# Titan_Servo_v1p01d.net
KiCad netlist of a schematic drawn in EAGLE
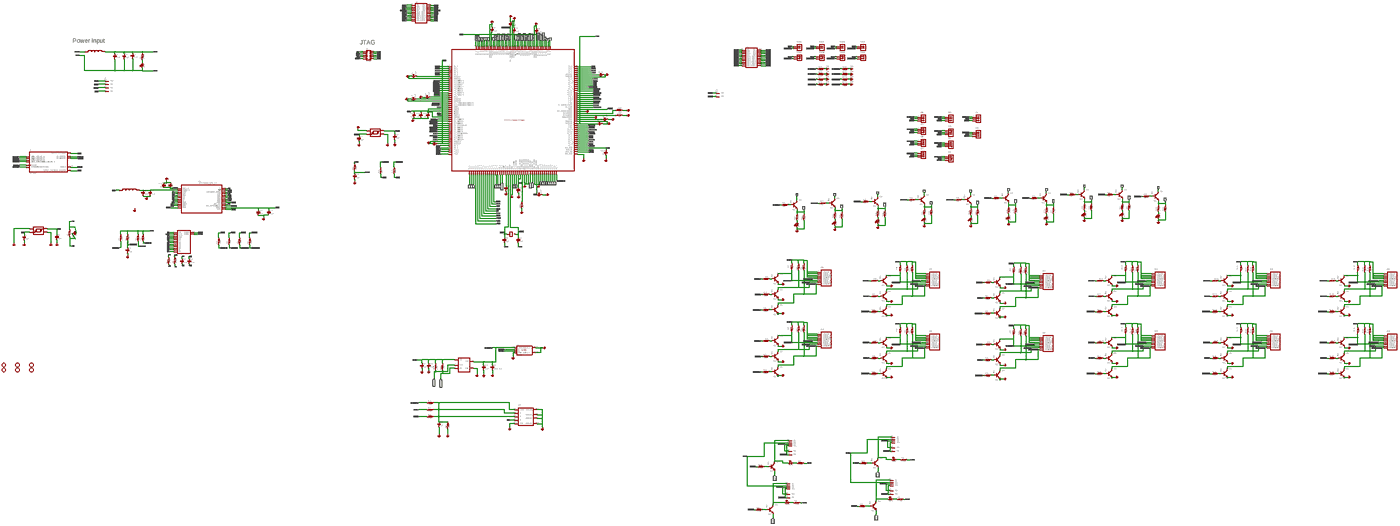
[diagram p0: schematic, sheet 1, overview]
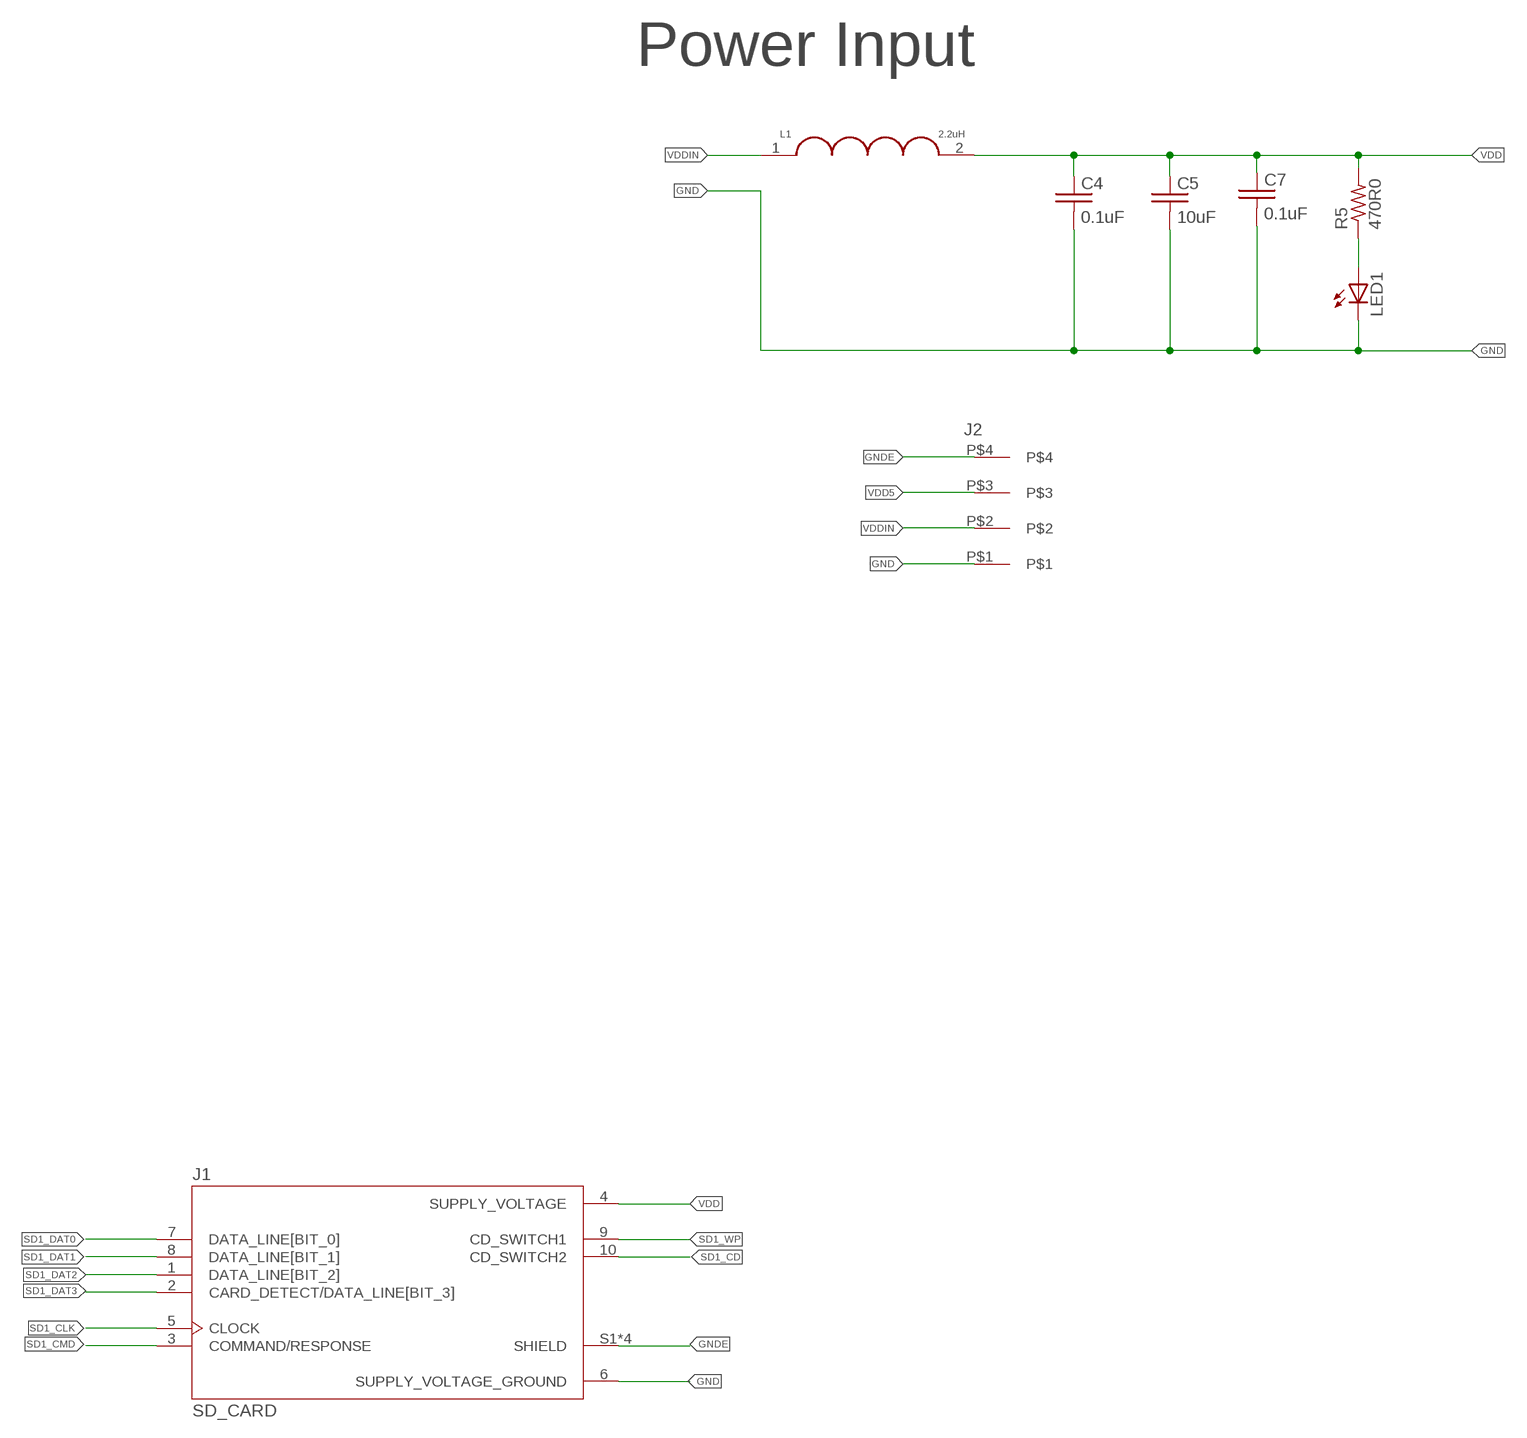
[diagram p1: schematic, sheet 1, part 1 of 9]
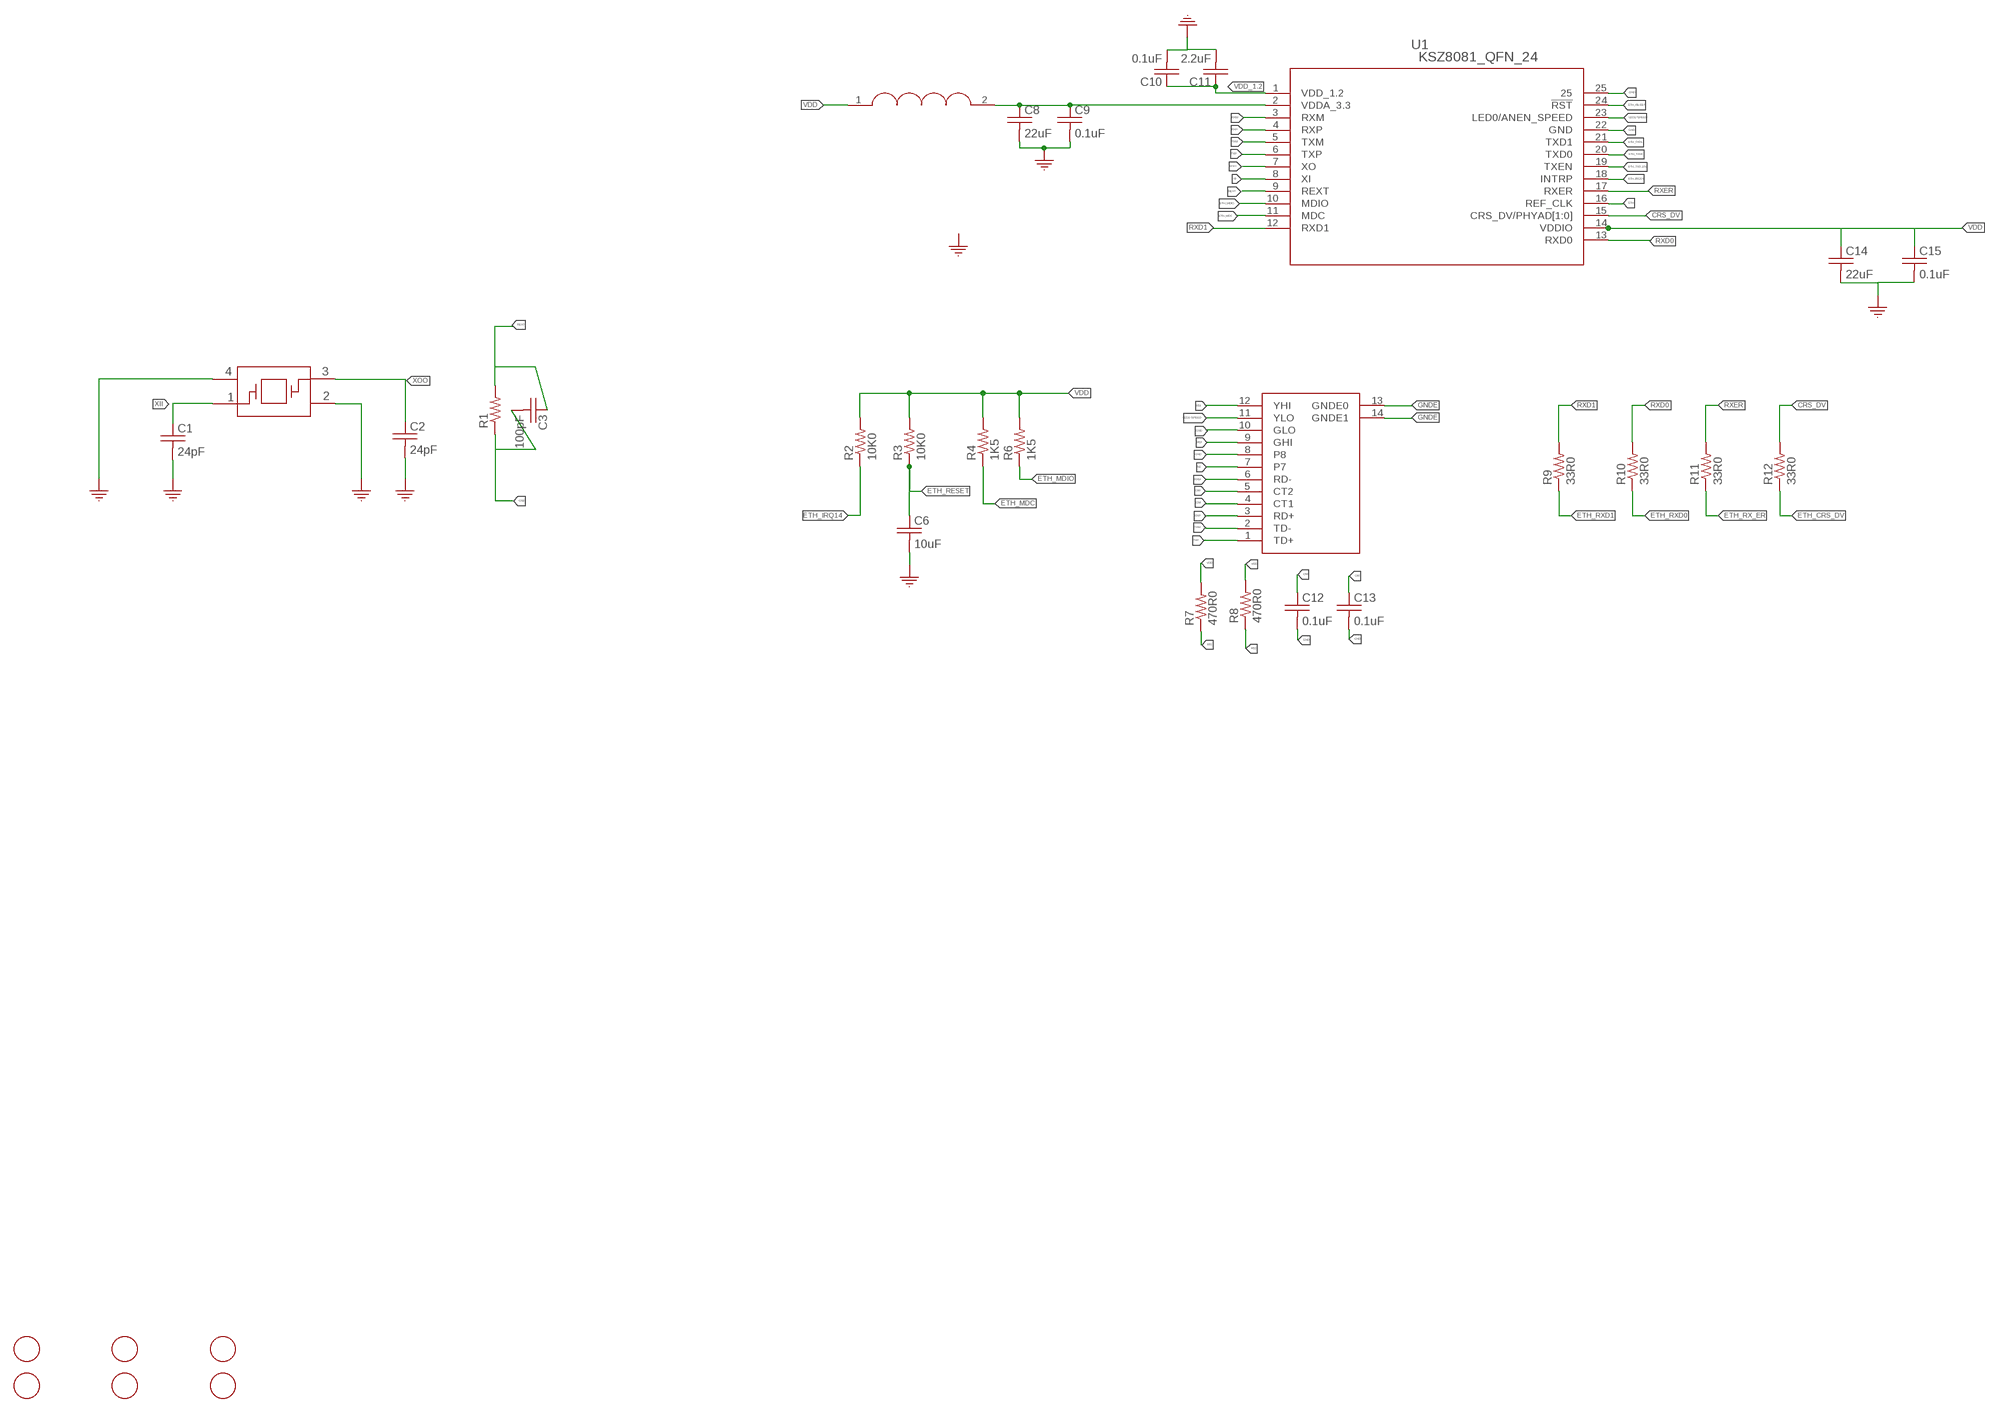
[diagram p2: schematic, sheet 1, part 2 of 9]
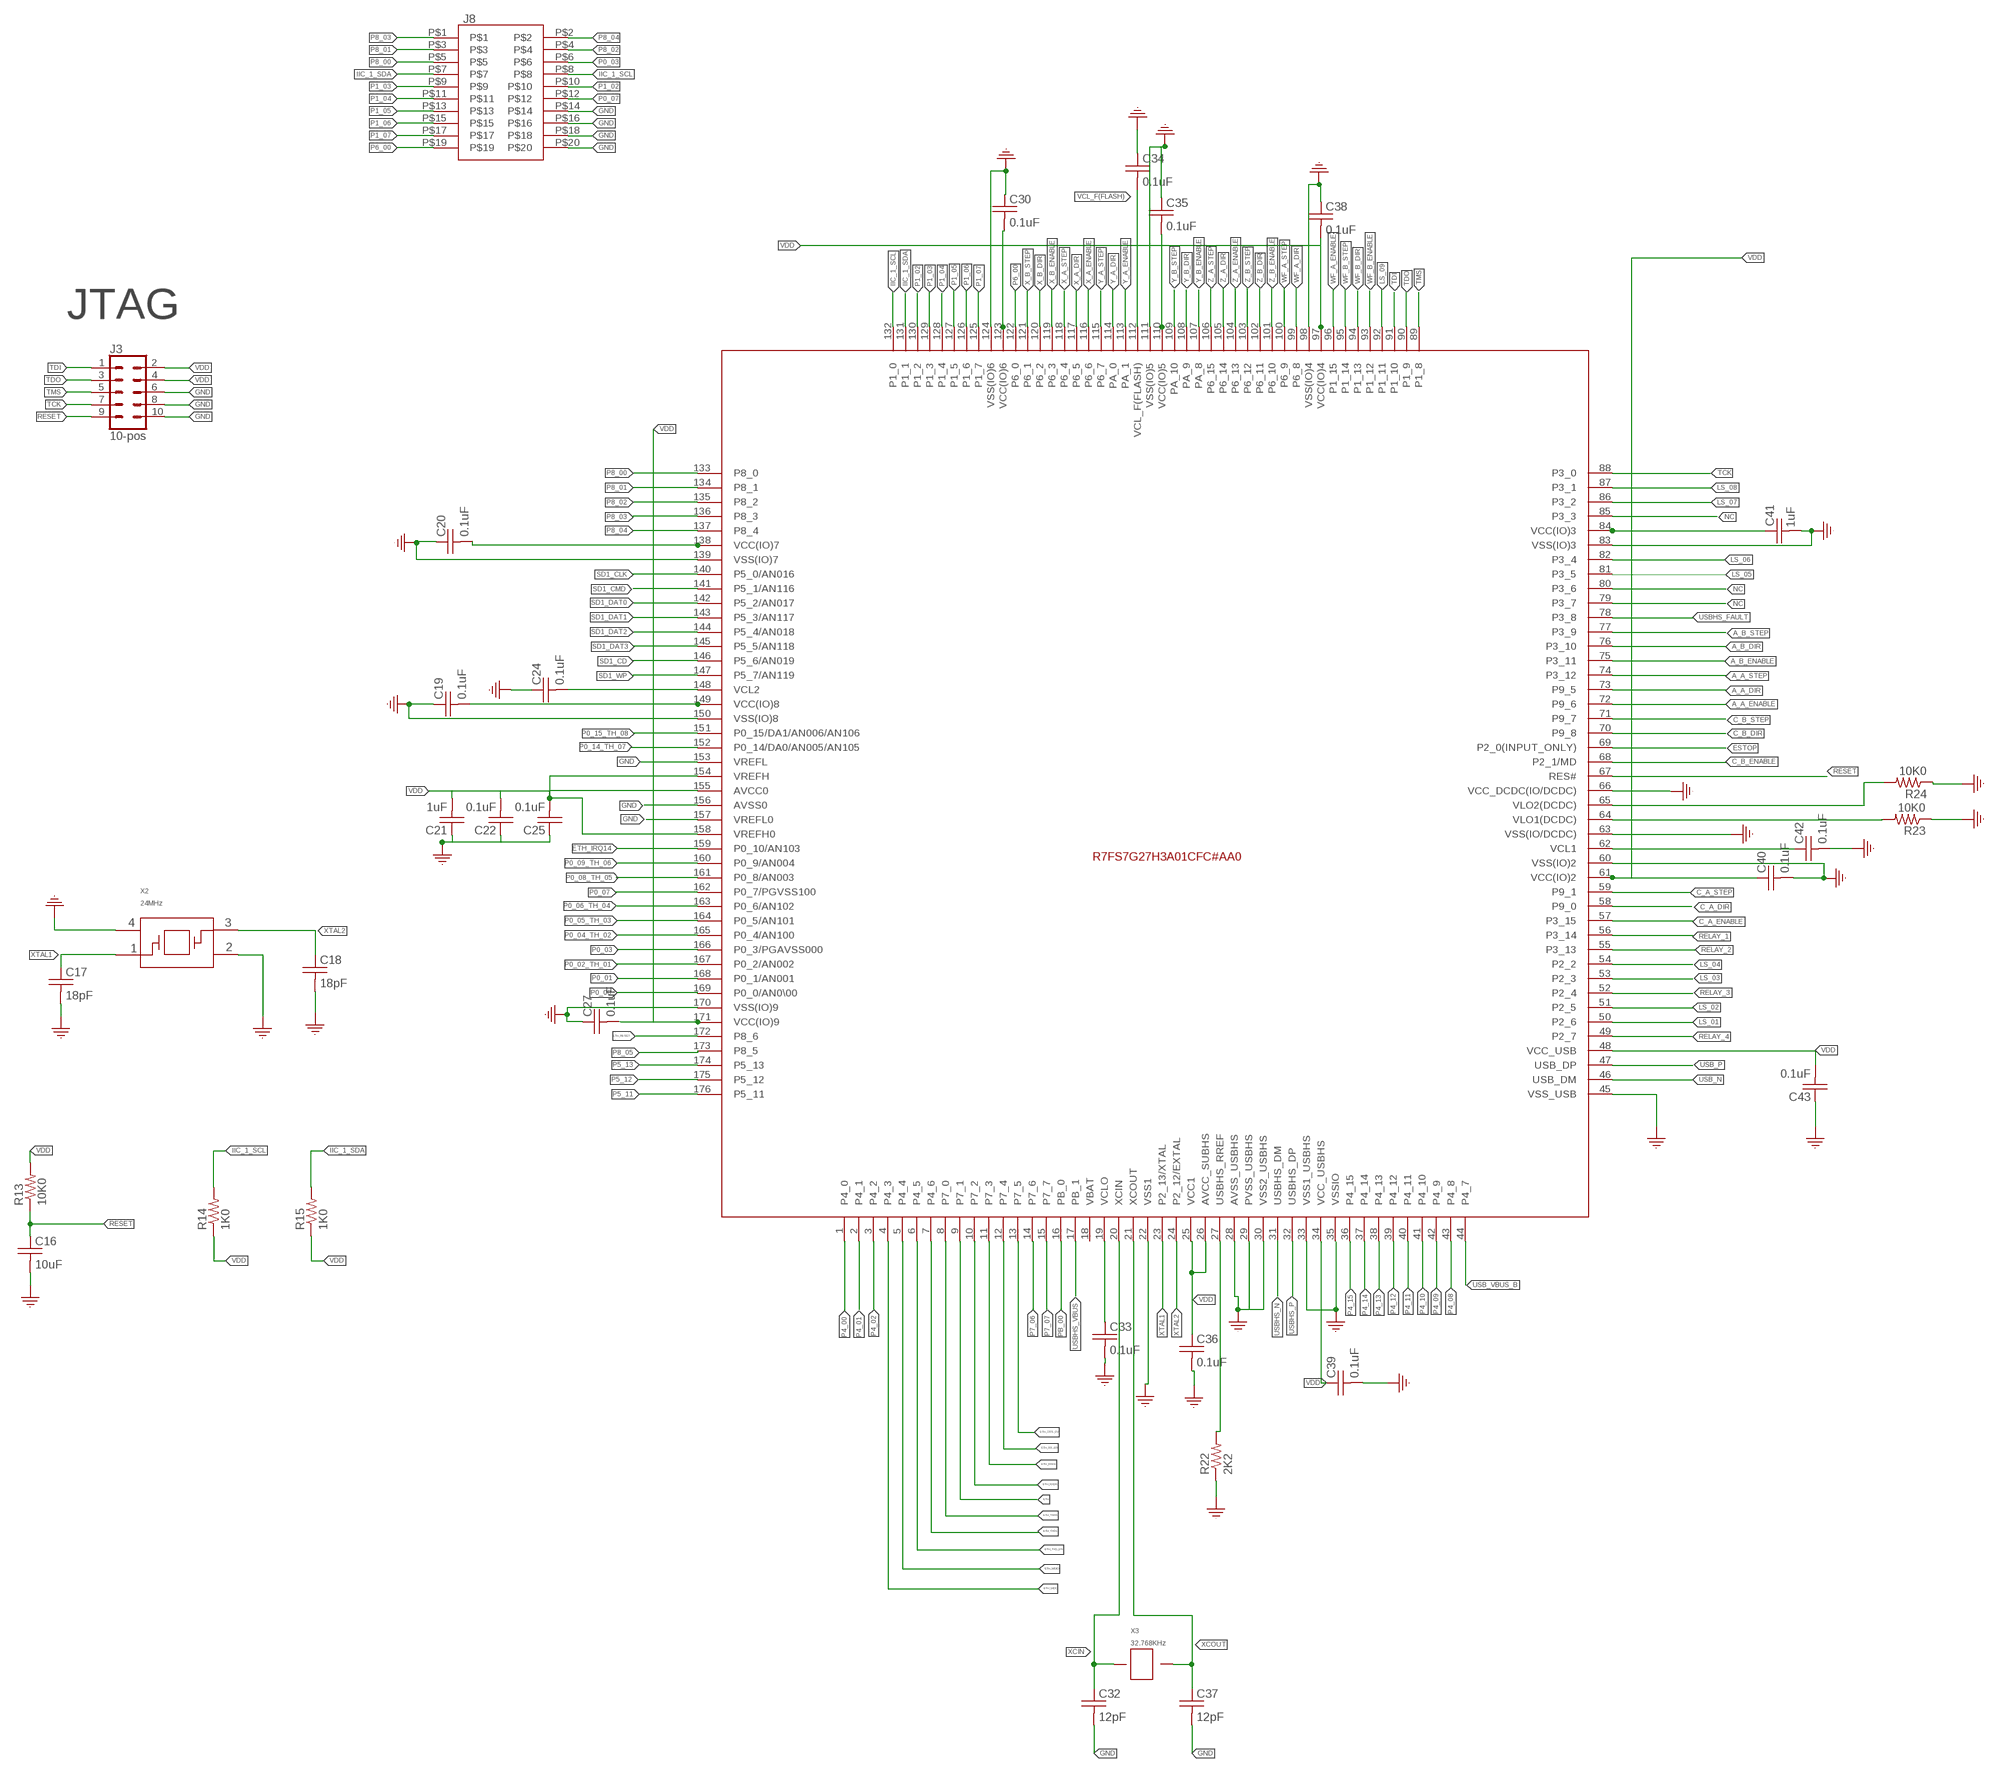
[diagram p3: schematic, sheet 1, part 3 of 9]
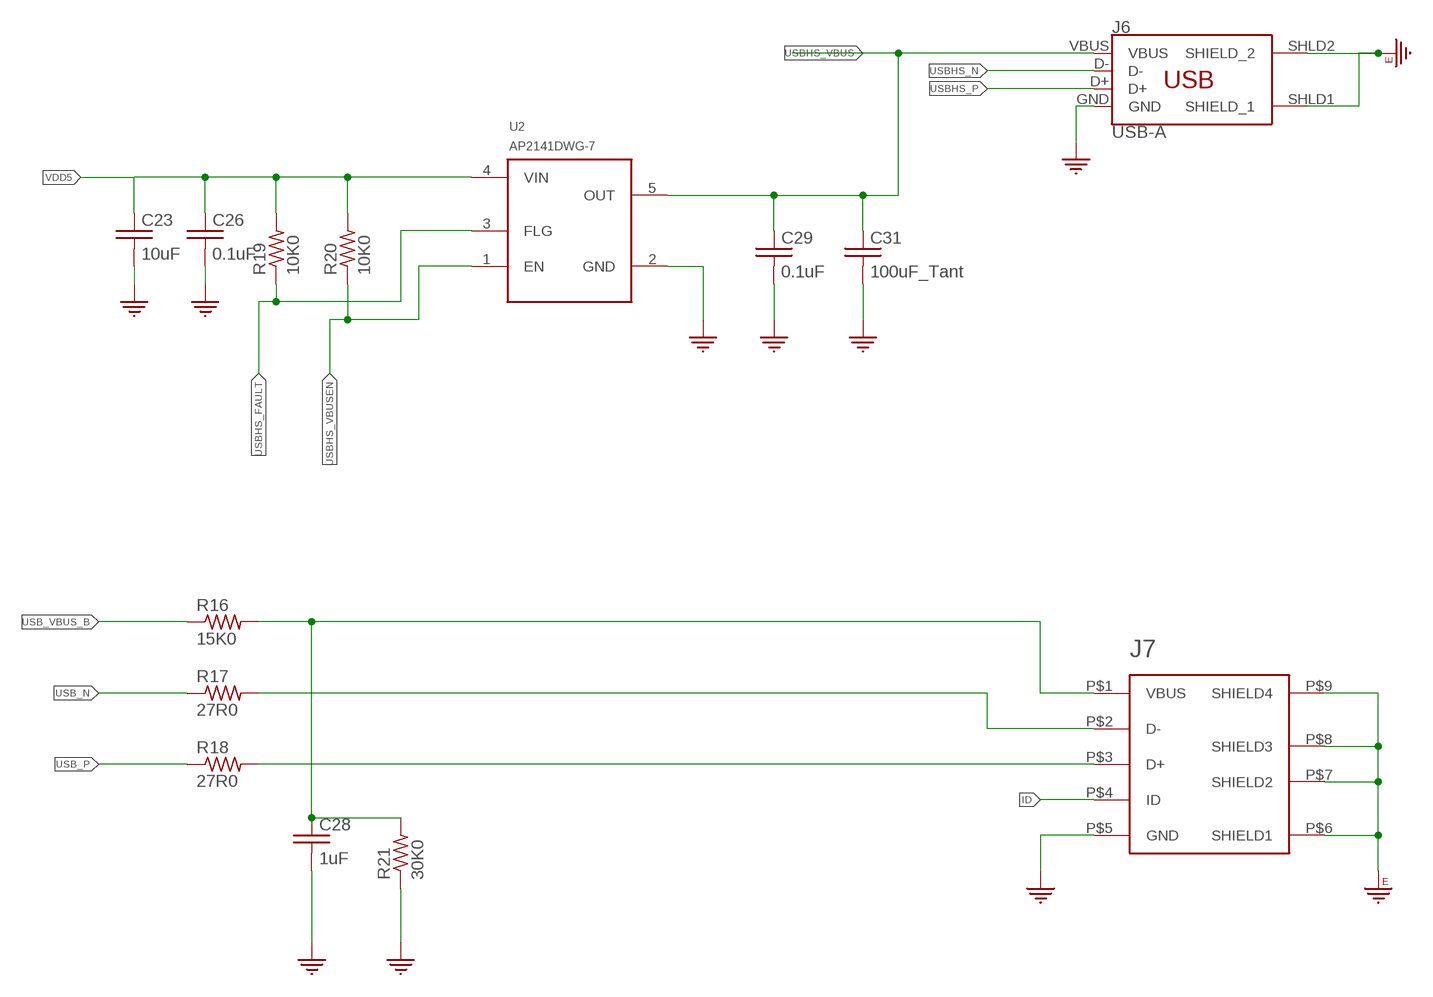
[diagram p4: schematic, sheet 1, part 4 of 9]
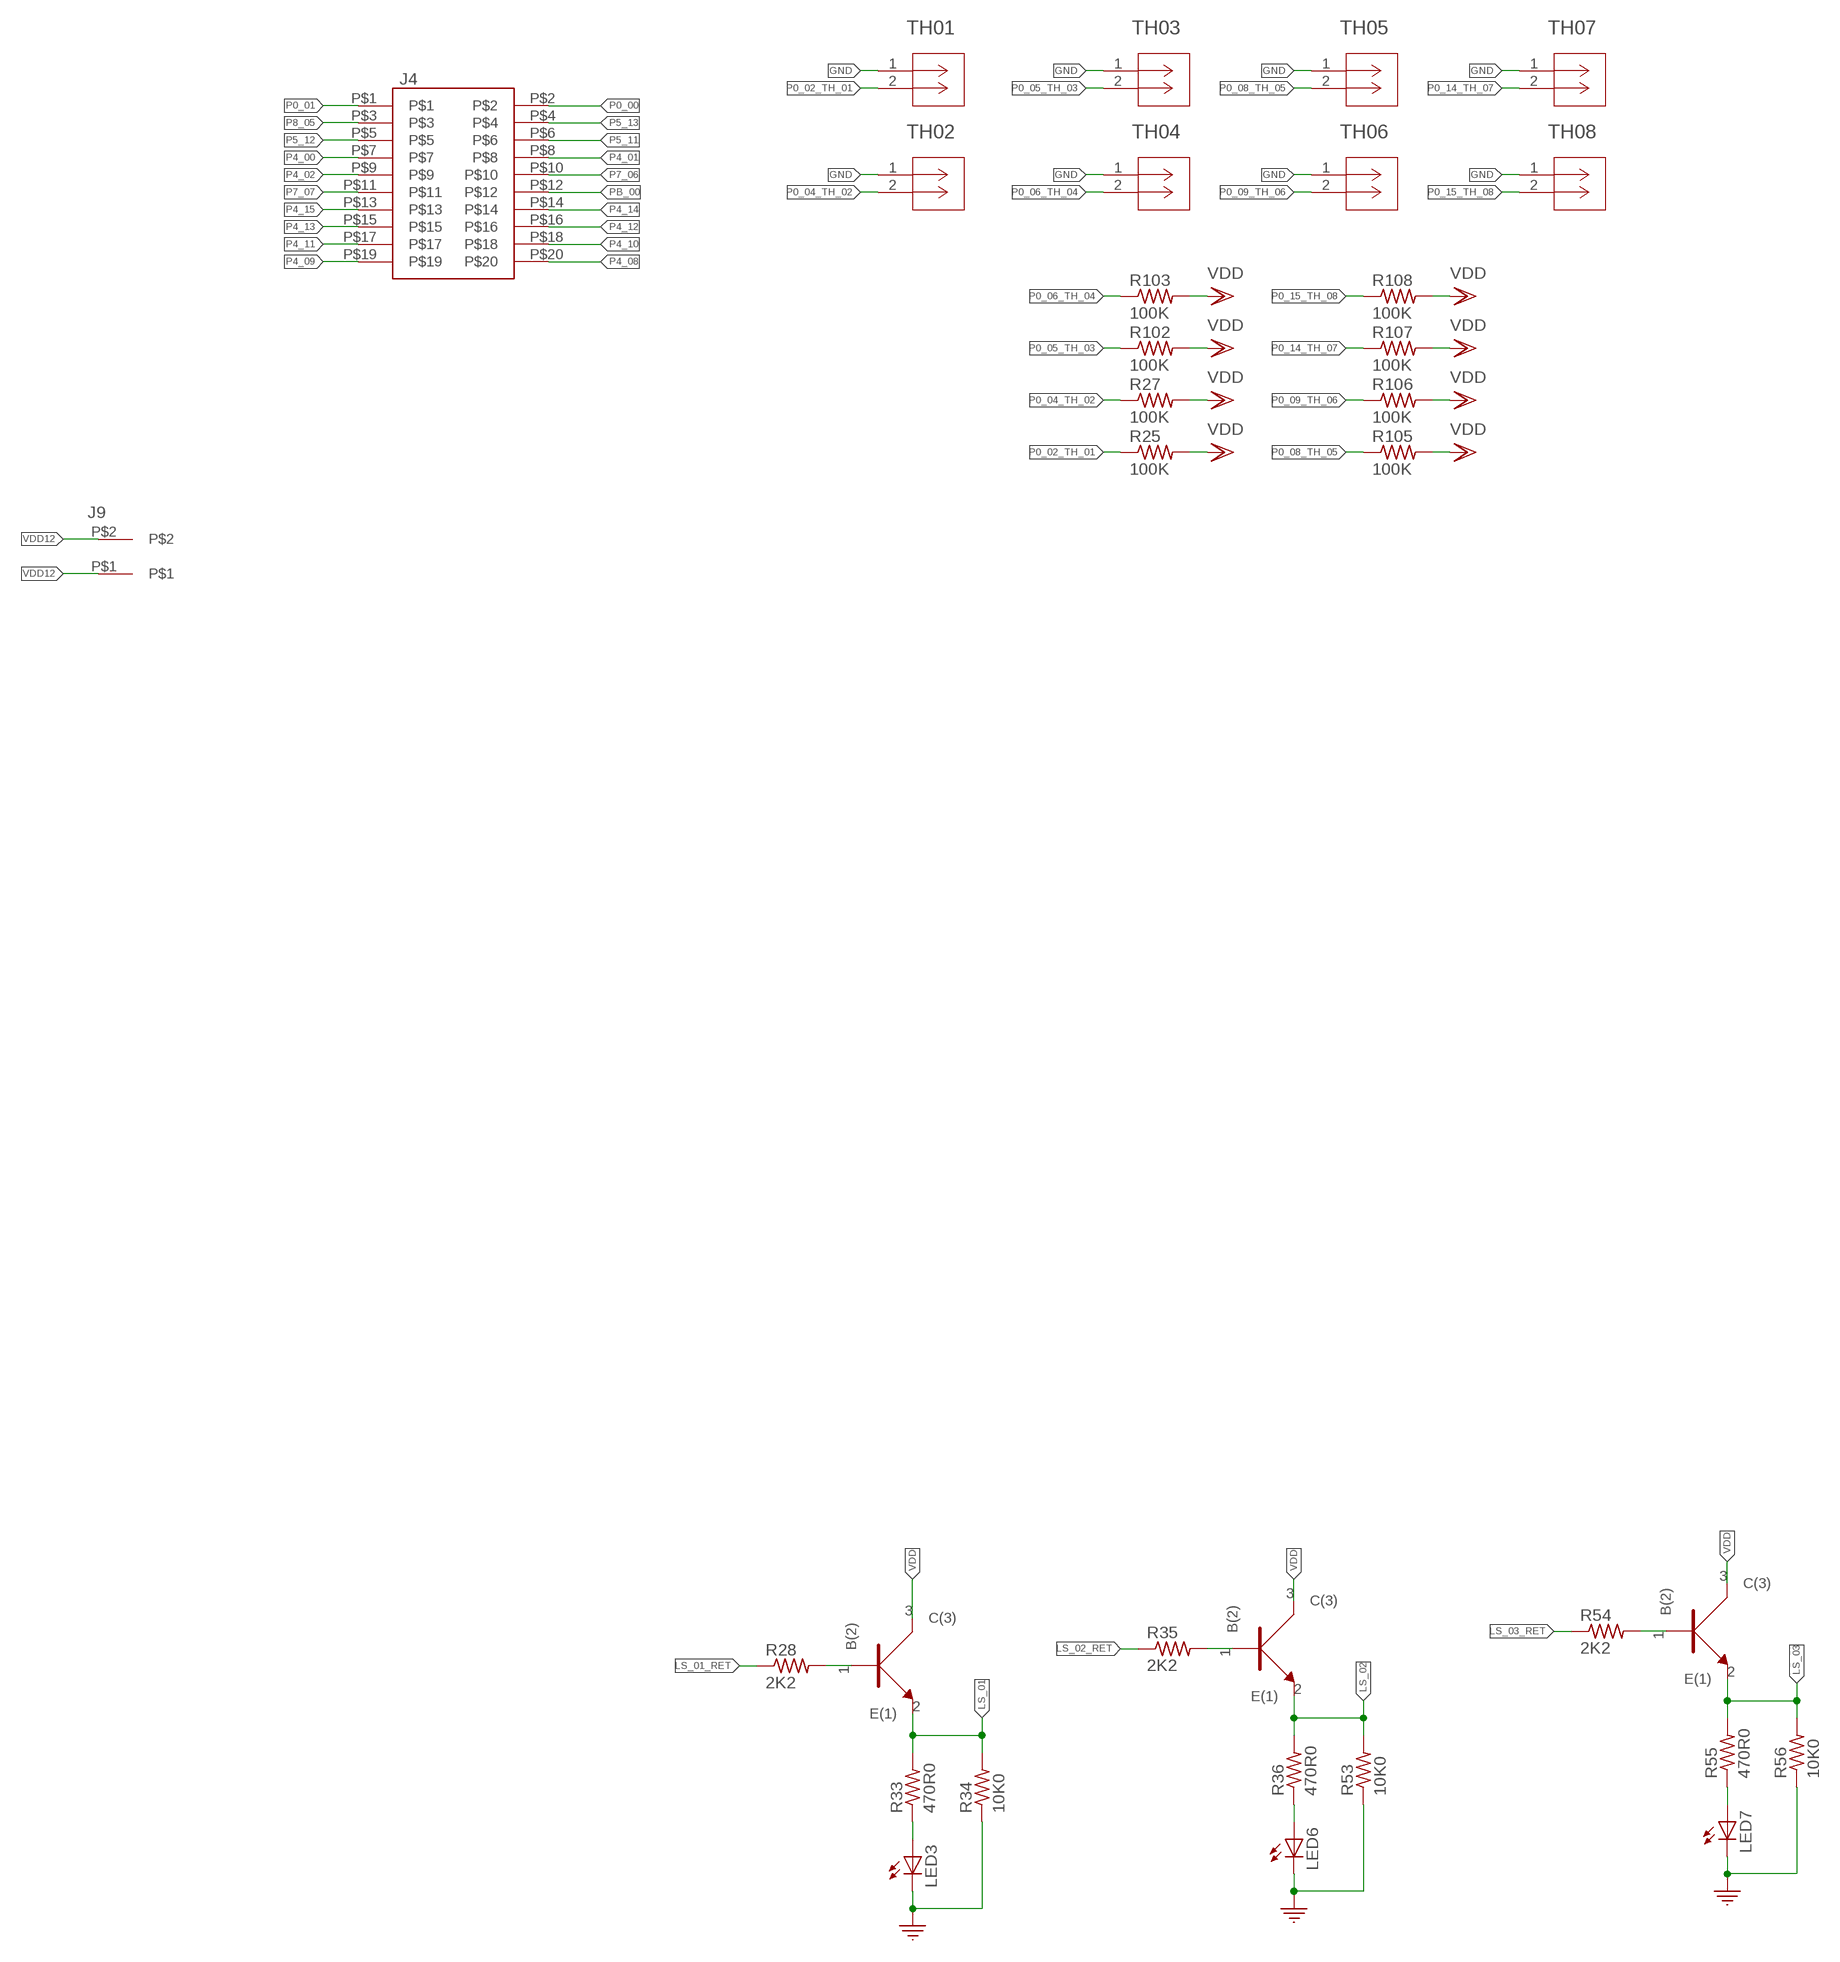
[diagram p5: schematic, sheet 1, part 5 of 9]
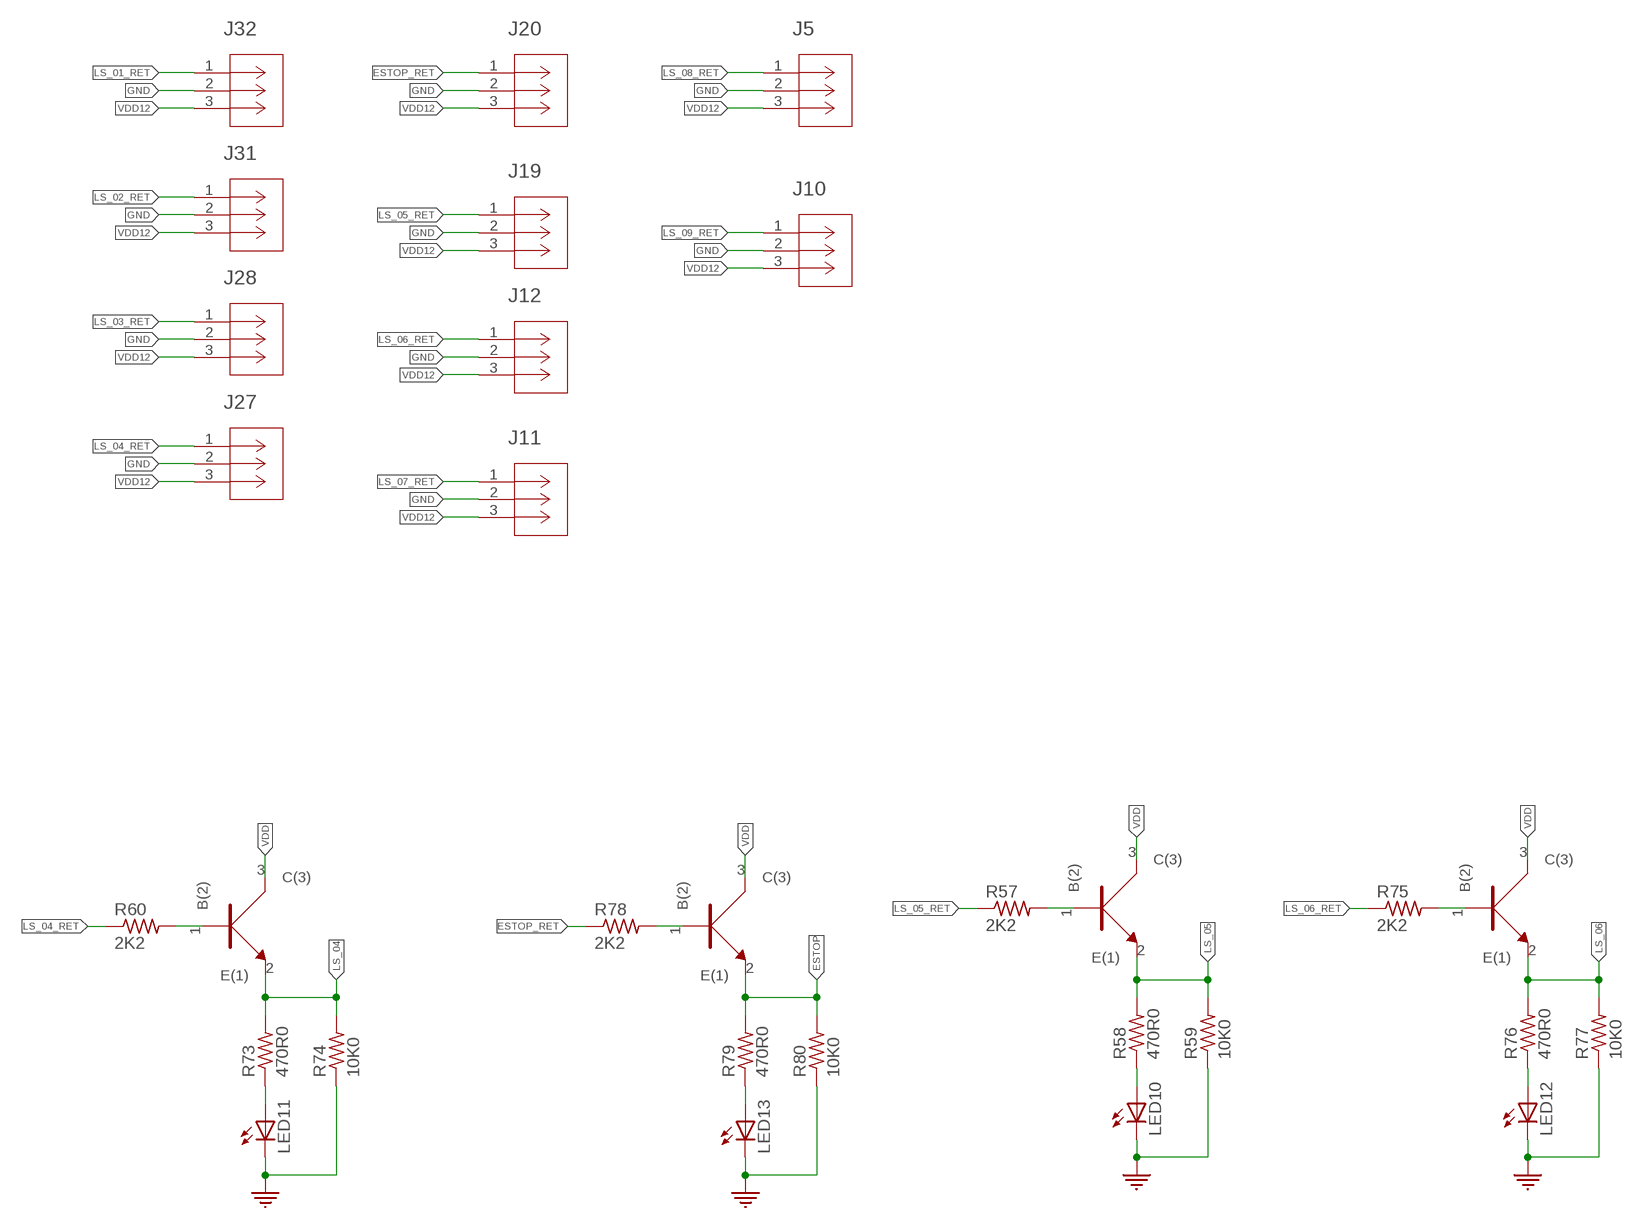
[diagram p6: schematic, sheet 1, part 6 of 9]
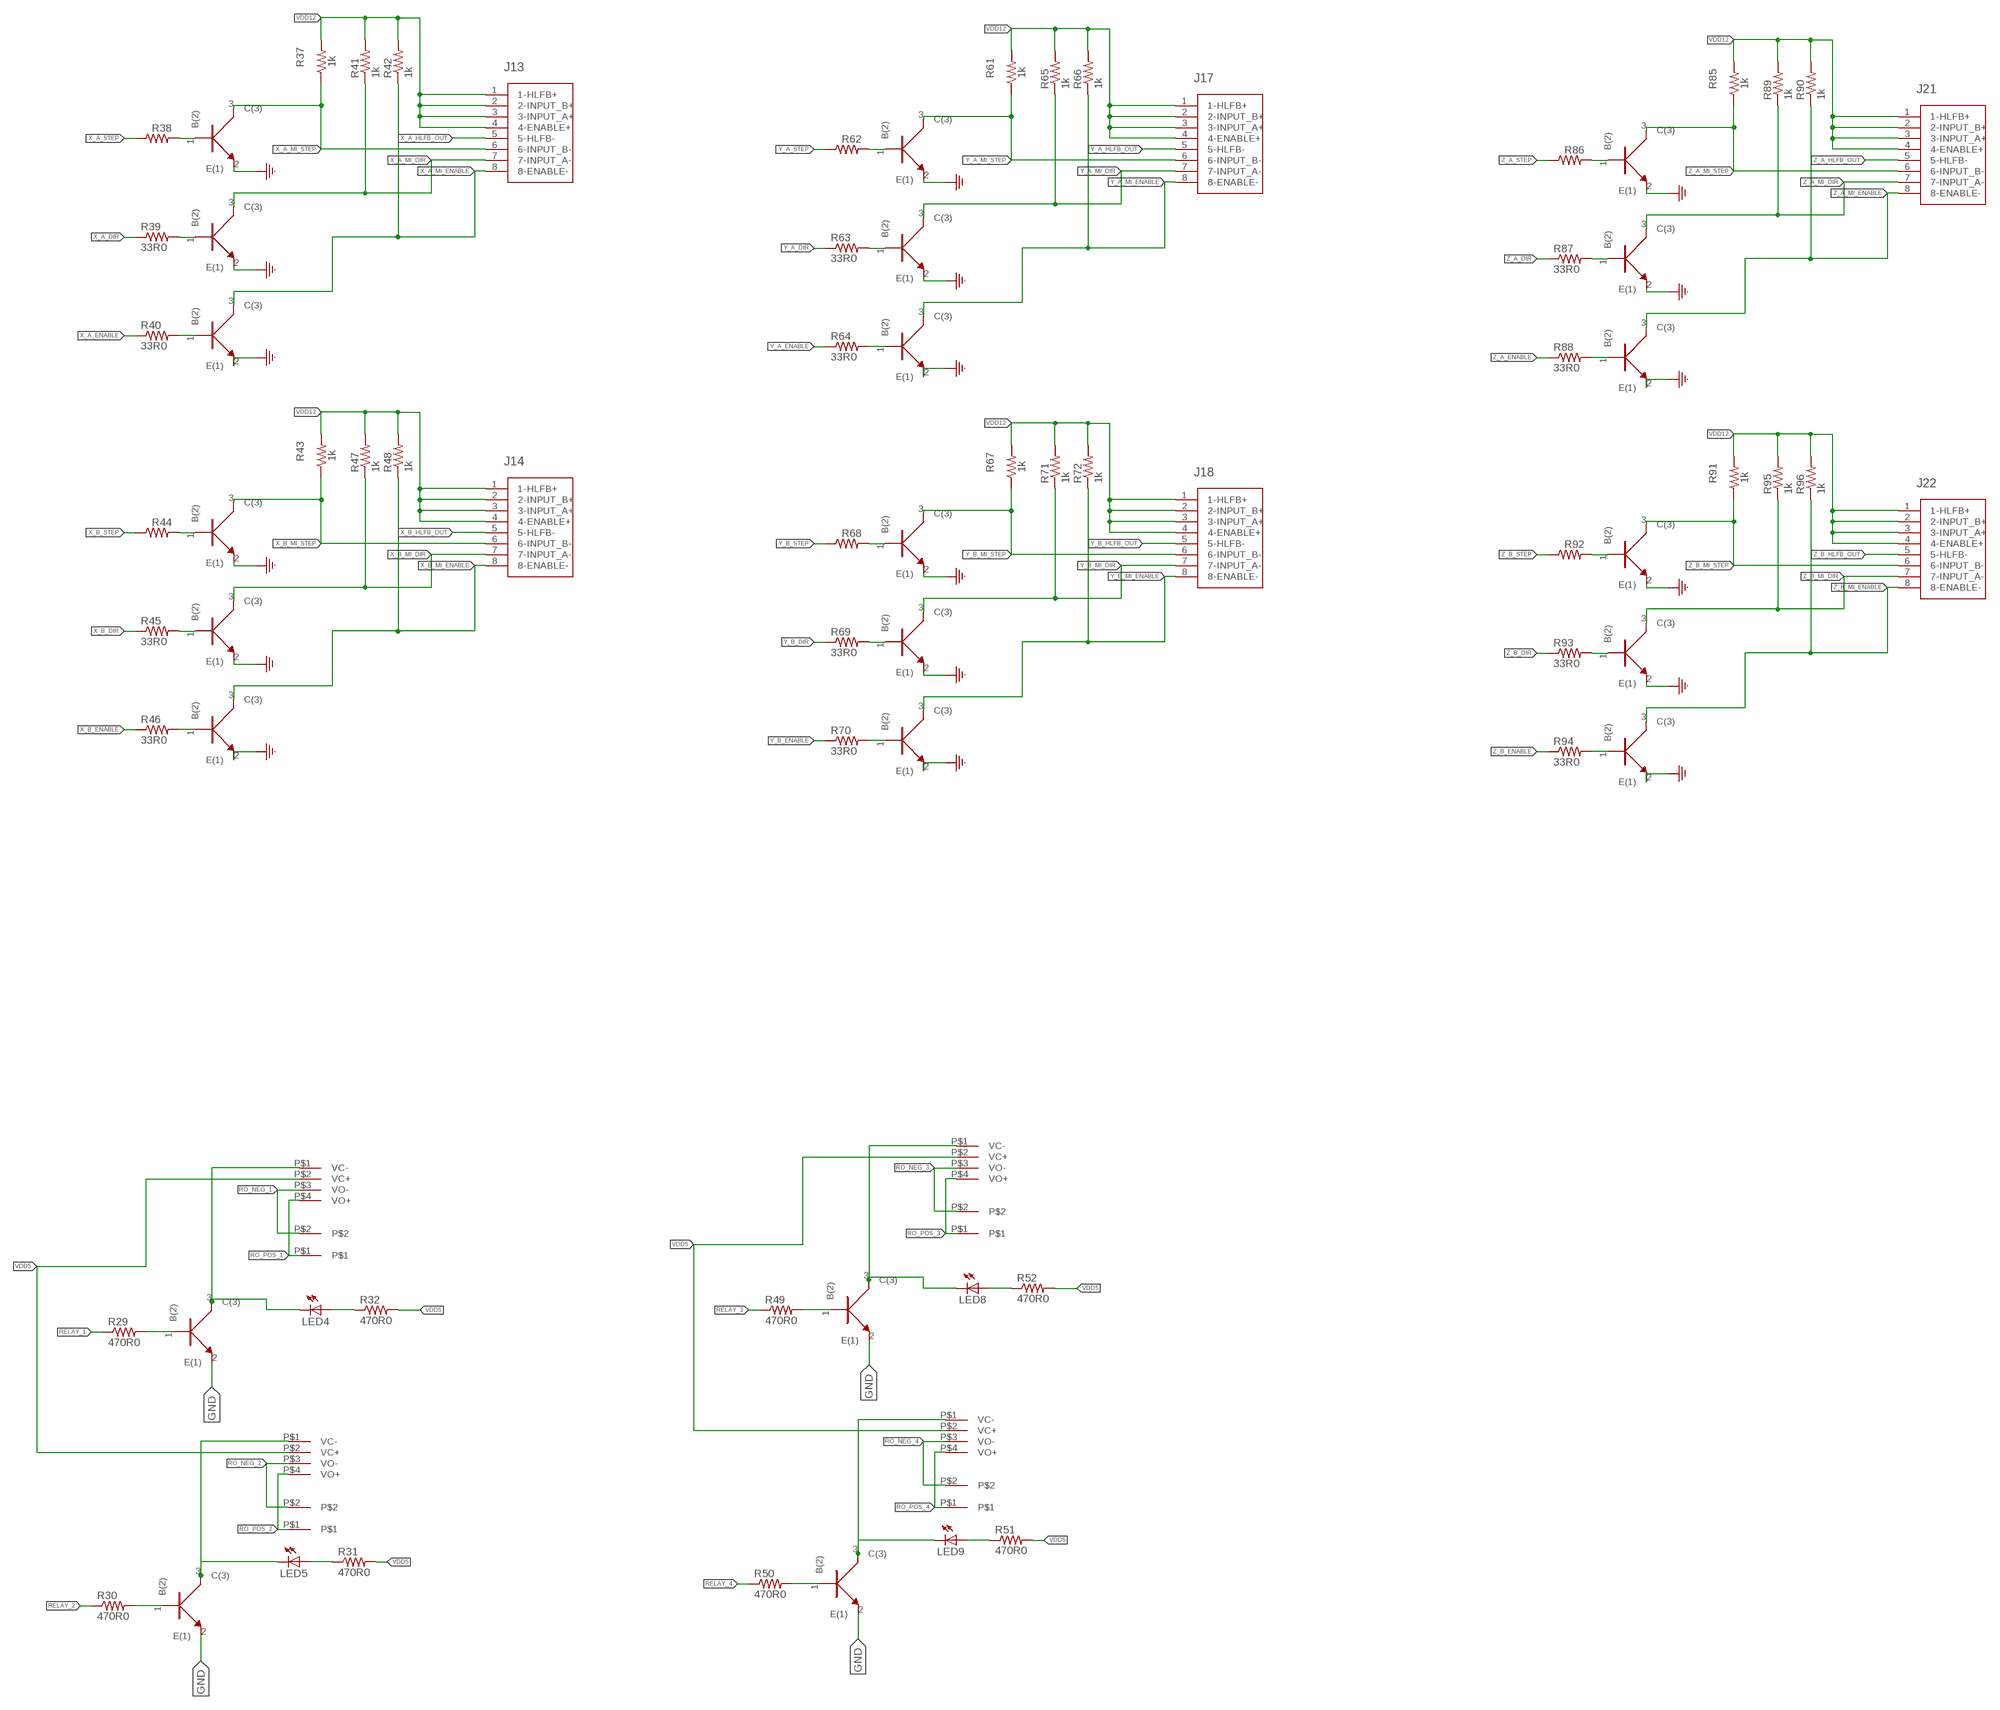
[diagram p7: schematic, sheet 1, part 7 of 9]
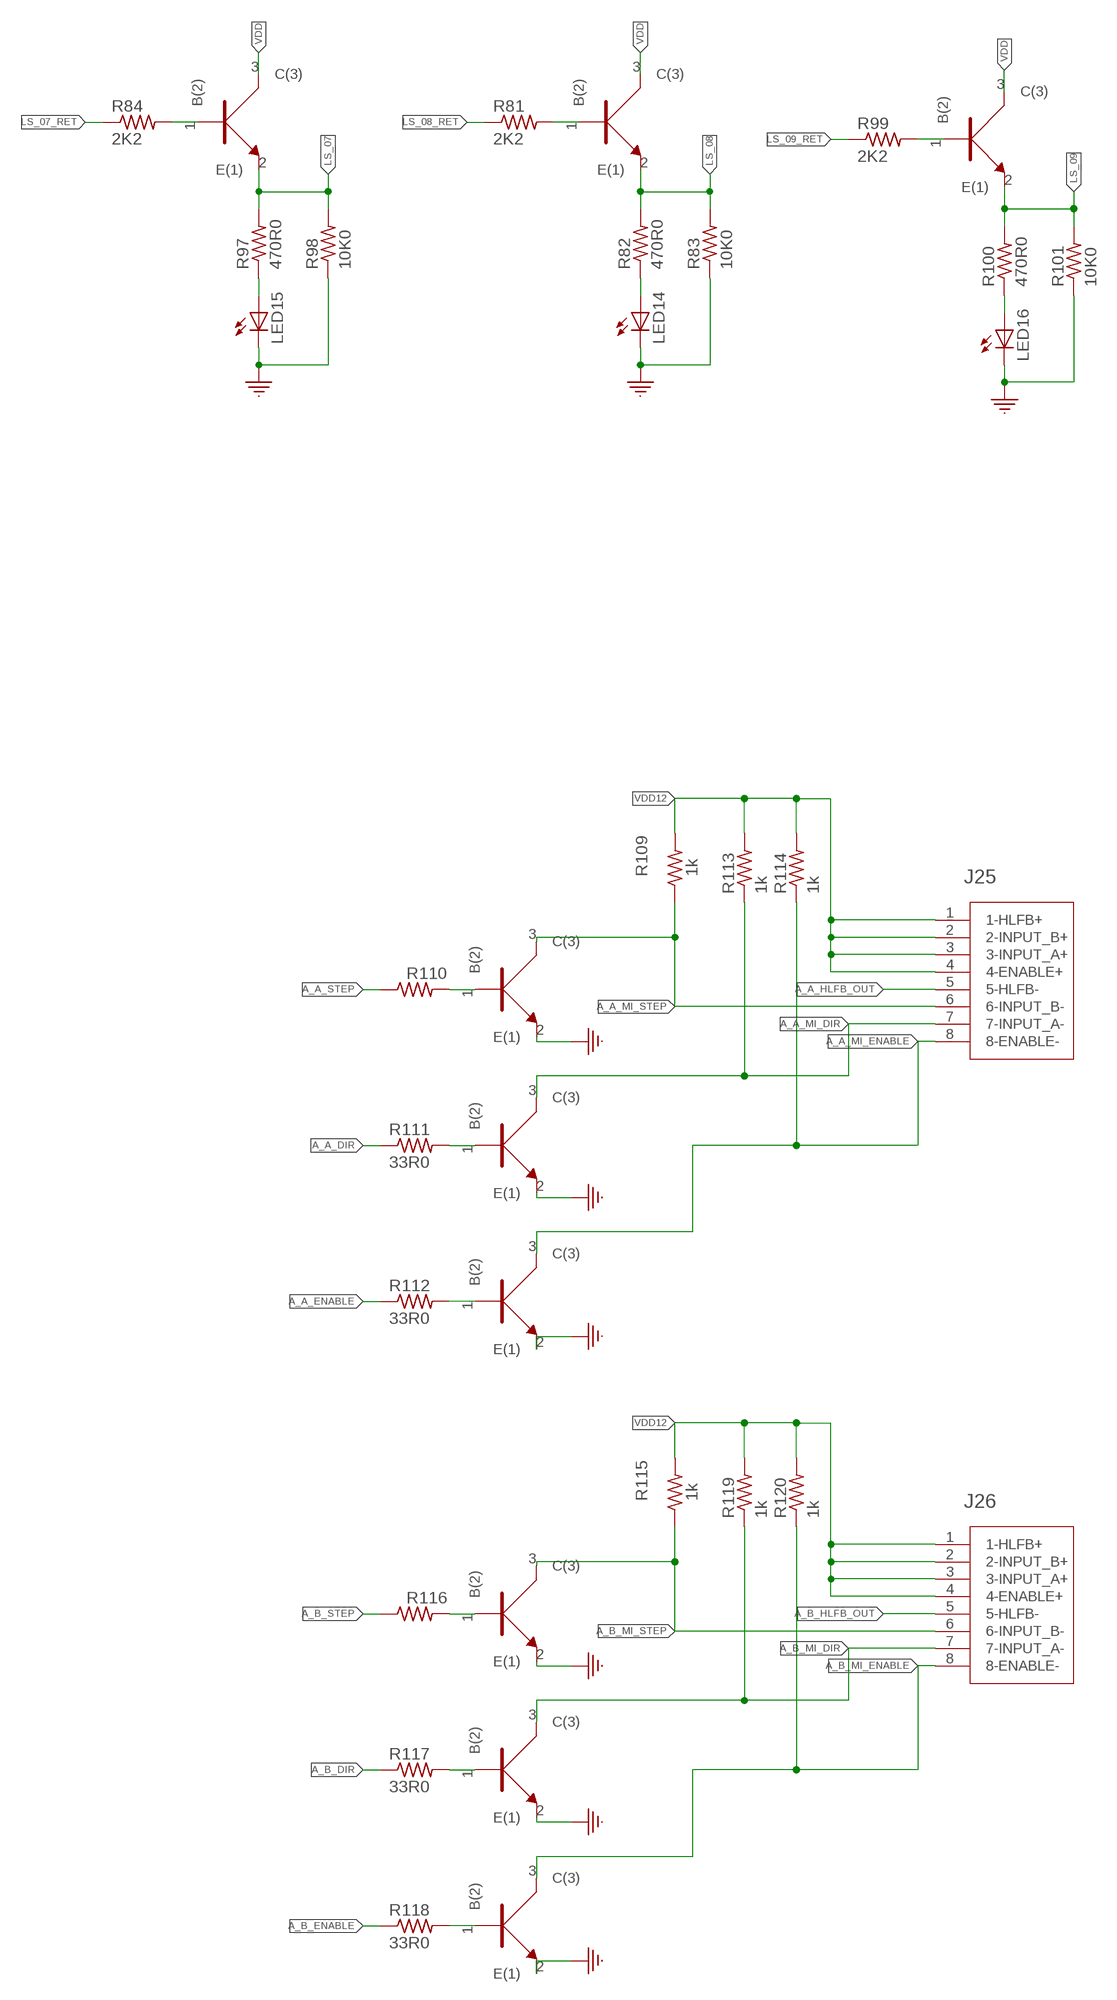
[diagram p8: schematic, sheet 1, part 8 of 9]
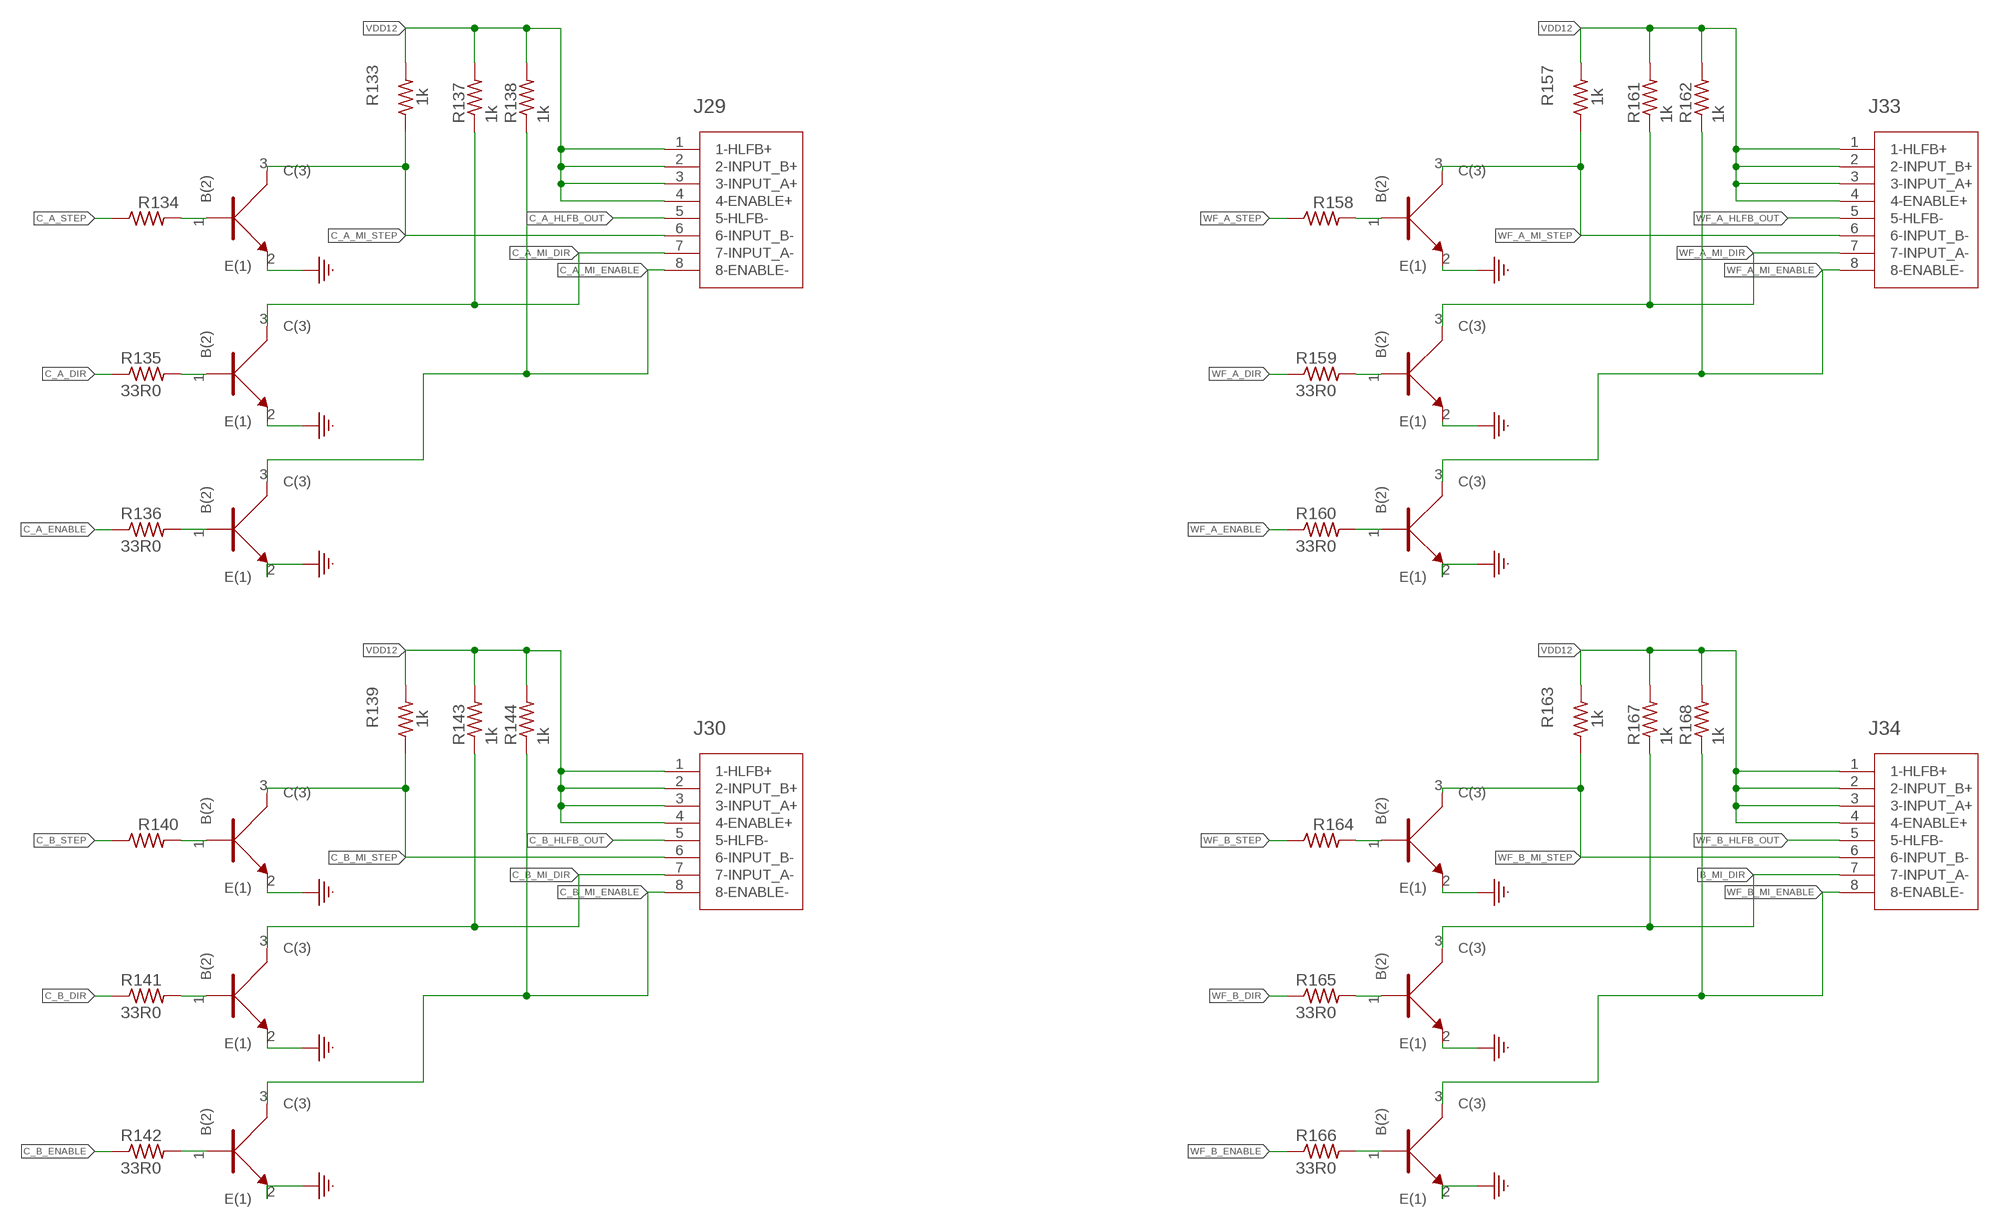
[diagram p9: schematic, sheet 1, part 9 of 9]

(export (version "E")
  (design (tool "Eeschema 10.0.6"))
  (components
    (comp (ref "AFID1")
      (value "FIDUCIAL_1MM")
      (footprint "eagle-import:FIDUCIAL_1MM")
      (libsource (lib "eagle-import") (part "FIDUCIAL_1MM"))
    )
    (comp (ref "AFID2")
      (value "FIDUCIAL_1MM")
      (footprint "eagle-import:FIDUCIAL_1MM")
      (libsource (lib "eagle-import") (part "FIDUCIAL_1MM"))
    )
    (comp (ref "AFID3")
      (value "FIDUCIAL_1MM")
      (footprint "eagle-import:FIDUCIAL_1MM")
      (libsource (lib "eagle-import") (part "FIDUCIAL_1MM"))
    )
    (comp (ref "AFID4")
      (value "FIDUCIAL_1MM")
      (footprint "eagle-import:FIDUCIAL_1MM")
      (libsource (lib "eagle-import") (part "FIDUCIAL_1MM"))
    )
    (comp (ref "AFID5")
      (value "FIDUCIAL_1MM")
      (footprint "eagle-import:FIDUCIAL_1MM")
      (libsource (lib "eagle-import") (part "FIDUCIAL_1MM"))
    )
    (comp (ref "AFID6")
      (value "FIDUCIAL_1MM")
      (footprint "eagle-import:FIDUCIAL_1MM")
      (libsource (lib "eagle-import") (part "FIDUCIAL_1MM"))
    )
    (comp (ref "C1")
      (value "24pF")
      (footprint "eagle-import:0402")
      (fields (field (name "PARTNO") "CC0402GRNPO9BN240"))
      (libsource (lib "eagle-import") (part "C_0402_24PF"))
    )
    (comp (ref "C2")
      (value "24pF")
      (footprint "eagle-import:0402")
      (fields (field (name "PARTNO") "CC0402GRNPO9BN240"))
      (libsource (lib "eagle-import") (part "C_0402_24PF"))
    )
    (comp (ref "C3")
      (value "100pF")
      (footprint "eagle-import:0402")
      (fields (field (name "PARTNO") "CL05C101JB5NNNC"))
      (libsource (lib "eagle-import") (part "C_0402_100PF"))
    )
    (comp (ref "C4")
      (value "0.1uF")
      (footprint "eagle-import:0402")
      (fields (field (name "PARTNO") "CL05F104ZO5NNNC"))
      (libsource (lib "eagle-import") (part "C_0402_0.1UF"))
    )
    (comp (ref "C5")
      (value "10uF")
      (footprint "eagle-import:0402")
      (fields (field (name "PARTNO") "CL05A106MP8NUB8"))
      (libsource (lib "eagle-import") (part "C_0402_10UF"))
    )
    (comp (ref "C6")
      (value "10uF")
      (footprint "eagle-import:0402")
      (fields (field (name "PARTNO") "CL05A106MP8NUB8"))
      (libsource (lib "eagle-import") (part "C_0402_10UF"))
    )
    (comp (ref "C7")
      (value "0.1uF")
      (footprint "eagle-import:0402")
      (fields (field (name "PARTNO") "CL05F104ZO5NNNC"))
      (libsource (lib "eagle-import") (part "C_0402_0.1UF"))
    )
    (comp (ref "C8")
      (value "22uF")
      (footprint "eagle-import:0402")
      (fields (field (name "PARTNO") "CL05A226MQ5N6J8"))
      (libsource (lib "eagle-import") (part "C_0402_22UF"))
    )
    (comp (ref "C9")
      (value "0.1uF")
      (footprint "eagle-import:0402")
      (fields (field (name "PARTNO") "CL05F104ZO5NNNC"))
      (libsource (lib "eagle-import") (part "C_0402_0.1UF"))
    )
    (comp (ref "C10")
      (value "0.1uF")
      (footprint "eagle-import:0402")
      (fields (field (name "PARTNO") "CL05F104ZO5NNNC"))
      (libsource (lib "eagle-import") (part "C_0402_0.1UF"))
    )
    (comp (ref "C11")
      (value "2.2uF")
      (footprint "eagle-import:0402")
      (fields (field (name "PARTNO") "GRM155C81C225ME15D"))
      (libsource (lib "eagle-import") (part "C_0402_2.2UF"))
    )
    (comp (ref "C12")
      (value "0.1uF")
      (footprint "eagle-import:0402")
      (fields (field (name "PARTNO") "CL05F104ZO5NNNC"))
      (libsource (lib "eagle-import") (part "C_0402_0.1UF"))
    )
    (comp (ref "C13")
      (value "0.1uF")
      (footprint "eagle-import:0402")
      (fields (field (name "PARTNO") "CL05F104ZO5NNNC"))
      (libsource (lib "eagle-import") (part "C_0402_0.1UF"))
    )
    (comp (ref "C14")
      (value "22uF")
      (footprint "eagle-import:0402")
      (fields (field (name "PARTNO") "CL05A226MQ5N6J8"))
      (libsource (lib "eagle-import") (part "C_0402_22UF"))
    )
    (comp (ref "C15")
      (value "0.1uF")
      (footprint "eagle-import:0402")
      (fields (field (name "PARTNO") "CL05F104ZO5NNNC"))
      (libsource (lib "eagle-import") (part "C_0402_0.1UF"))
    )
    (comp (ref "C16")
      (value "10uF")
      (footprint "eagle-import:0402")
      (fields (field (name "PARTNO") "CL05A106MP8NUB8"))
      (libsource (lib "eagle-import") (part "C_0402_10UF"))
    )
    (comp (ref "C17")
      (value "18pF")
      (footprint "eagle-import:0402")
      (fields (field (name "PARTNO") "UMK105CG180JV-F"))
      (libsource (lib "eagle-import") (part "C_0402_18PF"))
    )
    (comp (ref "C18")
      (value "18pF")
      (footprint "eagle-import:0402")
      (fields (field (name "PARTNO") "UMK105CG180JV-F"))
      (libsource (lib "eagle-import") (part "C_0402_18PF"))
    )
    (comp (ref "C19")
      (value "0.1uF")
      (footprint "eagle-import:0402")
      (fields (field (name "PARTNO") "CL05F104ZO5NNNC"))
      (libsource (lib "eagle-import") (part "C_0402_0.1UF"))
    )
    (comp (ref "C20")
      (value "0.1uF")
      (footprint "eagle-import:0402")
      (fields (field (name "PARTNO") "CL05F104ZO5NNNC"))
      (libsource (lib "eagle-import") (part "C_0402_0.1UF"))
    )
    (comp (ref "C21")
      (value "1uF")
      (footprint "eagle-import:0402")
      (fields (field (name "PARTNO") "CL05A105KO5NNNC"))
      (libsource (lib "eagle-import") (part "C_0402_1UF"))
    )
    (comp (ref "C22")
      (value "0.1uF")
      (footprint "eagle-import:0402")
      (fields (field (name "PARTNO") "CL05F104ZO5NNNC"))
      (libsource (lib "eagle-import") (part "C_0402_0.1UF"))
    )
    (comp (ref "C23")
      (value "10uF")
      (footprint "eagle-import:0402")
      (fields (field (name "PARTNO") "CL05A106MP8NUB8"))
      (libsource (lib "eagle-import") (part "C_0402_10UF"))
    )
    (comp (ref "C24")
      (value "0.1uF")
      (footprint "eagle-import:0402")
      (fields (field (name "PARTNO") "CL05F104ZO5NNNC"))
      (libsource (lib "eagle-import") (part "C_0402_0.1UF"))
    )
    (comp (ref "C25")
      (value "0.1uF")
      (footprint "eagle-import:0402")
      (fields (field (name "PARTNO") "CL05F104ZO5NNNC"))
      (libsource (lib "eagle-import") (part "C_0402_0.1UF"))
    )
    (comp (ref "C26")
      (value "0.1uF")
      (footprint "eagle-import:0402")
      (fields (field (name "PARTNO") "CL05F104ZO5NNNC"))
      (libsource (lib "eagle-import") (part "C_0402_0.1UF"))
    )
    (comp (ref "C27")
      (value "0.1uF")
      (footprint "eagle-import:0402")
      (fields (field (name "PARTNO") "CL05F104ZO5NNNC"))
      (libsource (lib "eagle-import") (part "C_0402_0.1UF"))
    )
    (comp (ref "C28")
      (value "1uF")
      (footprint "eagle-import:0402")
      (fields (field (name "PARTNO") "CL05A105KO5NNNC"))
      (libsource (lib "eagle-import") (part "C_0402_1UF"))
    )
    (comp (ref "C29")
      (value "0.1uF")
      (footprint "eagle-import:0402")
      (fields (field (name "PARTNO") "CL05F104ZO5NNNC"))
      (libsource (lib "eagle-import") (part "C_0402_0.1UF"))
    )
    (comp (ref "C30")
      (value "0.1uF")
      (footprint "eagle-import:0402")
      (fields (field (name "PARTNO") "CL05F104ZO5NNNC"))
      (libsource (lib "eagle-import") (part "C_0402_0.1UF"))
    )
    (comp (ref "C31")
      (value "100uF_Tant")
      (footprint "eagle-import:C1210")
      (fields (field (name "PARTNO") "TLJT107M010R0900"))
      (libsource (lib "eagle-import") (part "C_1210_100UF_TANT"))
    )
    (comp (ref "C32")
      (value "12pF")
      (footprint "eagle-import:0402")
      (fields (field (name "PARTNO") "CL05C120JB5NNNC"))
      (libsource (lib "eagle-import") (part "C_0402_12PF"))
    )
    (comp (ref "C33")
      (value "0.1uF")
      (footprint "eagle-import:0402")
      (fields (field (name "PARTNO") "CL05F104ZO5NNNC"))
      (libsource (lib "eagle-import") (part "C_0402_0.1UF"))
    )
    (comp (ref "C34")
      (value "0.1uF")
      (footprint "eagle-import:0402")
      (fields (field (name "PARTNO") "CL05F104ZO5NNNC"))
      (libsource (lib "eagle-import") (part "C_0402_0.1UF"))
    )
    (comp (ref "C35")
      (value "0.1uF")
      (footprint "eagle-import:0402")
      (fields (field (name "PARTNO") "CL05F104ZO5NNNC"))
      (libsource (lib "eagle-import") (part "C_0402_0.1UF"))
    )
    (comp (ref "C36")
      (value "0.1uF")
      (footprint "eagle-import:0402")
      (fields (field (name "PARTNO") "CL05F104ZO5NNNC"))
      (libsource (lib "eagle-import") (part "C_0402_0.1UF"))
    )
    (comp (ref "C37")
      (value "12pF")
      (footprint "eagle-import:0402")
      (fields (field (name "PARTNO") "CL05C120JB5NNNC"))
      (libsource (lib "eagle-import") (part "C_0402_12PF"))
    )
    (comp (ref "C38")
      (value "0.1uF")
      (footprint "eagle-import:0402")
      (fields (field (name "PARTNO") "CL05F104ZO5NNNC"))
      (libsource (lib "eagle-import") (part "C_0402_0.1UF"))
    )
    (comp (ref "C39")
      (value "0.1uF")
      (footprint "eagle-import:0402")
      (fields (field (name "PARTNO") "CL05F104ZO5NNNC"))
      (libsource (lib "eagle-import") (part "C_0402_0.1UF"))
    )
    (comp (ref "C40")
      (value "0.1uF")
      (footprint "eagle-import:0402")
      (fields (field (name "PARTNO") "CL05F104ZO5NNNC"))
      (libsource (lib "eagle-import") (part "C_0402_0.1UF"))
    )
    (comp (ref "C41")
      (value "1uF")
      (footprint "eagle-import:0402")
      (fields (field (name "PARTNO") "CL05A105KO5NNNC"))
      (libsource (lib "eagle-import") (part "C_0402_1UF"))
    )
    (comp (ref "C42")
      (value "0.1uF")
      (footprint "eagle-import:0402")
      (fields (field (name "PARTNO") "CL05F104ZO5NNNC"))
      (libsource (lib "eagle-import") (part "C_0402_0.1UF"))
    )
    (comp (ref "C43")
      (value "0.1uF")
      (footprint "eagle-import:0402")
      (fields (field (name "PARTNO") "CL05F104ZO5NNNC"))
      (libsource (lib "eagle-import") (part "C_0402_0.1UF"))
    )
    (comp (ref "FB1")
      (value "FB2_603")
      (footprint "eagle-import:0603")
      (fields (field (name "PARTNO") "BLM18PG121SN1D"))
      (libsource (lib "eagle-import") (part "FB_0603_120_OHM0603"))
    )
    (comp (ref "J1")
      (value "SD_CARD")
      (footprint "eagle-import:SD_CARD")
      (fields (field (name "MF") "Amphenol ICC") (field (name "PARTNO") "114-00841-68"))
      (libsource (lib "eagle-import") (part "SD_CARD_1140084168"))
    )
    (comp (ref "J2")
      (value "4-pos")
      (footprint "eagle-import:1X4_3.81MM_PITCH")
      (fields (field (name "PARTNO") "691322310004"))
      (libsource (lib "eagle-import") (part "3.81MM_1_X_4_RT_ANGLE_PLUG_HEADER"))
    )
    (comp (ref "J3")
      (value "10-pos")
      (footprint "eagle-import:2X5")
      (fields (field (name "PARTNO") "PH2RA-10-UA"))
      (libsource (lib "eagle-import") (part "CONN_05X2_RAPTH"))
    )
    (comp (ref "J4")
      (value "20-pos")
      (footprint "eagle-import:2_X_10_.1_INCH")
      (fields (field (name "PARTNO") "67996-420HLF"))
      (libsource (lib "eagle-import") (part "2_X_10_HEADER_GENERIC"))
    )
    (comp (ref "J5")
      (value "CONN_530470310_PICOBLADE_X_3")
      (footprint "eagle-import:CON_530470310_MOL")
      (fields
        (field (name "MANUFACTURER_PART_NUMBER") "530470310")
        (field (name "COPYRIGHT") "Copyright (C) 2022 Ultra Librarian. All rights reserved.")
      )
      (libsource (lib "eagle-import") (part "CONN_530470310_PICOBLADE_X_3"))
    )
    (comp (ref "J6")
      (value "USB-A")
      (footprint "eagle-import:USB_A_SMT")
      (fields (field (name "PARTNO") "87583-3010RPALF"))
      (libsource (lib "eagle-import") (part "USB_A"))
    )
    (comp (ref "J7")
      (value "USB-B-Micro")
      (footprint "eagle-import:USB_MICRO-B")
      (fields (field (name "PARTNO") "10118192-0002LF"))
      (libsource (lib "eagle-import") (part "USB_MICRO-B"))
    )
    (comp (ref "J8")
      (value "2_X_10_HEADER_GENERIC")
      (footprint "eagle-import:2_X_10_.1_INCH")
      (fields (field (name "PARTNO") "67996-420HLF"))
      (libsource (lib "eagle-import") (part "2_X_10_HEADER_GENERIC"))
    )
    (comp (ref "J9")
      (value "2-pos")
      (footprint "eagle-import:2_3.81MM_PITCH")
      (fields (field (name "PARTNO") "691322310002"))
      (libsource (lib "eagle-import") (part "3.81MM_1_X_2_RT_ANGLE_PLUG_HEADER"))
    )
    (comp (ref "J10")
      (value "CONN_530470310_PICOBLADE_X_3")
      (footprint "eagle-import:CON_530470310_MOL")
      (fields
        (field (name "MANUFACTURER_PART_NUMBER") "530470310")
        (field (name "COPYRIGHT") "Copyright (C) 2022 Ultra Librarian. All rights reserved.")
      )
      (libsource (lib "eagle-import") (part "CONN_530470310_PICOBLADE_X_3"))
    )
    (comp (ref "J11")
      (value "CONN_530470310_PICOBLADE_X_3")
      (footprint "eagle-import:CON_530470310_MOL")
      (fields
        (field (name "MANUFACTURER_PART_NUMBER") "530470310")
        (field (name "COPYRIGHT") "Copyright (C) 2022 Ultra Librarian. All rights reserved.")
      )
      (libsource (lib "eagle-import") (part "CONN_530470310_PICOBLADE_X_3"))
    )
    (comp (ref "J12")
      (value "CONN_530470310_PICOBLADE_X_3")
      (footprint "eagle-import:CON_530470310_MOL")
      (fields
        (field (name "MANUFACTURER_PART_NUMBER") "530470310")
        (field (name "COPYRIGHT") "Copyright (C) 2022 Ultra Librarian. All rights reserved.")
      )
      (libsource (lib "eagle-import") (part "CONN_530470310_PICOBLADE_X_3"))
    )
    (comp (ref "J13")
      (value "TEKNIC_MOTOR_8PIN")
      (footprint "eagle-import:CON_39281083")
      (fields
        (field (name "MANUFACTURER_PART_NUMBER") "39281083")
        (field (name "COPYRIGHT") "Copyright (C) 2022 Ultra Librarian. All rights reserved.")
      )
      (libsource (lib "eagle-import") (part "TEKNIC_MOTOR_8PIN"))
    )
    (comp (ref "J14")
      (value "TEKNIC_MOTOR_8PIN")
      (footprint "eagle-import:CON_39281083")
      (fields
        (field (name "MANUFACTURER_PART_NUMBER") "39281083")
        (field (name "COPYRIGHT") "Copyright (C) 2022 Ultra Librarian. All rights reserved.")
      )
      (libsource (lib "eagle-import") (part "TEKNIC_MOTOR_8PIN"))
    )
    (comp (ref "J15")
      (value "2-pos")
      (footprint "eagle-import:2_3.81MM_PITCH")
      (fields (field (name "PARTNO") "691322310002"))
      (libsource (lib "eagle-import") (part "3.81MM_1_X_2_RT_ANGLE_PLUG_HEADER"))
    )
    (comp (ref "J16")
      (value "2-pos")
      (footprint "eagle-import:2_3.81MM_PITCH")
      (fields (field (name "PARTNO") "691322310002"))
      (libsource (lib "eagle-import") (part "3.81MM_1_X_2_RT_ANGLE_PLUG_HEADER"))
    )
    (comp (ref "J17")
      (value "TEKNIC_MOTOR_8PIN")
      (footprint "eagle-import:CON_39281083")
      (fields
        (field (name "MANUFACTURER_PART_NUMBER") "39281083")
        (field (name "COPYRIGHT") "Copyright (C) 2022 Ultra Librarian. All rights reserved.")
      )
      (libsource (lib "eagle-import") (part "TEKNIC_MOTOR_8PIN"))
    )
    (comp (ref "J18")
      (value "TEKNIC_MOTOR_8PIN")
      (footprint "eagle-import:CON_39281083")
      (fields
        (field (name "MANUFACTURER_PART_NUMBER") "39281083")
        (field (name "COPYRIGHT") "Copyright (C) 2022 Ultra Librarian. All rights reserved.")
      )
      (libsource (lib "eagle-import") (part "TEKNIC_MOTOR_8PIN"))
    )
    (comp (ref "J19")
      (value "CONN_530470310_PICOBLADE_X_3")
      (footprint "eagle-import:CON_530470310_MOL")
      (fields
        (field (name "MANUFACTURER_PART_NUMBER") "530470310")
        (field (name "COPYRIGHT") "Copyright (C) 2022 Ultra Librarian. All rights reserved.")
      )
      (libsource (lib "eagle-import") (part "CONN_530470310_PICOBLADE_X_3"))
    )
    (comp (ref "J20")
      (value "CONN_530470310_PICOBLADE_X_3")
      (footprint "eagle-import:CON_530470310_MOL")
      (fields
        (field (name "MANUFACTURER_PART_NUMBER") "530470310")
        (field (name "COPYRIGHT") "Copyright (C) 2022 Ultra Librarian. All rights reserved.")
      )
      (libsource (lib "eagle-import") (part "CONN_530470310_PICOBLADE_X_3"))
    )
    (comp (ref "J21")
      (value "TEKNIC_MOTOR_8PIN")
      (footprint "eagle-import:CON_39281083")
      (fields
        (field (name "MANUFACTURER_PART_NUMBER") "39281083")
        (field (name "COPYRIGHT") "Copyright (C) 2022 Ultra Librarian. All rights reserved.")
      )
      (libsource (lib "eagle-import") (part "TEKNIC_MOTOR_8PIN"))
    )
    (comp (ref "J22")
      (value "TEKNIC_MOTOR_8PIN")
      (footprint "eagle-import:CON_39281083")
      (fields
        (field (name "MANUFACTURER_PART_NUMBER") "39281083")
        (field (name "COPYRIGHT") "Copyright (C) 2022 Ultra Librarian. All rights reserved.")
      )
      (libsource (lib "eagle-import") (part "TEKNIC_MOTOR_8PIN"))
    )
    (comp (ref "J23")
      (value "2-pos")
      (footprint "eagle-import:2_3.81MM_PITCH")
      (fields (field (name "PARTNO") "691322310002"))
      (libsource (lib "eagle-import") (part "3.81MM_1_X_2_RT_ANGLE_PLUG_HEADER"))
    )
    (comp (ref "J24")
      (value "2-pos")
      (footprint "eagle-import:2_3.81MM_PITCH")
      (fields (field (name "PARTNO") "691322310002"))
      (libsource (lib "eagle-import") (part "3.81MM_1_X_2_RT_ANGLE_PLUG_HEADER"))
    )
    (comp (ref "J25")
      (value "TEKNIC_MOTOR_8PIN")
      (footprint "eagle-import:CON_39281083")
      (fields
        (field (name "MANUFACTURER_PART_NUMBER") "39281083")
        (field (name "COPYRIGHT") "Copyright (C) 2022 Ultra Librarian. All rights reserved.")
      )
      (libsource (lib "eagle-import") (part "TEKNIC_MOTOR_8PIN"))
    )
    (comp (ref "J26")
      (value "TEKNIC_MOTOR_8PIN")
      (footprint "eagle-import:CON_39281083")
      (fields
        (field (name "MANUFACTURER_PART_NUMBER") "39281083")
        (field (name "COPYRIGHT") "Copyright (C) 2022 Ultra Librarian. All rights reserved.")
      )
      (libsource (lib "eagle-import") (part "TEKNIC_MOTOR_8PIN"))
    )
    (comp (ref "J27")
      (value "CONN_530470310_PICOBLADE_X_3")
      (footprint "eagle-import:CON_530470310_MOL")
      (fields
        (field (name "MANUFACTURER_PART_NUMBER") "530470310")
        (field (name "COPYRIGHT") "Copyright (C) 2022 Ultra Librarian. All rights reserved.")
      )
      (libsource (lib "eagle-import") (part "CONN_530470310_PICOBLADE_X_3"))
    )
    (comp (ref "J28")
      (value "CONN_530470310_PICOBLADE_X_3")
      (footprint "eagle-import:CON_530470310_MOL")
      (fields
        (field (name "MANUFACTURER_PART_NUMBER") "530470310")
        (field (name "COPYRIGHT") "Copyright (C) 2022 Ultra Librarian. All rights reserved.")
      )
      (libsource (lib "eagle-import") (part "CONN_530470310_PICOBLADE_X_3"))
    )
    (comp (ref "J29")
      (value "TEKNIC_MOTOR_8PIN")
      (footprint "eagle-import:CON_39281083")
      (fields
        (field (name "MANUFACTURER_PART_NUMBER") "39281083")
        (field (name "COPYRIGHT") "Copyright (C) 2022 Ultra Librarian. All rights reserved.")
      )
      (libsource (lib "eagle-import") (part "TEKNIC_MOTOR_8PIN"))
    )
    (comp (ref "J30")
      (value "TEKNIC_MOTOR_8PIN")
      (footprint "eagle-import:CON_39281083")
      (fields
        (field (name "MANUFACTURER_PART_NUMBER") "39281083")
        (field (name "COPYRIGHT") "Copyright (C) 2022 Ultra Librarian. All rights reserved.")
      )
      (libsource (lib "eagle-import") (part "TEKNIC_MOTOR_8PIN"))
    )
    (comp (ref "J31")
      (value "CONN_530470310_PICOBLADE_X_3")
      (footprint "eagle-import:CON_530470310_MOL")
      (fields
        (field (name "MANUFACTURER_PART_NUMBER") "530470310")
        (field (name "COPYRIGHT") "Copyright (C) 2022 Ultra Librarian. All rights reserved.")
      )
      (libsource (lib "eagle-import") (part "CONN_530470310_PICOBLADE_X_3"))
    )
    (comp (ref "J32")
      (value "CONN_530470310_PICOBLADE_X_3")
      (footprint "eagle-import:CON_530470310_MOL")
      (fields
        (field (name "MANUFACTURER_PART_NUMBER") "530470310")
        (field (name "COPYRIGHT") "Copyright (C) 2022 Ultra Librarian. All rights reserved.")
      )
      (libsource (lib "eagle-import") (part "CONN_530470310_PICOBLADE_X_3"))
    )
    (comp (ref "J33")
      (value "TEKNIC_MOTOR_8PIN")
      (footprint "eagle-import:CON_39281083")
      (fields
        (field (name "MANUFACTURER_PART_NUMBER") "39281083")
        (field (name "COPYRIGHT") "Copyright (C) 2022 Ultra Librarian. All rights reserved.")
      )
      (libsource (lib "eagle-import") (part "TEKNIC_MOTOR_8PIN"))
    )
    (comp (ref "J34")
      (value "TEKNIC_MOTOR_8PIN")
      (footprint "eagle-import:CON_39281083")
      (fields
        (field (name "MANUFACTURER_PART_NUMBER") "39281083")
        (field (name "COPYRIGHT") "Copyright (C) 2022 Ultra Librarian. All rights reserved.")
      )
      (libsource (lib "eagle-import") (part "TEKNIC_MOTOR_8PIN"))
    )
    (comp (ref "L1")
      (value "2.2uH")
      (footprint "eagle-import:1008")
      (fields (field (name "PARTNO") "LQM2HPN2R2MG0L"))
      (libsource (lib "eagle-import") (part "INDUCTOR_1008_2.2_MH_1.3A"))
    )
    (comp (ref "LED1")
      (value "Green")
      (footprint "eagle-import:0805")
      (fields (field (name "PARTNO") "LG R971-KN-1"))
      (libsource (lib "eagle-import") (part "LED_0805_GREEN"))
    )
    (comp (ref "LED3")
      (value "Green")
      (footprint "eagle-import:0805")
      (fields (field (name "PARTNO") "LG R971-KN-1"))
      (libsource (lib "eagle-import") (part "LED_0805_GREEN"))
    )
    (comp (ref "LED4")
      (value "Green")
      (footprint "eagle-import:0805")
      (fields (field (name "PARTNO") "LG R971-KN-1"))
      (libsource (lib "eagle-import") (part "LED_0805_GREEN"))
    )
    (comp (ref "LED5")
      (value "Green")
      (footprint "eagle-import:0805")
      (fields (field (name "PARTNO") "LG R971-KN-1"))
      (libsource (lib "eagle-import") (part "LED_0805_GREEN"))
    )
    (comp (ref "LED6")
      (value "Green")
      (footprint "eagle-import:0805")
      (fields (field (name "PARTNO") "LG R971-KN-1"))
      (libsource (lib "eagle-import") (part "LED_0805_GREEN"))
    )
    (comp (ref "LED7")
      (value "Green")
      (footprint "eagle-import:0805")
      (fields (field (name "PARTNO") "LG R971-KN-1"))
      (libsource (lib "eagle-import") (part "LED_0805_GREEN"))
    )
    (comp (ref "LED8")
      (value "Green")
      (footprint "eagle-import:0805")
      (fields (field (name "PARTNO") "LG R971-KN-1"))
      (libsource (lib "eagle-import") (part "LED_0805_GREEN"))
    )
    (comp (ref "LED9")
      (value "Green")
      (footprint "eagle-import:0805")
      (fields (field (name "PARTNO") "LG R971-KN-1"))
      (libsource (lib "eagle-import") (part "LED_0805_GREEN"))
    )
    (comp (ref "LED10")
      (value "Green")
      (footprint "eagle-import:0805")
      (fields (field (name "PARTNO") "LG R971-KN-1"))
      (libsource (lib "eagle-import") (part "LED_0805_GREEN"))
    )
    (comp (ref "LED11")
      (value "Green")
      (footprint "eagle-import:0805")
      (fields (field (name "PARTNO") "LG R971-KN-1"))
      (libsource (lib "eagle-import") (part "LED_0805_GREEN"))
    )
    (comp (ref "LED12")
      (value "Green")
      (footprint "eagle-import:0805")
      (fields (field (name "PARTNO") "LG R971-KN-1"))
      (libsource (lib "eagle-import") (part "LED_0805_GREEN"))
    )
    (comp (ref "LED13")
      (value "Green")
      (footprint "eagle-import:0805")
      (fields (field (name "PARTNO") "LG R971-KN-1"))
      (libsource (lib "eagle-import") (part "LED_0805_GREEN"))
    )
    (comp (ref "LED14")
      (value "Green")
      (footprint "eagle-import:0805")
      (fields (field (name "PARTNO") "LG R971-KN-1"))
      (libsource (lib "eagle-import") (part "LED_0805_GREEN"))
    )
    (comp (ref "LED15")
      (value "Green")
      (footprint "eagle-import:0805")
      (fields (field (name "PARTNO") "LG R971-KN-1"))
      (libsource (lib "eagle-import") (part "LED_0805_GREEN"))
    )
    (comp (ref "LED16")
      (value "Green")
      (footprint "eagle-import:0805")
      (fields (field (name "PARTNO") "LG R971-KN-1"))
      (libsource (lib "eagle-import") (part "LED_0805_GREEN"))
    )
    (comp (ref "R1")
      (value "6K49")
      (footprint "eagle-import:0402")
      (fields (field (name "PARTNO") "RMCF0402FT6K49"))
      (libsource (lib "eagle-import") (part "R_0402_6K49"))
    )
    (comp (ref "R2")
      (value "10K0")
      (footprint "eagle-import:0402")
      (fields (field (name "PARTNO") "RMCF0402JT10K0"))
      (libsource (lib "eagle-import") (part "R_0402_10K0"))
    )
    (comp (ref "R3")
      (value "10K0")
      (footprint "eagle-import:0402")
      (fields (field (name "PARTNO") "RMCF0402JT10K0"))
      (libsource (lib "eagle-import") (part "R_0402_10K0"))
    )
    (comp (ref "R4")
      (value "1K5")
      (footprint "eagle-import:0402")
      (fields (field (name "PARTNO") "RMCF0402JT1K50"))
      (libsource (lib "eagle-import") (part "R_0402_1K5"))
    )
    (comp (ref "R5")
      (value "470R0")
      (footprint "eagle-import:0402")
      (fields (field (name "PARTNO") "RMCF0402JT470R"))
      (libsource (lib "eagle-import") (part "R_0402_470R0"))
    )
    (comp (ref "R6")
      (value "1K5")
      (footprint "eagle-import:0402")
      (fields (field (name "PARTNO") "RMCF0402JT1K50"))
      (libsource (lib "eagle-import") (part "R_0402_1K5"))
    )
    (comp (ref "R7")
      (value "470R0")
      (footprint "eagle-import:0402")
      (fields (field (name "PARTNO") "RMCF0402JT470R"))
      (libsource (lib "eagle-import") (part "R_0402_470R0"))
    )
    (comp (ref "R8")
      (value "470R0")
      (footprint "eagle-import:0402")
      (fields (field (name "PARTNO") "RMCF0402JT470R"))
      (libsource (lib "eagle-import") (part "R_0402_470R0"))
    )
    (comp (ref "R9")
      (value "33R0")
      (footprint "eagle-import:0402")
      (fields (field (name "PARTNO") "RMCF0402JT33R0"))
      (libsource (lib "eagle-import") (part "R_0402_33R0"))
    )
    (comp (ref "R10")
      (value "33R0")
      (footprint "eagle-import:0402")
      (fields (field (name "PARTNO") "RMCF0402JT33R0"))
      (libsource (lib "eagle-import") (part "R_0402_33R0"))
    )
    (comp (ref "R11")
      (value "33R0")
      (footprint "eagle-import:0402")
      (fields (field (name "PARTNO") "RMCF0402JT33R0"))
      (libsource (lib "eagle-import") (part "R_0402_33R0"))
    )
    (comp (ref "R12")
      (value "33R0")
      (footprint "eagle-import:0402")
      (fields (field (name "PARTNO") "RMCF0402JT33R0"))
      (libsource (lib "eagle-import") (part "R_0402_33R0"))
    )
    (comp (ref "R13")
      (value "10K0")
      (footprint "eagle-import:0402")
      (fields (field (name "PARTNO") "RMCF0402JT10K0"))
      (libsource (lib "eagle-import") (part "R_0402_10K0"))
    )
    (comp (ref "R14")
      (value "1K0")
      (footprint "eagle-import:0402")
      (fields (field (name "PARTNO") "CRG0402J1K0"))
      (libsource (lib "eagle-import") (part "R_0402_1K0"))
    )
    (comp (ref "R15")
      (value "1K0")
      (footprint "eagle-import:0402")
      (fields (field (name "PARTNO") "CRG0402J1K0"))
      (libsource (lib "eagle-import") (part "R_0402_1K0"))
    )
    (comp (ref "R16")
      (value "15K0")
      (footprint "eagle-import:0402")
      (fields (field (name "PARTNO") "RMCF0402JT15K0"))
      (libsource (lib "eagle-import") (part "R_0402_15K0"))
    )
    (comp (ref "R17")
      (value "27R0")
      (footprint "eagle-import:0402")
      (fields (field (name "PARTNO") "RMCF0402JT27R0"))
      (libsource (lib "eagle-import") (part "R_0402_27R0"))
    )
    (comp (ref "R18")
      (value "27R0")
      (footprint "eagle-import:0402")
      (fields (field (name "PARTNO") "RMCF0402JT27R0"))
      (libsource (lib "eagle-import") (part "R_0402_27R0"))
    )
    (comp (ref "R19")
      (value "10K0")
      (footprint "eagle-import:0402")
      (fields (field (name "PARTNO") "RMCF0402JT10K0"))
      (libsource (lib "eagle-import") (part "R_0402_10K0"))
    )
    (comp (ref "R20")
      (value "10K0")
      (footprint "eagle-import:0402")
      (fields (field (name "PARTNO") "RMCF0402JT10K0"))
      (libsource (lib "eagle-import") (part "R_0402_10K0"))
    )
    (comp (ref "R21")
      (value "30K0")
      (footprint "eagle-import:0402")
      (fields (field (name "PARTNO") "RC0402JR-0730KL"))
      (libsource (lib "eagle-import") (part "R_0402_30K0"))
    )
    (comp (ref "R22")
      (value "2K2")
      (footprint "eagle-import:0402")
      (fields (field (name "PARTNO") "RMCF0402JT2K20"))
      (libsource (lib "eagle-import") (part "R_0402_2K2"))
    )
    (comp (ref "R23")
      (value "10K0")
      (footprint "eagle-import:0402")
      (fields (field (name "PARTNO") "RMCF0402JT10K0"))
      (libsource (lib "eagle-import") (part "R_0402_10K0"))
    )
    (comp (ref "R24")
      (value "10K0")
      (footprint "eagle-import:0402")
      (fields (field (name "PARTNO") "RMCF0402JT10K0"))
      (libsource (lib "eagle-import") (part "R_0402_10K0"))
    )
    (comp (ref "R25")
      (value "100K")
      (footprint "eagle-import:0402")
      (libsource (lib "eagle-import") (part "R_0402"))
    )
    (comp (ref "R27")
      (value "100K")
      (footprint "eagle-import:0402")
      (libsource (lib "eagle-import") (part "R_0402"))
    )
    (comp (ref "R28")
      (value "2K2")
      (footprint "eagle-import:0402")
      (libsource (lib "eagle-import") (part "R_0402"))
    )
    (comp (ref "R29")
      (value "470R0")
      (footprint "eagle-import:0402")
      (libsource (lib "eagle-import") (part "R_0402"))
    )
    (comp (ref "R30")
      (value "470R0")
      (footprint "eagle-import:0402")
      (libsource (lib "eagle-import") (part "R_0402"))
    )
    (comp (ref "R31")
      (value "470R0")
      (footprint "eagle-import:0402")
      (fields (field (name "PARTNO") "RMCF0402JT470R"))
      (libsource (lib "eagle-import") (part "R_0402_470R0"))
    )
    (comp (ref "R32")
      (value "470R0")
      (footprint "eagle-import:0402")
      (fields (field (name "PARTNO") "RMCF0402JT470R"))
      (libsource (lib "eagle-import") (part "R_0402_470R0"))
    )
    (comp (ref "R33")
      (value "470R0")
      (footprint "eagle-import:0402")
      (fields (field (name "PARTNO") "RMCF0402JT470R"))
      (libsource (lib "eagle-import") (part "R_0402_470R0"))
    )
    (comp (ref "R34")
      (value "10K0")
      (footprint "eagle-import:0402")
      (fields (field (name "PARTNO") "RMCF0402JT10K0"))
      (libsource (lib "eagle-import") (part "R_0402_10K0"))
    )
    (comp (ref "R35")
      (value "2K2")
      (footprint "eagle-import:0402")
      (libsource (lib "eagle-import") (part "R_0402"))
    )
    (comp (ref "R36")
      (value "470R0")
      (footprint "eagle-import:0402")
      (fields (field (name "PARTNO") "RMCF0402JT470R"))
      (libsource (lib "eagle-import") (part "R_0402_470R0"))
    )
    (comp (ref "R37")
      (value "1k")
      (footprint "eagle-import:0805")
      (libsource (lib "eagle-import") (part "R_0805"))
    )
    (comp (ref "R38")
      (value "33R0")
      (footprint "eagle-import:0402")
      (fields (field (name "PARTNO") "RMCF0402JT33R0"))
      (libsource (lib "eagle-import") (part "R_0402_33R0"))
    )
    (comp (ref "R39")
      (value "33R0")
      (footprint "eagle-import:0402")
      (fields (field (name "PARTNO") "RMCF0402JT33R0"))
      (libsource (lib "eagle-import") (part "R_0402_33R0"))
    )
    (comp (ref "R40")
      (value "33R0")
      (footprint "eagle-import:0402")
      (fields (field (name "PARTNO") "RMCF0402JT33R0"))
      (libsource (lib "eagle-import") (part "R_0402_33R0"))
    )
    (comp (ref "R41")
      (value "1k")
      (footprint "eagle-import:0805")
      (libsource (lib "eagle-import") (part "R_0805"))
    )
    (comp (ref "R42")
      (value "1k")
      (footprint "eagle-import:0805")
      (libsource (lib "eagle-import") (part "R_0805"))
    )
    (comp (ref "R43")
      (value "1k")
      (footprint "eagle-import:0805")
      (libsource (lib "eagle-import") (part "R_0805"))
    )
    (comp (ref "R44")
      (value "33R0")
      (footprint "eagle-import:0402")
      (fields (field (name "PARTNO") "RMCF0402JT33R0"))
      (libsource (lib "eagle-import") (part "R_0402_33R0"))
    )
    (comp (ref "R45")
      (value "33R0")
      (footprint "eagle-import:0402")
      (fields (field (name "PARTNO") "RMCF0402JT33R0"))
      (libsource (lib "eagle-import") (part "R_0402_33R0"))
    )
    (comp (ref "R46")
      (value "33R0")
      (footprint "eagle-import:0402")
      (fields (field (name "PARTNO") "RMCF0402JT33R0"))
      (libsource (lib "eagle-import") (part "R_0402_33R0"))
    )
    (comp (ref "R47")
      (value "1k")
      (footprint "eagle-import:0805")
      (libsource (lib "eagle-import") (part "R_0805"))
    )
    (comp (ref "R48")
      (value "1k")
      (footprint "eagle-import:0805")
      (libsource (lib "eagle-import") (part "R_0805"))
    )
    (comp (ref "R49")
      (value "470R0")
      (footprint "eagle-import:0402")
      (libsource (lib "eagle-import") (part "R_0402"))
    )
    (comp (ref "R50")
      (value "470R0")
      (footprint "eagle-import:0402")
      (libsource (lib "eagle-import") (part "R_0402"))
    )
    (comp (ref "R51")
      (value "470R0")
      (footprint "eagle-import:0402")
      (fields (field (name "PARTNO") "RMCF0402JT470R"))
      (libsource (lib "eagle-import") (part "R_0402_470R0"))
    )
    (comp (ref "R52")
      (value "470R0")
      (footprint "eagle-import:0402")
      (fields (field (name "PARTNO") "RMCF0402JT470R"))
      (libsource (lib "eagle-import") (part "R_0402_470R0"))
    )
    (comp (ref "R53")
      (value "10K0")
      (footprint "eagle-import:0402")
      (fields (field (name "PARTNO") "RMCF0402JT10K0"))
      (libsource (lib "eagle-import") (part "R_0402_10K0"))
    )
    (comp (ref "R54")
      (value "2K2")
      (footprint "eagle-import:0402")
      (libsource (lib "eagle-import") (part "R_0402"))
    )
    (comp (ref "R55")
      (value "470R0")
      (footprint "eagle-import:0402")
      (fields (field (name "PARTNO") "RMCF0402JT470R"))
      (libsource (lib "eagle-import") (part "R_0402_470R0"))
    )
    (comp (ref "R56")
      (value "10K0")
      (footprint "eagle-import:0402")
      (fields (field (name "PARTNO") "RMCF0402JT10K0"))
      (libsource (lib "eagle-import") (part "R_0402_10K0"))
    )
    (comp (ref "R57")
      (value "2K2")
      (footprint "eagle-import:0402")
      (libsource (lib "eagle-import") (part "R_0402"))
    )
    (comp (ref "R58")
      (value "470R0")
      (footprint "eagle-import:0402")
      (fields (field (name "PARTNO") "RMCF0402JT470R"))
      (libsource (lib "eagle-import") (part "R_0402_470R0"))
    )
    (comp (ref "R59")
      (value "10K0")
      (footprint "eagle-import:0402")
      (fields (field (name "PARTNO") "RMCF0402JT10K0"))
      (libsource (lib "eagle-import") (part "R_0402_10K0"))
    )
    (comp (ref "R60")
      (value "2K2")
      (footprint "eagle-import:0402")
      (libsource (lib "eagle-import") (part "R_0402"))
    )
    (comp (ref "R61")
      (value "1k")
      (footprint "eagle-import:0805")
      (libsource (lib "eagle-import") (part "R_0805"))
    )
    (comp (ref "R62")
      (value "33R0")
      (footprint "eagle-import:0402")
      (fields (field (name "PARTNO") "RMCF0402JT33R0"))
      (libsource (lib "eagle-import") (part "R_0402_33R0"))
    )
    (comp (ref "R63")
      (value "33R0")
      (footprint "eagle-import:0402")
      (fields (field (name "PARTNO") "RMCF0402JT33R0"))
      (libsource (lib "eagle-import") (part "R_0402_33R0"))
    )
    (comp (ref "R64")
      (value "33R0")
      (footprint "eagle-import:0402")
      (fields (field (name "PARTNO") "RMCF0402JT33R0"))
      (libsource (lib "eagle-import") (part "R_0402_33R0"))
    )
    (comp (ref "R65")
      (value "1k")
      (footprint "eagle-import:0805")
      (libsource (lib "eagle-import") (part "R_0805"))
    )
    (comp (ref "R66")
      (value "1k")
      (footprint "eagle-import:0805")
      (libsource (lib "eagle-import") (part "R_0805"))
    )
    (comp (ref "R67")
      (value "1k")
      (footprint "eagle-import:0805")
      (libsource (lib "eagle-import") (part "R_0805"))
    )
    (comp (ref "R68")
      (value "33R0")
      (footprint "eagle-import:0402")
      (fields (field (name "PARTNO") "RMCF0402JT33R0"))
      (libsource (lib "eagle-import") (part "R_0402_33R0"))
    )
    (comp (ref "R69")
      (value "33R0")
      (footprint "eagle-import:0402")
      (fields (field (name "PARTNO") "RMCF0402JT33R0"))
      (libsource (lib "eagle-import") (part "R_0402_33R0"))
    )
    (comp (ref "R70")
      (value "33R0")
      (footprint "eagle-import:0402")
      (fields (field (name "PARTNO") "RMCF0402JT33R0"))
      (libsource (lib "eagle-import") (part "R_0402_33R0"))
    )
    (comp (ref "R71")
      (value "1k")
      (footprint "eagle-import:0805")
      (libsource (lib "eagle-import") (part "R_0805"))
    )
    (comp (ref "R72")
      (value "1k")
      (footprint "eagle-import:0805")
      (libsource (lib "eagle-import") (part "R_0805"))
    )
    (comp (ref "R73")
      (value "470R0")
      (footprint "eagle-import:0402")
      (fields (field (name "PARTNO") "RMCF0402JT470R"))
      (libsource (lib "eagle-import") (part "R_0402_470R0"))
    )
    (comp (ref "R74")
      (value "10K0")
      (footprint "eagle-import:0402")
      (fields (field (name "PARTNO") "RMCF0402JT10K0"))
      (libsource (lib "eagle-import") (part "R_0402_10K0"))
    )
    (comp (ref "R75")
      (value "2K2")
      (footprint "eagle-import:0402")
      (libsource (lib "eagle-import") (part "R_0402"))
    )
    (comp (ref "R76")
      (value "470R0")
      (footprint "eagle-import:0402")
      (fields (field (name "PARTNO") "RMCF0402JT470R"))
      (libsource (lib "eagle-import") (part "R_0402_470R0"))
    )
    (comp (ref "R77")
      (value "10K0")
      (footprint "eagle-import:0402")
      (fields (field (name "PARTNO") "RMCF0402JT10K0"))
      (libsource (lib "eagle-import") (part "R_0402_10K0"))
    )
    (comp (ref "R78")
      (value "2K2")
      (footprint "eagle-import:0402")
      (libsource (lib "eagle-import") (part "R_0402"))
    )
    (comp (ref "R79")
      (value "470R0")
      (footprint "eagle-import:0402")
      (fields (field (name "PARTNO") "RMCF0402JT470R"))
      (libsource (lib "eagle-import") (part "R_0402_470R0"))
    )
    (comp (ref "R80")
      (value "10K0")
      (footprint "eagle-import:0402")
      (fields (field (name "PARTNO") "RMCF0402JT10K0"))
      (libsource (lib "eagle-import") (part "R_0402_10K0"))
    )
    (comp (ref "R81")
      (value "2K2")
      (footprint "eagle-import:0402")
      (libsource (lib "eagle-import") (part "R_0402"))
    )
    (comp (ref "R82")
      (value "470R0")
      (footprint "eagle-import:0402")
      (fields (field (name "PARTNO") "RMCF0402JT470R"))
      (libsource (lib "eagle-import") (part "R_0402_470R0"))
    )
    (comp (ref "R83")
      (value "10K0")
      (footprint "eagle-import:0402")
      (fields (field (name "PARTNO") "RMCF0402JT10K0"))
      (libsource (lib "eagle-import") (part "R_0402_10K0"))
    )
    (comp (ref "R84")
      (value "2K2")
      (footprint "eagle-import:0402")
      (libsource (lib "eagle-import") (part "R_0402"))
    )
    (comp (ref "R85")
      (value "1k")
      (footprint "eagle-import:0805")
      (libsource (lib "eagle-import") (part "R_0805"))
    )
    (comp (ref "R86")
      (value "33R0")
      (footprint "eagle-import:0402")
      (fields (field (name "PARTNO") "RMCF0402JT33R0"))
      (libsource (lib "eagle-import") (part "R_0402_33R0"))
    )
    (comp (ref "R87")
      (value "33R0")
      (footprint "eagle-import:0402")
      (fields (field (name "PARTNO") "RMCF0402JT33R0"))
      (libsource (lib "eagle-import") (part "R_0402_33R0"))
    )
    (comp (ref "R88")
      (value "33R0")
      (footprint "eagle-import:0402")
      (fields (field (name "PARTNO") "RMCF0402JT33R0"))
      (libsource (lib "eagle-import") (part "R_0402_33R0"))
    )
    (comp (ref "R89")
      (value "1k")
      (footprint "eagle-import:0805")
      (libsource (lib "eagle-import") (part "R_0805"))
    )
    (comp (ref "R90")
      (value "1k")
      (footprint "eagle-import:0805")
      (libsource (lib "eagle-import") (part "R_0805"))
    )
    (comp (ref "R91")
      (value "1k")
      (footprint "eagle-import:0805")
      (libsource (lib "eagle-import") (part "R_0805"))
    )
    (comp (ref "R92")
      (value "33R0")
      (footprint "eagle-import:0402")
      (fields (field (name "PARTNO") "RMCF0402JT33R0"))
      (libsource (lib "eagle-import") (part "R_0402_33R0"))
    )
    (comp (ref "R93")
      (value "33R0")
      (footprint "eagle-import:0402")
      (fields (field (name "PARTNO") "RMCF0402JT33R0"))
      (libsource (lib "eagle-import") (part "R_0402_33R0"))
    )
    (comp (ref "R94")
      (value "33R0")
      (footprint "eagle-import:0402")
      (fields (field (name "PARTNO") "RMCF0402JT33R0"))
      (libsource (lib "eagle-import") (part "R_0402_33R0"))
    )
    (comp (ref "R95")
      (value "1k")
      (footprint "eagle-import:0805")
      (libsource (lib "eagle-import") (part "R_0805"))
    )
    (comp (ref "R96")
      (value "1k")
      (footprint "eagle-import:0805")
      (libsource (lib "eagle-import") (part "R_0805"))
    )
    (comp (ref "R97")
      (value "470R0")
      (footprint "eagle-import:0402")
      (fields (field (name "PARTNO") "RMCF0402JT470R"))
      (libsource (lib "eagle-import") (part "R_0402_470R0"))
    )
    (comp (ref "R98")
      (value "10K0")
      (footprint "eagle-import:0402")
      (fields (field (name "PARTNO") "RMCF0402JT10K0"))
      (libsource (lib "eagle-import") (part "R_0402_10K0"))
    )
    (comp (ref "R99")
      (value "2K2")
      (footprint "eagle-import:0402")
      (libsource (lib "eagle-import") (part "R_0402"))
    )
    (comp (ref "R100")
      (value "470R0")
      (footprint "eagle-import:0402")
      (fields (field (name "PARTNO") "RMCF0402JT470R"))
      (libsource (lib "eagle-import") (part "R_0402_470R0"))
    )
    (comp (ref "R101")
      (value "10K0")
      (footprint "eagle-import:0402")
      (fields (field (name "PARTNO") "RMCF0402JT10K0"))
      (libsource (lib "eagle-import") (part "R_0402_10K0"))
    )
    (comp (ref "R102")
      (value "100K")
      (footprint "eagle-import:0402")
      (libsource (lib "eagle-import") (part "R_0402"))
    )
    (comp (ref "R103")
      (value "100K")
      (footprint "eagle-import:0402")
      (libsource (lib "eagle-import") (part "R_0402"))
    )
    (comp (ref "R105")
      (value "100K")
      (footprint "eagle-import:0402")
      (libsource (lib "eagle-import") (part "R_0402"))
    )
    (comp (ref "R106")
      (value "100K")
      (footprint "eagle-import:0402")
      (libsource (lib "eagle-import") (part "R_0402"))
    )
    (comp (ref "R107")
      (value "100K")
      (footprint "eagle-import:0402")
      (libsource (lib "eagle-import") (part "R_0402"))
    )
    (comp (ref "R108")
      (value "100K")
      (footprint "eagle-import:0402")
      (libsource (lib "eagle-import") (part "R_0402"))
    )
    (comp (ref "R109")
      (value "1k")
      (footprint "eagle-import:0805")
      (libsource (lib "eagle-import") (part "R_0805"))
    )
    (comp (ref "R110")
      (value "33R0")
      (footprint "eagle-import:0402")
      (fields (field (name "PARTNO") "RMCF0402JT33R0"))
      (libsource (lib "eagle-import") (part "R_0402_33R0"))
    )
    (comp (ref "R111")
      (value "33R0")
      (footprint "eagle-import:0402")
      (fields (field (name "PARTNO") "RMCF0402JT33R0"))
      (libsource (lib "eagle-import") (part "R_0402_33R0"))
    )
    (comp (ref "R112")
      (value "33R0")
      (footprint "eagle-import:0402")
      (fields (field (name "PARTNO") "RMCF0402JT33R0"))
      (libsource (lib "eagle-import") (part "R_0402_33R0"))
    )
    (comp (ref "R113")
      (value "1k")
      (footprint "eagle-import:0805")
      (libsource (lib "eagle-import") (part "R_0805"))
    )
    (comp (ref "R114")
      (value "1k")
      (footprint "eagle-import:0805")
      (libsource (lib "eagle-import") (part "R_0805"))
    )
    (comp (ref "R115")
      (value "1k")
      (footprint "eagle-import:0805")
      (libsource (lib "eagle-import") (part "R_0805"))
    )
    (comp (ref "R116")
      (value "33R0")
      (footprint "eagle-import:0402")
      (fields (field (name "PARTNO") "RMCF0402JT33R0"))
      (libsource (lib "eagle-import") (part "R_0402_33R0"))
    )
    (comp (ref "R117")
      (value "33R0")
      (footprint "eagle-import:0402")
      (fields (field (name "PARTNO") "RMCF0402JT33R0"))
      (libsource (lib "eagle-import") (part "R_0402_33R0"))
    )
    (comp (ref "R118")
      (value "33R0")
      (footprint "eagle-import:0402")
      (fields (field (name "PARTNO") "RMCF0402JT33R0"))
      (libsource (lib "eagle-import") (part "R_0402_33R0"))
    )
    (comp (ref "R119")
      (value "1k")
      (footprint "eagle-import:0805")
      (libsource (lib "eagle-import") (part "R_0805"))
    )
    (comp (ref "R120")
      (value "1k")
      (footprint "eagle-import:0805")
      (libsource (lib "eagle-import") (part "R_0805"))
    )
    (comp (ref "R133")
      (value "1k")
      (footprint "eagle-import:0805")
      (libsource (lib "eagle-import") (part "R_0805"))
    )
    (comp (ref "R134")
      (value "33R0")
      (footprint "eagle-import:0402")
      (fields (field (name "PARTNO") "RMCF0402JT33R0"))
      (libsource (lib "eagle-import") (part "R_0402_33R0"))
    )
    (comp (ref "R135")
      (value "33R0")
      (footprint "eagle-import:0402")
      (fields (field (name "PARTNO") "RMCF0402JT33R0"))
      (libsource (lib "eagle-import") (part "R_0402_33R0"))
    )
    (comp (ref "R136")
      (value "33R0")
      (footprint "eagle-import:0402")
      (fields (field (name "PARTNO") "RMCF0402JT33R0"))
      (libsource (lib "eagle-import") (part "R_0402_33R0"))
    )
    (comp (ref "R137")
      (value "1k")
      (footprint "eagle-import:0805")
      (libsource (lib "eagle-import") (part "R_0805"))
    )
    (comp (ref "R138")
      (value "1k")
      (footprint "eagle-import:0805")
      (libsource (lib "eagle-import") (part "R_0805"))
    )
    (comp (ref "R139")
      (value "1k")
      (footprint "eagle-import:0805")
      (libsource (lib "eagle-import") (part "R_0805"))
    )
    (comp (ref "R140")
      (value "33R0")
      (footprint "eagle-import:0402")
      (fields (field (name "PARTNO") "RMCF0402JT33R0"))
      (libsource (lib "eagle-import") (part "R_0402_33R0"))
    )
    (comp (ref "R141")
      (value "33R0")
      (footprint "eagle-import:0402")
      (fields (field (name "PARTNO") "RMCF0402JT33R0"))
      (libsource (lib "eagle-import") (part "R_0402_33R0"))
    )
    (comp (ref "R142")
      (value "33R0")
      (footprint "eagle-import:0402")
      (fields (field (name "PARTNO") "RMCF0402JT33R0"))
      (libsource (lib "eagle-import") (part "R_0402_33R0"))
    )
    (comp (ref "R143")
      (value "1k")
      (footprint "eagle-import:0805")
      (libsource (lib "eagle-import") (part "R_0805"))
    )
    (comp (ref "R144")
      (value "1k")
      (footprint "eagle-import:0805")
      (libsource (lib "eagle-import") (part "R_0805"))
    )
    (comp (ref "R157")
      (value "1k")
      (footprint "eagle-import:0805")
      (libsource (lib "eagle-import") (part "R_0805"))
    )
    (comp (ref "R158")
      (value "33R0")
      (footprint "eagle-import:0402")
      (fields (field (name "PARTNO") "RMCF0402JT33R0"))
      (libsource (lib "eagle-import") (part "R_0402_33R0"))
    )
    (comp (ref "R159")
      (value "33R0")
      (footprint "eagle-import:0402")
      (fields (field (name "PARTNO") "RMCF0402JT33R0"))
      (libsource (lib "eagle-import") (part "R_0402_33R0"))
    )
    (comp (ref "R160")
      (value "33R0")
      (footprint "eagle-import:0402")
      (fields (field (name "PARTNO") "RMCF0402JT33R0"))
      (libsource (lib "eagle-import") (part "R_0402_33R0"))
    )
    (comp (ref "R161")
      (value "1k")
      (footprint "eagle-import:0805")
      (libsource (lib "eagle-import") (part "R_0805"))
    )
    (comp (ref "R162")
      (value "1k")
      (footprint "eagle-import:0805")
      (libsource (lib "eagle-import") (part "R_0805"))
    )
    (comp (ref "R163")
      (value "1k")
      (footprint "eagle-import:0805")
      (libsource (lib "eagle-import") (part "R_0805"))
    )
    (comp (ref "R164")
      (value "33R0")
      (footprint "eagle-import:0402")
      (fields (field (name "PARTNO") "RMCF0402JT33R0"))
      (libsource (lib "eagle-import") (part "R_0402_33R0"))
    )
    (comp (ref "R165")
      (value "33R0")
      (footprint "eagle-import:0402")
      (fields (field (name "PARTNO") "RMCF0402JT33R0"))
      (libsource (lib "eagle-import") (part "R_0402_33R0"))
    )
    (comp (ref "R166")
      (value "33R0")
      (footprint "eagle-import:0402")
      (fields (field (name "PARTNO") "RMCF0402JT33R0"))
      (libsource (lib "eagle-import") (part "R_0402_33R0"))
    )
    (comp (ref "R167")
      (value "1k")
      (footprint "eagle-import:0805")
      (libsource (lib "eagle-import") (part "R_0805"))
    )
    (comp (ref "R168")
      (value "1k")
      (footprint "eagle-import:0805")
      (libsource (lib "eagle-import") (part "R_0805"))
    )
    (comp (ref "RJ1")
      (value "RJ45")
      (footprint "eagle-import:RJ45_TH_ELEC")
      (fields (field (name "PARTNO") "13F-64GYD2PL2NL"))
      (libsource (lib "eagle-import") (part "RJ45_WITH_ELEC"))
    )
    (comp (ref "TH01")
      (value "CONN_530470210_PICOBLADE_X_2")
      (footprint "eagle-import:CON_530470210_MOL")
      (fields
        (field (name "MANUFACTURER_PART_NUMBER") "530470210")
        (field (name "COPYRIGHT") "Copyright (C) 2022 Ultra Librarian. All rights reserved.")
      )
      (libsource (lib "eagle-import") (part "CONN_530470210_PICOBLADE_X_2"))
    )
    (comp (ref "TH02")
      (value "CONN_530470210_PICOBLADE_X_2")
      (footprint "eagle-import:CON_530470210_MOL")
      (fields
        (field (name "MANUFACTURER_PART_NUMBER") "530470210")
        (field (name "COPYRIGHT") "Copyright (C) 2022 Ultra Librarian. All rights reserved.")
      )
      (libsource (lib "eagle-import") (part "CONN_530470210_PICOBLADE_X_2"))
    )
    (comp (ref "TH03")
      (value "CONN_530470210_PICOBLADE_X_2")
      (footprint "eagle-import:CON_530470210_MOL")
      (fields
        (field (name "MANUFACTURER_PART_NUMBER") "530470210")
        (field (name "COPYRIGHT") "Copyright (C) 2022 Ultra Librarian. All rights reserved.")
      )
      (libsource (lib "eagle-import") (part "CONN_530470210_PICOBLADE_X_2"))
    )
    (comp (ref "TH04")
      (value "CONN_530470210_PICOBLADE_X_2")
      (footprint "eagle-import:CON_530470210_MOL")
      (fields
        (field (name "MANUFACTURER_PART_NUMBER") "530470210")
        (field (name "COPYRIGHT") "Copyright (C) 2022 Ultra Librarian. All rights reserved.")
      )
      (libsource (lib "eagle-import") (part "CONN_530470210_PICOBLADE_X_2"))
    )
    (comp (ref "TH05")
      (value "CONN_530470210_PICOBLADE_X_2")
      (footprint "eagle-import:CON_530470210_MOL")
      (fields
        (field (name "MANUFACTURER_PART_NUMBER") "530470210")
        (field (name "COPYRIGHT") "Copyright (C) 2022 Ultra Librarian. All rights reserved.")
      )
      (libsource (lib "eagle-import") (part "CONN_530470210_PICOBLADE_X_2"))
    )
    (comp (ref "TH06")
      (value "CONN_530470210_PICOBLADE_X_2")
      (footprint "eagle-import:CON_530470210_MOL")
      (fields
        (field (name "MANUFACTURER_PART_NUMBER") "530470210")
        (field (name "COPYRIGHT") "Copyright (C) 2022 Ultra Librarian. All rights reserved.")
      )
      (libsource (lib "eagle-import") (part "CONN_530470210_PICOBLADE_X_2"))
    )
    (comp (ref "TH07")
      (value "CONN_530470210_PICOBLADE_X_2")
      (footprint "eagle-import:CON_530470210_MOL")
      (fields
        (field (name "MANUFACTURER_PART_NUMBER") "530470210")
        (field (name "COPYRIGHT") "Copyright (C) 2022 Ultra Librarian. All rights reserved.")
      )
      (libsource (lib "eagle-import") (part "CONN_530470210_PICOBLADE_X_2"))
    )
    (comp (ref "TH08")
      (value "CONN_530470210_PICOBLADE_X_2")
      (footprint "eagle-import:CON_530470210_MOL")
      (fields
        (field (name "MANUFACTURER_PART_NUMBER") "530470210")
        (field (name "COPYRIGHT") "Copyright (C) 2022 Ultra Librarian. All rights reserved.")
      )
      (libsource (lib "eagle-import") (part "CONN_530470210_PICOBLADE_X_2"))
    )
    (comp (ref "U$1")
      (value "RELAY_KYOTO_KF0604D")
      (footprint "eagle-import:RELAY_KYOTO_KF0604D")
      (libsource (lib "eagle-import") (part "RELAY_KYOTO_KF0604D"))
    )
    (comp (ref "U$2")
      (value "RELAY_KYOTO_KF0604D")
      (footprint "eagle-import:RELAY_KYOTO_KF0604D")
      (libsource (lib "eagle-import") (part "RELAY_KYOTO_KF0604D"))
    )
    (comp (ref "U$7")
      (value "RELAY_KYOTO_KF0604D")
      (footprint "eagle-import:RELAY_KYOTO_KF0604D")
      (libsource (lib "eagle-import") (part "RELAY_KYOTO_KF0604D"))
    )
    (comp (ref "U$8")
      (value "RELAY_KYOTO_KF0604D")
      (footprint "eagle-import:RELAY_KYOTO_KF0604D")
      (libsource (lib "eagle-import") (part "RELAY_KYOTO_KF0604D"))
    )
    (comp (ref "U1")
      (value "KSZ8081_QFN_24")
      (footprint "eagle-import:QFN-24-M")
      (fields (field (name "PARTNO") "KSZ8081RNACA"))
      (libsource (lib "eagle-import") (part "KSZ8081RNACAQFN-24-M"))
    )
    (comp (ref "U2")
      (value "AP2151DWG-7")
      (footprint "eagle-import:SOT-23-5")
      (fields (field (name "PARTNO") "AP2151WG-7"))
      (libsource (lib "eagle-import") (part "AP2151DWG-7"))
    )
    (comp (ref "U3")
      (value "S7G2LQFP176")
      (footprint "eagle-import:LQFP176_24X24")
      (fields (field (name "PARTNO") "R7FS7G27H3A01CFC#AA0"))
      (libsource (lib "eagle-import") (part "RENESAS_S7G2_X_176"))
    )
    (comp (ref "U5")
      (value "NPN")
      (footprint "eagle-import:SOT323")
      (fields (field (name "PARTNO") "BC846BW_NPN"))
      (libsource (lib "eagle-import") (part "BC846BW"))
    )
    (comp (ref "U6")
      (value "NPN")
      (footprint "eagle-import:SOT323")
      (fields (field (name "PARTNO") "BC846BW_NPN"))
      (libsource (lib "eagle-import") (part "BC846BW"))
    )
    (comp (ref "U7")
      (value "NPN")
      (footprint "eagle-import:SOT323")
      (fields (field (name "PARTNO") "BC846BW_NPN"))
      (libsource (lib "eagle-import") (part "BC846BW"))
    )
    (comp (ref "U8")
      (value "NPN")
      (footprint "eagle-import:SOT323")
      (fields (field (name "PARTNO") "BC846BW_NPN"))
      (libsource (lib "eagle-import") (part "BC846BW"))
    )
    (comp (ref "U9")
      (value "NPN")
      (footprint "eagle-import:SOT323")
      (fields (field (name "PARTNO") "BC846BW_NPN"))
      (libsource (lib "eagle-import") (part "BC846BW"))
    )
    (comp (ref "U10")
      (value "NPN")
      (footprint "eagle-import:SOT323")
      (fields (field (name "PARTNO") "BC846BW_NPN"))
      (libsource (lib "eagle-import") (part "BC846BW"))
    )
    (comp (ref "U11")
      (value "NPN")
      (footprint "eagle-import:SOT323")
      (fields (field (name "PARTNO") "BC846BW_NPN"))
      (libsource (lib "eagle-import") (part "BC846BW"))
    )
    (comp (ref "U12")
      (value "NPN")
      (footprint "eagle-import:SOT323")
      (fields (field (name "PARTNO") "BC846BW_NPN"))
      (libsource (lib "eagle-import") (part "BC846BW"))
    )
    (comp (ref "U13")
      (value "NPN")
      (footprint "eagle-import:SOT323")
      (fields (field (name "PARTNO") "BC846BW_NPN"))
      (libsource (lib "eagle-import") (part "BC846BW"))
    )
    (comp (ref "U14")
      (value "NPN")
      (footprint "eagle-import:SOT323")
      (fields (field (name "PARTNO") "BC846BW_NPN"))
      (libsource (lib "eagle-import") (part "BC846BW"))
    )
    (comp (ref "U15")
      (value "NPN")
      (footprint "eagle-import:SOT323")
      (fields (field (name "PARTNO") "BC846BW_NPN"))
      (libsource (lib "eagle-import") (part "BC846BW"))
    )
    (comp (ref "U16")
      (value "NPN")
      (footprint "eagle-import:SOT323")
      (fields (field (name "PARTNO") "BC846BW_NPN"))
      (libsource (lib "eagle-import") (part "BC846BW"))
    )
    (comp (ref "U17")
      (value "NPN")
      (footprint "eagle-import:SOT323")
      (fields (field (name "PARTNO") "BC846BW_NPN"))
      (libsource (lib "eagle-import") (part "BC846BW"))
    )
    (comp (ref "U18")
      (value "NPN")
      (footprint "eagle-import:SOT323")
      (fields (field (name "PARTNO") "BC846BW_NPN"))
      (libsource (lib "eagle-import") (part "BC846BW"))
    )
    (comp (ref "U19")
      (value "NPN")
      (footprint "eagle-import:SOT323")
      (fields (field (name "PARTNO") "BC846BW_NPN"))
      (libsource (lib "eagle-import") (part "BC846BW"))
    )
    (comp (ref "U20")
      (value "NPN")
      (footprint "eagle-import:SOT323")
      (fields (field (name "PARTNO") "BC846BW_NPN"))
      (libsource (lib "eagle-import") (part "BC846BW"))
    )
    (comp (ref "U21")
      (value "NPN")
      (footprint "eagle-import:SOT323")
      (fields (field (name "PARTNO") "BC846BW_NPN"))
      (libsource (lib "eagle-import") (part "BC846BW"))
    )
    (comp (ref "U22")
      (value "NPN")
      (footprint "eagle-import:SOT323")
      (fields (field (name "PARTNO") "BC846BW_NPN"))
      (libsource (lib "eagle-import") (part "BC846BW"))
    )
    (comp (ref "U23")
      (value "NPN")
      (footprint "eagle-import:SOT323")
      (fields (field (name "PARTNO") "BC846BW_NPN"))
      (libsource (lib "eagle-import") (part "BC846BW"))
    )
    (comp (ref "U24")
      (value "NPN")
      (footprint "eagle-import:SOT323")
      (fields (field (name "PARTNO") "BC846BW_NPN"))
      (libsource (lib "eagle-import") (part "BC846BW"))
    )
    (comp (ref "U25")
      (value "NPN")
      (footprint "eagle-import:SOT323")
      (fields (field (name "PARTNO") "BC846BW_NPN"))
      (libsource (lib "eagle-import") (part "BC846BW"))
    )
    (comp (ref "U26")
      (value "NPN")
      (footprint "eagle-import:SOT323")
      (fields (field (name "PARTNO") "BC846BW_NPN"))
      (libsource (lib "eagle-import") (part "BC846BW"))
    )
    (comp (ref "U27")
      (value "NPN")
      (footprint "eagle-import:SOT323")
      (fields (field (name "PARTNO") "BC846BW_NPN"))
      (libsource (lib "eagle-import") (part "BC846BW"))
    )
    (comp (ref "U28")
      (value "NPN")
      (footprint "eagle-import:SOT323")
      (fields (field (name "PARTNO") "BC846BW_NPN"))
      (libsource (lib "eagle-import") (part "BC846BW"))
    )
    (comp (ref "U29")
      (value "NPN")
      (footprint "eagle-import:SOT323")
      (fields (field (name "PARTNO") "BC846BW_NPN"))
      (libsource (lib "eagle-import") (part "BC846BW"))
    )
    (comp (ref "U30")
      (value "NPN")
      (footprint "eagle-import:SOT323")
      (fields (field (name "PARTNO") "BC846BW_NPN"))
      (libsource (lib "eagle-import") (part "BC846BW"))
    )
    (comp (ref "U34")
      (value "NPN")
      (footprint "eagle-import:SOT323")
      (fields (field (name "PARTNO") "BC846BW_NPN"))
      (libsource (lib "eagle-import") (part "BC846BW"))
    )
    (comp (ref "U35")
      (value "NPN")
      (footprint "eagle-import:SOT323")
      (fields (field (name "PARTNO") "BC846BW_NPN"))
      (libsource (lib "eagle-import") (part "BC846BW"))
    )
    (comp (ref "U36")
      (value "NPN")
      (footprint "eagle-import:SOT323")
      (fields (field (name "PARTNO") "BC846BW_NPN"))
      (libsource (lib "eagle-import") (part "BC846BW"))
    )
    (comp (ref "U37")
      (value "NPN")
      (footprint "eagle-import:SOT323")
      (fields (field (name "PARTNO") "BC846BW_NPN"))
      (libsource (lib "eagle-import") (part "BC846BW"))
    )
    (comp (ref "U38")
      (value "NPN")
      (footprint "eagle-import:SOT323")
      (fields (field (name "PARTNO") "BC846BW_NPN"))
      (libsource (lib "eagle-import") (part "BC846BW"))
    )
    (comp (ref "U39")
      (value "NPN")
      (footprint "eagle-import:SOT323")
      (fields (field (name "PARTNO") "BC846BW_NPN"))
      (libsource (lib "eagle-import") (part "BC846BW"))
    )
    (comp (ref "U46")
      (value "NPN")
      (footprint "eagle-import:SOT323")
      (fields (field (name "PARTNO") "BC846BW_NPN"))
      (libsource (lib "eagle-import") (part "BC846BW"))
    )
    (comp (ref "U47")
      (value "NPN")
      (footprint "eagle-import:SOT323")
      (fields (field (name "PARTNO") "BC846BW_NPN"))
      (libsource (lib "eagle-import") (part "BC846BW"))
    )
    (comp (ref "U48")
      (value "NPN")
      (footprint "eagle-import:SOT323")
      (fields (field (name "PARTNO") "BC846BW_NPN"))
      (libsource (lib "eagle-import") (part "BC846BW"))
    )
    (comp (ref "U49")
      (value "NPN")
      (footprint "eagle-import:SOT323")
      (fields (field (name "PARTNO") "BC846BW_NPN"))
      (libsource (lib "eagle-import") (part "BC846BW"))
    )
    (comp (ref "U50")
      (value "NPN")
      (footprint "eagle-import:SOT323")
      (fields (field (name "PARTNO") "BC846BW_NPN"))
      (libsource (lib "eagle-import") (part "BC846BW"))
    )
    (comp (ref "U51")
      (value "NPN")
      (footprint "eagle-import:SOT323")
      (fields (field (name "PARTNO") "BC846BW_NPN"))
      (libsource (lib "eagle-import") (part "BC846BW"))
    )
    (comp (ref "U58")
      (value "NPN")
      (footprint "eagle-import:SOT323")
      (fields (field (name "PARTNO") "BC846BW_NPN"))
      (libsource (lib "eagle-import") (part "BC846BW"))
    )
    (comp (ref "U59")
      (value "NPN")
      (footprint "eagle-import:SOT323")
      (fields (field (name "PARTNO") "BC846BW_NPN"))
      (libsource (lib "eagle-import") (part "BC846BW"))
    )
    (comp (ref "U60")
      (value "NPN")
      (footprint "eagle-import:SOT323")
      (fields (field (name "PARTNO") "BC846BW_NPN"))
      (libsource (lib "eagle-import") (part "BC846BW"))
    )
    (comp (ref "U61")
      (value "NPN")
      (footprint "eagle-import:SOT323")
      (fields (field (name "PARTNO") "BC846BW_NPN"))
      (libsource (lib "eagle-import") (part "BC846BW"))
    )
    (comp (ref "U62")
      (value "NPN")
      (footprint "eagle-import:SOT323")
      (fields (field (name "PARTNO") "BC846BW_NPN"))
      (libsource (lib "eagle-import") (part "BC846BW"))
    )
    (comp (ref "U63")
      (value "NPN")
      (footprint "eagle-import:SOT323")
      (fields (field (name "PARTNO") "BC846BW_NPN"))
      (libsource (lib "eagle-import") (part "BC846BW"))
    )
    (comp (ref "U70")
      (value "NPN")
      (footprint "eagle-import:SOT323")
      (fields (field (name "PARTNO") "BC846BW_NPN"))
      (libsource (lib "eagle-import") (part "BC846BW"))
    )
    (comp (ref "U71")
      (value "NPN")
      (footprint "eagle-import:SOT323")
      (fields (field (name "PARTNO") "BC846BW_NPN"))
      (libsource (lib "eagle-import") (part "BC846BW"))
    )
    (comp (ref "U72")
      (value "NPN")
      (footprint "eagle-import:SOT323")
      (fields (field (name "PARTNO") "BC846BW_NPN"))
      (libsource (lib "eagle-import") (part "BC846BW"))
    )
    (comp (ref "U73")
      (value "NPN")
      (footprint "eagle-import:SOT323")
      (fields (field (name "PARTNO") "BC846BW_NPN"))
      (libsource (lib "eagle-import") (part "BC846BW"))
    )
    (comp (ref "U74")
      (value "NPN")
      (footprint "eagle-import:SOT323")
      (fields (field (name "PARTNO") "BC846BW_NPN"))
      (libsource (lib "eagle-import") (part "BC846BW"))
    )
    (comp (ref "U75")
      (value "NPN")
      (footprint "eagle-import:SOT323")
      (fields (field (name "PARTNO") "BC846BW_NPN"))
      (libsource (lib "eagle-import") (part "BC846BW"))
    )
    (comp (ref "X1")
      (value "25MHz")
      (footprint "eagle-import:SMD_3225")
      (fields (field (name "PARTNO") "FA-238 25.0000MB-B3"))
      (libsource (lib "eagle-import") (part "XTAL_25_MHZ"))
    )
    (comp (ref "X2")
      (value "24MHz")
      (footprint "eagle-import:SMD_3225")
      (fields (field (name "PARTNO") "FA-238 24.0000MB-C3 "))
      (libsource (lib "eagle-import") (part "XTAL_24_MHZ"))
    )
    (comp (ref "X3")
      (value "32.768KHz")
      (footprint "eagle-import:SMD_X_2_PADS")
      (fields (field (name "PARTNO") "ABS07-32.768KHZ-T"))
      (libsource (lib "eagle-import") (part "XTAL_32.768KHZ"))
    )
  )
  (nets
    (net (code "1") (name "A_A_DIR") (class "Default")
      (node (ref "R111") (pin "P$1") (pinfunction "1_P$1") (pintype "passive"))
      (node (ref "U3") (pin "73") (pinfunction "P9_5_73") (pintype "bidirectional"))
    )
    (net (code "2") (name "A_A_ENABLE") (class "Default")
      (node (ref "R112") (pin "P$1") (pinfunction "1_P$1") (pintype "passive"))
      (node (ref "U3") (pin "72") (pinfunction "P9_6_72") (pintype "bidirectional"))
    )
    (net (code "3") (name "A_A_HLFB_OUT") (class "Default")
      (node (ref "J25") (pin "5") (pinfunction "5-HLFB-_5") (pintype "passive"))
    )
    (net (code "4") (name "A_A_MI_DIR") (class "Default")
      (node (ref "J25") (pin "7") (pinfunction "7-INPUT_A-_7") (pintype "passive"))
      (node (ref "R113") (pin "1") (pinfunction "1_1") (pintype "passive"))
      (node (ref "U47") (pin "3") (pinfunction "C(3)_3") (pintype "input"))
    )
    (net (code "5") (name "A_A_MI_ENABLE") (class "Default")
      (node (ref "J25") (pin "8") (pinfunction "8-ENABLE-_8") (pintype "passive"))
      (node (ref "R114") (pin "1") (pinfunction "1_1") (pintype "passive"))
      (node (ref "U48") (pin "3") (pinfunction "C(3)_3") (pintype "input"))
    )
    (net (code "6") (name "A_A_MI_STEP") (class "Default")
      (node (ref "J25") (pin "6") (pinfunction "6-INPUT_B-_6") (pintype "passive"))
      (node (ref "R109") (pin "1") (pinfunction "1_1") (pintype "passive"))
      (node (ref "U46") (pin "3") (pinfunction "C(3)_3") (pintype "input"))
    )
    (net (code "7") (name "A_A_STEP") (class "Default")
      (node (ref "R110") (pin "P$1") (pinfunction "1_P$1") (pintype "passive"))
      (node (ref "U3") (pin "74") (pinfunction "P3_12_74") (pintype "bidirectional"))
    )
    (net (code "8") (name "A_B_DIR") (class "Default")
      (node (ref "R117") (pin "P$1") (pinfunction "1_P$1") (pintype "passive"))
      (node (ref "U3") (pin "76") (pinfunction "P3_10_76") (pintype "bidirectional"))
    )
    (net (code "9") (name "A_B_ENABLE") (class "Default")
      (node (ref "R118") (pin "P$1") (pinfunction "1_P$1") (pintype "passive"))
      (node (ref "U3") (pin "75") (pinfunction "P3_11_75") (pintype "bidirectional"))
    )
    (net (code "10") (name "A_B_HLFB_OUT") (class "Default")
      (node (ref "J26") (pin "5") (pinfunction "5-HLFB-_5") (pintype "passive"))
    )
    (net (code "11") (name "A_B_MI_DIR") (class "Default")
      (node (ref "J26") (pin "7") (pinfunction "7-INPUT_A-_7") (pintype "passive"))
      (node (ref "R119") (pin "1") (pinfunction "1_1") (pintype "passive"))
      (node (ref "U50") (pin "3") (pinfunction "C(3)_3") (pintype "input"))
    )
    (net (code "12") (name "A_B_MI_ENABLE") (class "Default")
      (node (ref "J26") (pin "8") (pinfunction "8-ENABLE-_8") (pintype "passive"))
      (node (ref "R120") (pin "1") (pinfunction "1_1") (pintype "passive"))
      (node (ref "U51") (pin "3") (pinfunction "C(3)_3") (pintype "input"))
    )
    (net (code "13") (name "A_B_MI_STEP") (class "Default")
      (node (ref "J26") (pin "6") (pinfunction "6-INPUT_B-_6") (pintype "passive"))
      (node (ref "R115") (pin "1") (pinfunction "1_1") (pintype "passive"))
      (node (ref "U49") (pin "3") (pinfunction "C(3)_3") (pintype "input"))
    )
    (net (code "14") (name "A_B_STEP") (class "Default")
      (node (ref "R116") (pin "P$1") (pinfunction "1_P$1") (pintype "passive"))
      (node (ref "U3") (pin "77") (pinfunction "P3_9_77") (pintype "bidirectional"))
    )
    (net (code "15") (name "B_MI_DIR") (class "Default")
      (node (ref "J34") (pin "7") (pinfunction "7-INPUT_A-_7") (pintype "passive"))
      (node (ref "R167") (pin "1") (pinfunction "1_1") (pintype "passive"))
      (node (ref "U74") (pin "3") (pinfunction "C(3)_3") (pintype "input"))
    )
    (net (code "16") (name "C58") (class "Default")
      (node (ref "C12") (pin "P$1") (pinfunction "1_P$1") (pintype "passive"))
      (node (ref "RJ1") (pin "4") (pinfunction "CT1_4") (pintype "bidirectional"))
    )
    (net (code "17") (name "C60") (class "Default")
      (node (ref "C13") (pin "P$1") (pinfunction "1_P$1") (pintype "passive"))
      (node (ref "RJ1") (pin "5") (pinfunction "CT2_5") (pintype "bidirectional"))
    )
    (net (code "18") (name "CRS_DV") (class "Default")
      (node (ref "R12") (pin "P$2") (pinfunction "2_P$2") (pintype "passive"))
      (node (ref "U1") (pin "15") (pinfunction "CRS_DV/PHYAD[1:0]_15") (pintype "bidirectional"))
    )
    (net (code "19") (name "C_A_DIR") (class "Default")
      (node (ref "R135") (pin "P$1") (pinfunction "1_P$1") (pintype "passive"))
      (node (ref "U3") (pin "58") (pinfunction "P9_0_58") (pintype "bidirectional"))
    )
    (net (code "20") (name "C_A_ENABLE") (class "Default")
      (node (ref "R136") (pin "P$1") (pinfunction "1_P$1") (pintype "passive"))
      (node (ref "U3") (pin "57") (pinfunction "P3_15_57") (pintype "bidirectional"))
    )
    (net (code "21") (name "C_A_HLFB_OUT") (class "Default")
      (node (ref "J29") (pin "5") (pinfunction "5-HLFB-_5") (pintype "passive"))
    )
    (net (code "22") (name "C_A_MI_DIR") (class "Default")
      (node (ref "J29") (pin "7") (pinfunction "7-INPUT_A-_7") (pintype "passive"))
      (node (ref "R137") (pin "1") (pinfunction "1_1") (pintype "passive"))
      (node (ref "U59") (pin "3") (pinfunction "C(3)_3") (pintype "input"))
    )
    (net (code "23") (name "C_A_MI_ENABLE") (class "Default")
      (node (ref "J29") (pin "8") (pinfunction "8-ENABLE-_8") (pintype "passive"))
      (node (ref "R138") (pin "1") (pinfunction "1_1") (pintype "passive"))
      (node (ref "U60") (pin "3") (pinfunction "C(3)_3") (pintype "input"))
    )
    (net (code "24") (name "C_A_MI_STEP") (class "Default")
      (node (ref "J29") (pin "6") (pinfunction "6-INPUT_B-_6") (pintype "passive"))
      (node (ref "R133") (pin "1") (pinfunction "1_1") (pintype "passive"))
      (node (ref "U58") (pin "3") (pinfunction "C(3)_3") (pintype "input"))
    )
    (net (code "25") (name "C_A_STEP") (class "Default")
      (node (ref "R134") (pin "P$1") (pinfunction "1_P$1") (pintype "passive"))
      (node (ref "U3") (pin "59") (pinfunction "P9_1_59") (pintype "bidirectional"))
    )
    (net (code "26") (name "C_B_DIR") (class "Default")
      (node (ref "R141") (pin "P$1") (pinfunction "1_P$1") (pintype "passive"))
      (node (ref "U3") (pin "70") (pinfunction "P9_8_70") (pintype "bidirectional"))
    )
    (net (code "27") (name "C_B_ENABLE") (class "Default")
      (node (ref "R142") (pin "P$1") (pinfunction "1_P$1") (pintype "passive"))
      (node (ref "U3") (pin "68") (pinfunction "P2_1/MD_68") (pintype "bidirectional"))
    )
    (net (code "28") (name "C_B_HLFB_OUT") (class "Default")
      (node (ref "J30") (pin "5") (pinfunction "5-HLFB-_5") (pintype "passive"))
    )
    (net (code "29") (name "C_B_MI_DIR") (class "Default")
      (node (ref "J30") (pin "7") (pinfunction "7-INPUT_A-_7") (pintype "passive"))
      (node (ref "R143") (pin "1") (pinfunction "1_1") (pintype "passive"))
      (node (ref "U62") (pin "3") (pinfunction "C(3)_3") (pintype "input"))
    )
    (net (code "30") (name "C_B_MI_ENABLE") (class "Default")
      (node (ref "J30") (pin "8") (pinfunction "8-ENABLE-_8") (pintype "passive"))
      (node (ref "R144") (pin "1") (pinfunction "1_1") (pintype "passive"))
      (node (ref "U63") (pin "3") (pinfunction "C(3)_3") (pintype "input"))
    )
    (net (code "31") (name "C_B_MI_STEP") (class "Default")
      (node (ref "J30") (pin "6") (pinfunction "6-INPUT_B-_6") (pintype "passive"))
      (node (ref "R139") (pin "1") (pinfunction "1_1") (pintype "passive"))
      (node (ref "U61") (pin "3") (pinfunction "C(3)_3") (pintype "input"))
    )
    (net (code "32") (name "C_B_STEP") (class "Default")
      (node (ref "R140") (pin "P$1") (pinfunction "1_P$1") (pintype "passive"))
      (node (ref "U3") (pin "71") (pinfunction "P9_7_71") (pintype "bidirectional"))
    )
    (net (code "33") (name "ESTOP") (class "Default")
      (node (ref "R79") (pin "P$2") (pinfunction "2_P$2") (pintype "passive"))
      (node (ref "R80") (pin "P$2") (pinfunction "2_P$2") (pintype "passive"))
      (node (ref "U21") (pin "2") (pinfunction "E(1)_2") (pintype "output"))
      (node (ref "U3") (pin "69") (pinfunction "P2_0(INPUT_ONLY)_69") (pintype "bidirectional"))
    )
    (net (code "34") (name "ESTOP_RET") (class "Default")
      (node (ref "J20") (pin "1") (pinfunction "1_1") (pintype "passive"))
      (node (ref "R78") (pin "P$1") (pinfunction "1_P$1") (pintype "passive"))
    )
    (net (code "35") (name "ETH") (class "Default")
      (node (ref "U1") (pin "16") (pinfunction "REF_CLK_16") (pintype "bidirectional"))
      (node (ref "U3") (pin "9") (pinfunction "P7_1_9") (pintype "bidirectional"))
    )
    (net (code "36") (name "ETH_CRS_DV") (class "Default")
      (node (ref "R12") (pin "P$1") (pinfunction "1_P$1") (pintype "passive"))
      (node (ref "U3") (pin "13") (pinfunction "P7_5_13") (pintype "bidirectional"))
    )
    (net (code "37") (name "ETH_IRQ14") (class "Default")
      (node (ref "R2") (pin "P$1") (pinfunction "1_P$1") (pintype "passive"))
      (node (ref "U1") (pin "18") (pinfunction "INTRP_18") (pintype "bidirectional"))
      (node (ref "U3") (pin "159") (pinfunction "P0_10/AN103_159") (pintype "bidirectional"))
    )
    (net (code "38") (name "ETH_MDC") (class "Default")
      (node (ref "R4") (pin "P$1") (pinfunction "1_P$1") (pintype "passive"))
      (node (ref "U1") (pin "11") (pinfunction "MDC_11") (pintype "input"))
      (node (ref "U3") (pin "4") (pinfunction "P4_3_4") (pintype "bidirectional"))
    )
    (net (code "39") (name "ETH_MDIO") (class "Default")
      (node (ref "R6") (pin "P$1") (pinfunction "1_P$1") (pintype "passive"))
      (node (ref "U1") (pin "10") (pinfunction "MDIO_10") (pintype "bidirectional"))
      (node (ref "U3") (pin "5") (pinfunction "P4_4_5") (pintype "bidirectional"))
    )
    (net (code "40") (name "ETH_RESET") (class "Default")
      (node (ref "C6") (pin "P$1") (pinfunction "1_P$1") (pintype "passive"))
      (node (ref "R3") (pin "P$1") (pinfunction "1_P$1") (pintype "passive"))
      (node (ref "U1") (pin "24") (pinfunction "~{RST}_24") (pintype "input"))
      (node (ref "U3") (pin "172") (pinfunction "P8_6_172") (pintype "bidirectional"))
    )
    (net (code "41") (name "ETH_RXD0") (class "Default")
      (node (ref "R10") (pin "P$1") (pinfunction "1_P$1") (pintype "passive"))
      (node (ref "U3") (pin "10") (pinfunction "P7_2_10") (pintype "bidirectional"))
    )
    (net (code "42") (name "ETH_RXD1") (class "Default")
      (node (ref "R9") (pin "P$1") (pinfunction "1_P$1") (pintype "passive"))
      (node (ref "U3") (pin "11") (pinfunction "P7_3_11") (pintype "bidirectional"))
    )
    (net (code "43") (name "ETH_RX_ER") (class "Default")
      (node (ref "R11") (pin "P$1") (pinfunction "1_P$1") (pintype "passive"))
      (node (ref "U3") (pin "12") (pinfunction "P7_4_12") (pintype "bidirectional"))
    )
    (net (code "44") (name "ETH_TXD0") (class "Default")
      (node (ref "U1") (pin "20") (pinfunction "TXD0_20") (pintype "input"))
      (node (ref "U3") (pin "8") (pinfunction "P7_0_8") (pintype "bidirectional"))
    )
    (net (code "45") (name "ETH_TXD1") (class "Default")
      (node (ref "U1") (pin "21") (pinfunction "TXD1_21") (pintype "bidirectional"))
      (node (ref "U3") (pin "7") (pinfunction "P4_6_7") (pintype "bidirectional"))
    )
    (net (code "46") (name "ETH_TXD_EN") (class "Default")
      (node (ref "U1") (pin "19") (pinfunction "TXEN_19") (pintype "input"))
      (node (ref "U3") (pin "6") (pinfunction "P4_5_6") (pintype "bidirectional"))
    )
    (net (code "47") (name "GND") (class "Default")
      (node (ref "C1") (pin "P$2") (pinfunction "2_P$2") (pintype "passive"))
      (node (ref "C10") (pin "P$2") (pinfunction "2_P$2") (pintype "passive"))
      (node (ref "C11") (pin "P$2") (pinfunction "2_P$2") (pintype "passive"))
      (node (ref "C12") (pin "P$2") (pinfunction "2_P$2") (pintype "passive"))
      (node (ref "C13") (pin "P$2") (pinfunction "2_P$2") (pintype "passive"))
      (node (ref "C14") (pin "P$2") (pinfunction "2_P$2") (pintype "passive"))
      (node (ref "C15") (pin "P$2") (pinfunction "2_P$2") (pintype "passive"))
      (node (ref "C16") (pin "P$2") (pinfunction "2_P$2") (pintype "passive"))
      (node (ref "C17") (pin "P$2") (pinfunction "2_P$2") (pintype "passive"))
      (node (ref "C18") (pin "P$2") (pinfunction "2_P$2") (pintype "passive"))
      (node (ref "C19") (pin "P$1") (pinfunction "1_P$1") (pintype "passive"))
      (node (ref "C2") (pin "P$2") (pinfunction "2_P$2") (pintype "passive"))
      (node (ref "C20") (pin "P$1") (pinfunction "1_P$1") (pintype "passive"))
      (node (ref "C21") (pin "P$1") (pinfunction "1_P$1") (pintype "passive"))
      (node (ref "C22") (pin "P$1") (pinfunction "1_P$1") (pintype "passive"))
      (node (ref "C23") (pin "P$2") (pinfunction "2_P$2") (pintype "passive"))
      (node (ref "C24") (pin "P$1") (pinfunction "1_P$1") (pintype "passive"))
      (node (ref "C25") (pin "P$1") (pinfunction "1_P$1") (pintype "passive"))
      (node (ref "C26") (pin "P$2") (pinfunction "2_P$2") (pintype "passive"))
      (node (ref "C27") (pin "P$1") (pinfunction "1_P$1") (pintype "passive"))
      (node (ref "C28") (pin "P$2") (pinfunction "2_P$2") (pintype "passive"))
      (node (ref "C29") (pin "P$2") (pinfunction "2_P$2") (pintype "passive"))
      (node (ref "C3") (pin "P$2") (pinfunction "2_P$2") (pintype "passive"))
      (node (ref "C30") (pin "P$1") (pinfunction "1_P$1") (pintype "passive"))
      (node (ref "C31") (pin "2") (pinfunction "2_2") (pintype "passive"))
      (node (ref "C32") (pin "P$2") (pinfunction "2_P$2") (pintype "passive"))
      (node (ref "C33") (pin "P$2") (pinfunction "2_P$2") (pintype "passive"))
      (node (ref "C34") (pin "P$1") (pinfunction "1_P$1") (pintype "passive"))
      (node (ref "C35") (pin "P$1") (pinfunction "1_P$1") (pintype "passive"))
      (node (ref "C36") (pin "P$2") (pinfunction "2_P$2") (pintype "passive"))
      (node (ref "C37") (pin "P$2") (pinfunction "2_P$2") (pintype "passive"))
      (node (ref "C38") (pin "P$1") (pinfunction "1_P$1") (pintype "passive"))
      (node (ref "C39") (pin "P$2") (pinfunction "2_P$2") (pintype "passive"))
      (node (ref "C4") (pin "P$2") (pinfunction "2_P$2") (pintype "passive"))
      (node (ref "C40") (pin "P$2") (pinfunction "2_P$2") (pintype "passive"))
      (node (ref "C41") (pin "P$2") (pinfunction "2_P$2") (pintype "passive"))
      (node (ref "C42") (pin "P$2") (pinfunction "2_P$2") (pintype "passive"))
      (node (ref "C43") (pin "P$1") (pinfunction "1_P$1") (pintype "passive"))
      (node (ref "C5") (pin "P$2") (pinfunction "2_P$2") (pintype "passive"))
      (node (ref "C6") (pin "P$2") (pinfunction "2_P$2") (pintype "passive"))
      (node (ref "C7") (pin "P$2") (pinfunction "2_P$2") (pintype "passive"))
      (node (ref "C8") (pin "P$2") (pinfunction "2_P$2") (pintype "passive"))
      (node (ref "C9") (pin "P$2") (pinfunction "2_P$2") (pintype "passive"))
      (node (ref "J1") (pin "6") (pinfunction "SUPPLY_VOLTAGE_GROUND_6") (pintype "power_in"))
      (node (ref "J10") (pin "2") (pinfunction "2_2") (pintype "passive"))
      (node (ref "J11") (pin "2") (pinfunction "2_2") (pintype "passive"))
      (node (ref "J12") (pin "2") (pinfunction "2_2") (pintype "passive"))
      (node (ref "J19") (pin "2") (pinfunction "2_2") (pintype "passive"))
      (node (ref "J2") (pin "P$1") (pinfunction "P$1_P$1") (pintype "bidirectional"))
      (node (ref "J20") (pin "2") (pinfunction "2_2") (pintype "passive"))
      (node (ref "J27") (pin "2") (pinfunction "2_2") (pintype "passive"))
      (node (ref "J28") (pin "2") (pinfunction "2_2") (pintype "passive"))
      (node (ref "J3") (pin "10") (pinfunction "10_10") (pintype "passive"))
      (node (ref "J3") (pin "6") (pinfunction "6_6") (pintype "passive"))
      (node (ref "J3") (pin "8") (pinfunction "8_8") (pintype "passive"))
      (node (ref "J31") (pin "2") (pinfunction "2_2") (pintype "passive"))
      (node (ref "J32") (pin "2") (pinfunction "2_2") (pintype "passive"))
      (node (ref "J5") (pin "2") (pinfunction "2_2") (pintype "passive"))
      (node (ref "J6") (pin "GND") (pinfunction "GND_GND") (pintype "power_in"))
      (node (ref "J7") (pin "P$5") (pinfunction "GND_P$5") (pintype "bidirectional"))
      (node (ref "J8") (pin "P$14") (pinfunction "P$14_P$14") (pintype "bidirectional"))
      (node (ref "J8") (pin "P$16") (pinfunction "P$16_P$16") (pintype "bidirectional"))
      (node (ref "J8") (pin "P$18") (pinfunction "P$18_P$18") (pintype "bidirectional"))
      (node (ref "J8") (pin "P$20") (pinfunction "P$20_P$20") (pintype "bidirectional"))
      (node (ref "LED1") (pin "2") (pinfunction "C_2") (pintype "passive"))
      (node (ref "LED10") (pin "2") (pinfunction "C_2") (pintype "passive"))
      (node (ref "LED11") (pin "2") (pinfunction "C_2") (pintype "passive"))
      (node (ref "LED12") (pin "2") (pinfunction "C_2") (pintype "passive"))
      (node (ref "LED13") (pin "2") (pinfunction "C_2") (pintype "passive"))
      (node (ref "LED14") (pin "2") (pinfunction "C_2") (pintype "passive"))
      (node (ref "LED15") (pin "2") (pinfunction "C_2") (pintype "passive"))
      (node (ref "LED16") (pin "2") (pinfunction "C_2") (pintype "passive"))
      (node (ref "LED3") (pin "2") (pinfunction "C_2") (pintype "passive"))
      (node (ref "LED6") (pin "2") (pinfunction "C_2") (pintype "passive"))
      (node (ref "LED7") (pin "2") (pinfunction "C_2") (pintype "passive"))
      (node (ref "R1") (pin "P$1") (pinfunction "1_P$1") (pintype "passive"))
      (node (ref "R101") (pin "P$1") (pinfunction "1_P$1") (pintype "passive"))
      (node (ref "R21") (pin "P$1") (pinfunction "1_P$1") (pintype "passive"))
      (node (ref "R22") (pin "P$1") (pinfunction "1_P$1") (pintype "passive"))
      (node (ref "R23") (pin "P$1") (pinfunction "1_P$1") (pintype "passive"))
      (node (ref "R24") (pin "P$1") (pinfunction "1_P$1") (pintype "passive"))
      (node (ref "R34") (pin "P$1") (pinfunction "1_P$1") (pintype "passive"))
      (node (ref "R53") (pin "P$1") (pinfunction "1_P$1") (pintype "passive"))
      (node (ref "R56") (pin "P$1") (pinfunction "1_P$1") (pintype "passive"))
      (node (ref "R59") (pin "P$1") (pinfunction "1_P$1") (pintype "passive"))
      (node (ref "R74") (pin "P$1") (pinfunction "1_P$1") (pintype "passive"))
      (node (ref "R77") (pin "P$1") (pinfunction "1_P$1") (pintype "passive"))
      (node (ref "R80") (pin "P$1") (pinfunction "1_P$1") (pintype "passive"))
      (node (ref "R83") (pin "P$1") (pinfunction "1_P$1") (pintype "passive"))
      (node (ref "R98") (pin "P$1") (pinfunction "1_P$1") (pintype "passive"))
      (node (ref "RJ1") (pin "10") (pinfunction "GLO_10") (pintype "bidirectional"))
      (node (ref "RJ1") (pin "8") (pinfunction "P8_8") (pintype "bidirectional"))
      (node (ref "TH01") (pin "1") (pinfunction "1_1") (pintype "passive"))
      (node (ref "TH02") (pin "1") (pinfunction "1_1") (pintype "passive"))
      (node (ref "TH03") (pin "1") (pinfunction "1_1") (pintype "passive"))
      (node (ref "TH04") (pin "1") (pinfunction "1_1") (pintype "passive"))
      (node (ref "TH05") (pin "1") (pinfunction "1_1") (pintype "passive"))
      (node (ref "TH06") (pin "1") (pinfunction "1_1") (pintype "passive"))
      (node (ref "TH07") (pin "1") (pinfunction "1_1") (pintype "passive"))
      (node (ref "TH08") (pin "1") (pinfunction "1_1") (pintype "passive"))
      (node (ref "U1") (pin "22") (pinfunction "GND_22") (pintype "power_in"))
      (node (ref "U1") (pin "25") (pinfunction "25_25") (pintype "passive"))
      (node (ref "U10") (pin "2") (pinfunction "E(1)_2") (pintype "output"))
      (node (ref "U11") (pin "2") (pinfunction "E(1)_2") (pintype "output"))
      (node (ref "U12") (pin "2") (pinfunction "E(1)_2") (pintype "output"))
      (node (ref "U13") (pin "2") (pinfunction "E(1)_2") (pintype "output"))
      (node (ref "U14") (pin "2") (pinfunction "E(1)_2") (pintype "output"))
      (node (ref "U15") (pin "2") (pinfunction "E(1)_2") (pintype "output"))
      (node (ref "U16") (pin "2") (pinfunction "E(1)_2") (pintype "output"))
      (node (ref "U17") (pin "2") (pinfunction "E(1)_2") (pintype "output"))
      (node (ref "U2") (pin "2") (pinfunction "GND_2") (pintype "input"))
      (node (ref "U22") (pin "2") (pinfunction "E(1)_2") (pintype "output"))
      (node (ref "U23") (pin "2") (pinfunction "E(1)_2") (pintype "output"))
      (node (ref "U24") (pin "2") (pinfunction "E(1)_2") (pintype "output"))
      (node (ref "U25") (pin "2") (pinfunction "E(1)_2") (pintype "output"))
      (node (ref "U26") (pin "2") (pinfunction "E(1)_2") (pintype "output"))
      (node (ref "U27") (pin "2") (pinfunction "E(1)_2") (pintype "output"))
      (node (ref "U3") (pin "111") (pinfunction "VSS(IO)5_111") (pintype "bidirectional"))
      (node (ref "U3") (pin "124") (pinfunction "VSS(IO)6_124") (pintype "bidirectional"))
      (node (ref "U3") (pin "139") (pinfunction "VSS(IO)7_139") (pintype "bidirectional"))
      (node (ref "U3") (pin "150") (pinfunction "VSS(IO)8_150") (pintype "bidirectional"))
      (node (ref "U3") (pin "153") (pinfunction "VREFL_153") (pintype "bidirectional"))
      (node (ref "U3") (pin "156") (pinfunction "AVSS0_156") (pintype "bidirectional"))
      (node (ref "U3") (pin "157") (pinfunction "VREFL0_157") (pintype "bidirectional"))
      (node (ref "U3") (pin "170") (pinfunction "VSS(IO)9_170") (pintype "bidirectional"))
      (node (ref "U3") (pin "22") (pinfunction "VSS1_22") (pintype "bidirectional"))
      (node (ref "U3") (pin "28") (pinfunction "AVSS_USBHS_28") (pintype "bidirectional"))
      (node (ref "U3") (pin "29") (pinfunction "PVSS_USBHS_29") (pintype "bidirectional"))
      (node (ref "U3") (pin "30") (pinfunction "VSS2_USBHS_30") (pintype "bidirectional"))
      (node (ref "U3") (pin "33") (pinfunction "VSS1_USBHS_33") (pintype "bidirectional"))
      (node (ref "U3") (pin "35") (pinfunction "VSSIO_35") (pintype "bidirectional"))
      (node (ref "U3") (pin "45") (pinfunction "VSS_USB_45") (pintype "bidirectional"))
      (node (ref "U3") (pin "60") (pinfunction "VSS(IO)2_60") (pintype "bidirectional"))
      (node (ref "U3") (pin "63") (pinfunction "VSS(IO/DCDC)_63") (pintype "bidirectional"))
      (node (ref "U3") (pin "66") (pinfunction "VCC_DCDC(IO/DCDC)_66") (pintype "bidirectional"))
      (node (ref "U3") (pin "83") (pinfunction "VSS(IO)3_83") (pintype "bidirectional"))
      (node (ref "U3") (pin "98") (pinfunction "VSS(IO)4_98") (pintype "bidirectional"))
      (node (ref "U34") (pin "2") (pinfunction "E(1)_2") (pintype "output"))
      (node (ref "U35") (pin "2") (pinfunction "E(1)_2") (pintype "output"))
      (node (ref "U36") (pin "2") (pinfunction "E(1)_2") (pintype "output"))
      (node (ref "U37") (pin "2") (pinfunction "E(1)_2") (pintype "output"))
      (node (ref "U38") (pin "2") (pinfunction "E(1)_2") (pintype "output"))
      (node (ref "U39") (pin "2") (pinfunction "E(1)_2") (pintype "output"))
      (node (ref "U46") (pin "2") (pinfunction "E(1)_2") (pintype "output"))
      (node (ref "U47") (pin "2") (pinfunction "E(1)_2") (pintype "output"))
      (node (ref "U48") (pin "2") (pinfunction "E(1)_2") (pintype "output"))
      (node (ref "U49") (pin "2") (pinfunction "E(1)_2") (pintype "output"))
      (node (ref "U50") (pin "2") (pinfunction "E(1)_2") (pintype "output"))
      (node (ref "U51") (pin "2") (pinfunction "E(1)_2") (pintype "output"))
      (node (ref "U58") (pin "2") (pinfunction "E(1)_2") (pintype "output"))
      (node (ref "U59") (pin "2") (pinfunction "E(1)_2") (pintype "output"))
      (node (ref "U6") (pin "2") (pinfunction "E(1)_2") (pintype "output"))
      (node (ref "U60") (pin "2") (pinfunction "E(1)_2") (pintype "output"))
      (node (ref "U61") (pin "2") (pinfunction "E(1)_2") (pintype "output"))
      (node (ref "U62") (pin "2") (pinfunction "E(1)_2") (pintype "output"))
      (node (ref "U63") (pin "2") (pinfunction "E(1)_2") (pintype "output"))
      (node (ref "U7") (pin "2") (pinfunction "E(1)_2") (pintype "output"))
      (node (ref "U70") (pin "2") (pinfunction "E(1)_2") (pintype "output"))
      (node (ref "U71") (pin "2") (pinfunction "E(1)_2") (pintype "output"))
      (node (ref "U72") (pin "2") (pinfunction "E(1)_2") (pintype "output"))
      (node (ref "U73") (pin "2") (pinfunction "E(1)_2") (pintype "output"))
      (node (ref "U74") (pin "2") (pinfunction "E(1)_2") (pintype "output"))
      (node (ref "U75") (pin "2") (pinfunction "E(1)_2") (pintype "output"))
      (node (ref "X1") (pin "2") (pinfunction "2_2") (pintype "bidirectional"))
      (node (ref "X1") (pin "4") (pinfunction "4_4") (pintype "bidirectional"))
      (node (ref "X2") (pin "2") (pinfunction "2_2") (pintype "bidirectional"))
      (node (ref "X2") (pin "4") (pinfunction "4_4") (pintype "bidirectional"))
    )
    (net (code "48") (name "GNDE") (class "Default")
      (node (ref "J1") (pin "S1") (pinfunction "SHIELD_S1") (pintype "passive"))
      (node (ref "J1") (pin "S2") (pinfunction "SHIELD_S2") (pintype "passive"))
      (node (ref "J1") (pin "S3") (pinfunction "SHIELD_S3") (pintype "passive"))
      (node (ref "J1") (pin "S4") (pinfunction "SHIELD_S4") (pintype "passive"))
      (node (ref "J2") (pin "P$4") (pinfunction "P$4_P$4") (pintype "bidirectional"))
      (node (ref "J6") (pin "SHLD1") (pinfunction "SHIELD_1_SHLD1") (pintype "bidirectional"))
      (node (ref "J6") (pin "SHLD2") (pinfunction "SHIELD_2_SHLD2") (pintype "bidirectional"))
      (node (ref "J7") (pin "P$6") (pinfunction "SHIELD1_P$6") (pintype "bidirectional"))
      (node (ref "J7") (pin "P$7") (pinfunction "SHIELD2_P$7") (pintype "bidirectional"))
      (node (ref "J7") (pin "P$8") (pinfunction "SHIELD3_P$8") (pintype "bidirectional"))
      (node (ref "J7") (pin "P$9") (pinfunction "SHIELD4_P$9") (pintype "bidirectional"))
      (node (ref "RJ1") (pin "13") (pinfunction "GNDE0_13") (pintype "bidirectional"))
      (node (ref "RJ1") (pin "14") (pinfunction "GNDE1_14") (pintype "bidirectional"))
    )
    (net (code "49") (name "ID") (class "Default")
      (node (ref "J7") (pin "P$4") (pinfunction "ID_P$4") (pintype "bidirectional"))
    )
    (net (code "50") (name "IIC_1_SCL") (class "Default")
      (node (ref "J8") (pin "P$8") (pinfunction "P$8_P$8") (pintype "bidirectional"))
      (node (ref "R14") (pin "P$2") (pinfunction "2_P$2") (pintype "passive"))
      (node (ref "U3") (pin "132") (pinfunction "P1_0_132") (pintype "bidirectional"))
    )
    (net (code "51") (name "IIC_1_SDA") (class "Default")
      (node (ref "J8") (pin "P$7") (pinfunction "P$7_P$7") (pintype "bidirectional"))
      (node (ref "R15") (pin "P$2") (pinfunction "2_P$2") (pintype "passive"))
      (node (ref "U3") (pin "131") (pinfunction "P1_1_131") (pintype "bidirectional"))
    )
    (net (code "52") (name "LED1{slash}SPEED") (class "Default")
      (node (ref "RJ1") (pin "11") (pinfunction "YLO_11") (pintype "bidirectional"))
      (node (ref "U1") (pin "23") (pinfunction "LED0/ANEN_SPEED_23") (pintype "bidirectional"))
    )
    (net (code "53") (name "LS_01") (class "Default")
      (node (ref "R33") (pin "P$2") (pinfunction "2_P$2") (pintype "passive"))
      (node (ref "R34") (pin "P$2") (pinfunction "2_P$2") (pintype "passive"))
      (node (ref "U3") (pin "50") (pinfunction "P2_6_50") (pintype "bidirectional"))
      (node (ref "U5") (pin "2") (pinfunction "E(1)_2") (pintype "output"))
    )
    (net (code "54") (name "LS_01_RET") (class "Default")
      (node (ref "J32") (pin "1") (pinfunction "1_1") (pintype "passive"))
      (node (ref "R28") (pin "P$1") (pinfunction "1_P$1") (pintype "passive"))
    )
    (net (code "55") (name "LS_02") (class "Default")
      (node (ref "R36") (pin "P$2") (pinfunction "2_P$2") (pintype "passive"))
      (node (ref "R53") (pin "P$2") (pinfunction "2_P$2") (pintype "passive"))
      (node (ref "U3") (pin "51") (pinfunction "P2_5_51") (pintype "bidirectional"))
      (node (ref "U8") (pin "2") (pinfunction "E(1)_2") (pintype "output"))
    )
    (net (code "56") (name "LS_02_RET") (class "Default")
      (node (ref "J31") (pin "1") (pinfunction "1_1") (pintype "passive"))
      (node (ref "R35") (pin "P$1") (pinfunction "1_P$1") (pintype "passive"))
    )
    (net (code "57") (name "LS_03") (class "Default")
      (node (ref "R55") (pin "P$2") (pinfunction "2_P$2") (pintype "passive"))
      (node (ref "R56") (pin "P$2") (pinfunction "2_P$2") (pintype "passive"))
      (node (ref "U3") (pin "53") (pinfunction "P2_3_53") (pintype "bidirectional"))
      (node (ref "U9") (pin "2") (pinfunction "E(1)_2") (pintype "output"))
    )
    (net (code "58") (name "LS_03_RET") (class "Default")
      (node (ref "J28") (pin "1") (pinfunction "1_1") (pintype "passive"))
      (node (ref "R54") (pin "P$1") (pinfunction "1_P$1") (pintype "passive"))
    )
    (net (code "59") (name "LS_04") (class "Default")
      (node (ref "R73") (pin "P$2") (pinfunction "2_P$2") (pintype "passive"))
      (node (ref "R74") (pin "P$2") (pinfunction "2_P$2") (pintype "passive"))
      (node (ref "U19") (pin "2") (pinfunction "E(1)_2") (pintype "output"))
      (node (ref "U3") (pin "54") (pinfunction "P2_2_54") (pintype "bidirectional"))
    )
    (net (code "60") (name "LS_04_RET") (class "Default")
      (node (ref "J27") (pin "1") (pinfunction "1_1") (pintype "passive"))
      (node (ref "R60") (pin "P$1") (pinfunction "1_P$1") (pintype "passive"))
    )
    (net (code "61") (name "LS_05") (class "Default")
      (node (ref "R58") (pin "P$2") (pinfunction "2_P$2") (pintype "passive"))
      (node (ref "R59") (pin "P$2") (pinfunction "2_P$2") (pintype "passive"))
      (node (ref "U18") (pin "2") (pinfunction "E(1)_2") (pintype "output"))
      (node (ref "U3") (pin "81") (pinfunction "P3_5_81") (pintype "bidirectional"))
    )
    (net (code "62") (name "LS_05_RET") (class "Default")
      (node (ref "J19") (pin "1") (pinfunction "1_1") (pintype "passive"))
      (node (ref "R57") (pin "P$1") (pinfunction "1_P$1") (pintype "passive"))
    )
    (net (code "63") (name "LS_06") (class "Default")
      (node (ref "R76") (pin "P$2") (pinfunction "2_P$2") (pintype "passive"))
      (node (ref "R77") (pin "P$2") (pinfunction "2_P$2") (pintype "passive"))
      (node (ref "U20") (pin "2") (pinfunction "E(1)_2") (pintype "output"))
      (node (ref "U3") (pin "82") (pinfunction "P3_4_82") (pintype "bidirectional"))
    )
    (net (code "64") (name "LS_06_RET") (class "Default")
      (node (ref "J12") (pin "1") (pinfunction "1_1") (pintype "passive"))
      (node (ref "R75") (pin "P$1") (pinfunction "1_P$1") (pintype "passive"))
    )
    (net (code "65") (name "LS_07") (class "Default")
      (node (ref "R97") (pin "P$2") (pinfunction "2_P$2") (pintype "passive"))
      (node (ref "R98") (pin "P$2") (pinfunction "2_P$2") (pintype "passive"))
      (node (ref "U29") (pin "2") (pinfunction "E(1)_2") (pintype "output"))
      (node (ref "U3") (pin "86") (pinfunction "P3_2_86") (pintype "bidirectional"))
    )
    (net (code "66") (name "LS_07_RET") (class "Default")
      (node (ref "J11") (pin "1") (pinfunction "1_1") (pintype "passive"))
      (node (ref "R84") (pin "P$1") (pinfunction "1_P$1") (pintype "passive"))
    )
    (net (code "67") (name "LS_08") (class "Default")
      (node (ref "R82") (pin "P$2") (pinfunction "2_P$2") (pintype "passive"))
      (node (ref "R83") (pin "P$2") (pinfunction "2_P$2") (pintype "passive"))
      (node (ref "U28") (pin "2") (pinfunction "E(1)_2") (pintype "output"))
      (node (ref "U3") (pin "87") (pinfunction "P3_1_87") (pintype "bidirectional"))
    )
    (net (code "68") (name "LS_08_RET") (class "Default")
      (node (ref "J5") (pin "1") (pinfunction "1_1") (pintype "passive"))
      (node (ref "R81") (pin "P$1") (pinfunction "1_P$1") (pintype "passive"))
    )
    (net (code "69") (name "LS_09") (class "Default")
      (node (ref "R100") (pin "P$2") (pinfunction "2_P$2") (pintype "passive"))
      (node (ref "R101") (pin "P$2") (pinfunction "2_P$2") (pintype "passive"))
      (node (ref "U3") (pin "92") (pinfunction "P1_11_92") (pintype "bidirectional"))
      (node (ref "U30") (pin "2") (pinfunction "E(1)_2") (pintype "output"))
    )
    (net (code "70") (name "LS_09_RET") (class "Default")
      (node (ref "J10") (pin "1") (pinfunction "1_1") (pintype "passive"))
      (node (ref "R99") (pin "P$1") (pinfunction "1_P$1") (pintype "passive"))
    )
    (net (code "71") (name "NC") (class "Default")
      (node (ref "RJ1") (pin "7") (pinfunction "P7_7") (pintype "bidirectional"))
      (node (ref "U3") (pin "79") (pinfunction "P3_7_79") (pintype "bidirectional"))
      (node (ref "U3") (pin "80") (pinfunction "P3_6_80") (pintype "bidirectional"))
      (node (ref "U3") (pin "85") (pinfunction "P3_3_85") (pintype "bidirectional"))
    )
    (net (code "72") (name "Net-(C8-1)") (class "Default")
      (node (ref "C8") (pin "P$1") (pinfunction "1_P$1") (pintype "passive"))
      (node (ref "C9") (pin "P$1") (pinfunction "1_P$1") (pintype "passive"))
      (node (ref "FB1") (pin "2") (pinfunction "P$2_2") (pintype "bidirectional"))
      (node (ref "U1") (pin "2") (pinfunction "VDDA_3.3_2") (pintype "power_in"))
    )
    (net (code "73") (name "Net-(C24-2)") (class "Default")
      (node (ref "C24") (pin "P$2") (pinfunction "2_P$2") (pintype "passive"))
      (node (ref "U3") (pin "148") (pinfunction "VCL2_148") (pintype "bidirectional"))
    )
    (net (code "74") (name "Net-(C28-1)") (class "Default")
      (node (ref "C28") (pin "P$1") (pinfunction "1_P$1") (pintype "passive"))
      (node (ref "J7") (pin "P$1") (pinfunction "VBUS_P$1") (pintype "bidirectional"))
      (node (ref "R16") (pin "P$2") (pinfunction "2_P$2") (pintype "passive"))
      (node (ref "R21") (pin "P$2") (pinfunction "2_P$2") (pintype "passive"))
    )
    (net (code "75") (name "Net-(C33-1)") (class "Default")
      (node (ref "C33") (pin "P$1") (pinfunction "1_P$1") (pintype "passive"))
      (node (ref "U3") (pin "19") (pinfunction "VCLO_19") (pintype "bidirectional"))
    )
    (net (code "76") (name "Net-(C42-1)") (class "Default")
      (node (ref "C42") (pin "P$1") (pinfunction "1_P$1") (pintype "passive"))
      (node (ref "U3") (pin "62") (pinfunction "VCL1_62") (pintype "bidirectional"))
    )
    (net (code "77") (name "Net-(J7-D+)") (class "Default")
      (node (ref "J7") (pin "P$3") (pinfunction "D+_P$3") (pintype "bidirectional"))
      (node (ref "R18") (pin "P$2") (pinfunction "2_P$2") (pintype "passive"))
    )
    (net (code "78") (name "Net-(J7-D-)") (class "Default")
      (node (ref "J7") (pin "P$2") (pinfunction "D-_P$2") (pintype "bidirectional"))
      (node (ref "R17") (pin "P$2") (pinfunction "2_P$2") (pintype "passive"))
    )
    (net (code "79") (name "Net-(LED1-A)") (class "Default")
      (node (ref "LED1") (pin "1") (pinfunction "A_1") (pintype "passive"))
      (node (ref "R5") (pin "P$1") (pinfunction "1_P$1") (pintype "passive"))
    )
    (net (code "80") (name "Net-(LED3-A)") (class "Default")
      (node (ref "LED3") (pin "1") (pinfunction "A_1") (pintype "passive"))
      (node (ref "R33") (pin "P$1") (pinfunction "1_P$1") (pintype "passive"))
    )
    (net (code "81") (name "Net-(LED4-A)") (class "Default")
      (node (ref "LED4") (pin "1") (pinfunction "A_1") (pintype "passive"))
      (node (ref "R32") (pin "P$1") (pinfunction "1_P$1") (pintype "passive"))
    )
    (net (code "82") (name "Net-(LED4-C)") (class "Default")
      (node (ref "LED4") (pin "2") (pinfunction "C_2") (pintype "passive"))
      (node (ref "U$1") (pin "P$1") (pinfunction "VC-_P$1") (pintype "bidirectional"))
      (node (ref "U6") (pin "3") (pinfunction "C(3)_3") (pintype "input"))
    )
    (net (code "83") (name "Net-(LED5-A)") (class "Default")
      (node (ref "LED5") (pin "1") (pinfunction "A_1") (pintype "passive"))
      (node (ref "R31") (pin "P$1") (pinfunction "1_P$1") (pintype "passive"))
    )
    (net (code "84") (name "Net-(LED5-C)") (class "Default")
      (node (ref "LED5") (pin "2") (pinfunction "C_2") (pintype "passive"))
      (node (ref "U$2") (pin "P$1") (pinfunction "VC-_P$1") (pintype "bidirectional"))
      (node (ref "U7") (pin "3") (pinfunction "C(3)_3") (pintype "input"))
    )
    (net (code "85") (name "Net-(LED6-A)") (class "Default")
      (node (ref "LED6") (pin "1") (pinfunction "A_1") (pintype "passive"))
      (node (ref "R36") (pin "P$1") (pinfunction "1_P$1") (pintype "passive"))
    )
    (net (code "86") (name "Net-(LED7-A)") (class "Default")
      (node (ref "LED7") (pin "1") (pinfunction "A_1") (pintype "passive"))
      (node (ref "R55") (pin "P$1") (pinfunction "1_P$1") (pintype "passive"))
    )
    (net (code "87") (name "Net-(LED8-A)") (class "Default")
      (node (ref "LED8") (pin "1") (pinfunction "A_1") (pintype "passive"))
      (node (ref "R52") (pin "P$1") (pinfunction "1_P$1") (pintype "passive"))
    )
    (net (code "88") (name "Net-(LED8-C)") (class "Default")
      (node (ref "LED8") (pin "2") (pinfunction "C_2") (pintype "passive"))
      (node (ref "U$7") (pin "P$1") (pinfunction "VC-_P$1") (pintype "bidirectional"))
      (node (ref "U16") (pin "3") (pinfunction "C(3)_3") (pintype "input"))
    )
    (net (code "89") (name "Net-(LED9-A)") (class "Default")
      (node (ref "LED9") (pin "1") (pinfunction "A_1") (pintype "passive"))
      (node (ref "R51") (pin "P$1") (pinfunction "1_P$1") (pintype "passive"))
    )
    (net (code "90") (name "Net-(LED9-C)") (class "Default")
      (node (ref "LED9") (pin "2") (pinfunction "C_2") (pintype "passive"))
      (node (ref "U$8") (pin "P$1") (pinfunction "VC-_P$1") (pintype "bidirectional"))
      (node (ref "U17") (pin "3") (pinfunction "C(3)_3") (pintype "input"))
    )
    (net (code "91") (name "Net-(LED10-A)") (class "Default")
      (node (ref "LED10") (pin "1") (pinfunction "A_1") (pintype "passive"))
      (node (ref "R58") (pin "P$1") (pinfunction "1_P$1") (pintype "passive"))
    )
    (net (code "92") (name "Net-(LED11-A)") (class "Default")
      (node (ref "LED11") (pin "1") (pinfunction "A_1") (pintype "passive"))
      (node (ref "R73") (pin "P$1") (pinfunction "1_P$1") (pintype "passive"))
    )
    (net (code "93") (name "Net-(LED12-A)") (class "Default")
      (node (ref "LED12") (pin "1") (pinfunction "A_1") (pintype "passive"))
      (node (ref "R76") (pin "P$1") (pinfunction "1_P$1") (pintype "passive"))
    )
    (net (code "94") (name "Net-(LED13-A)") (class "Default")
      (node (ref "LED13") (pin "1") (pinfunction "A_1") (pintype "passive"))
      (node (ref "R79") (pin "P$1") (pinfunction "1_P$1") (pintype "passive"))
    )
    (net (code "95") (name "Net-(LED14-A)") (class "Default")
      (node (ref "LED14") (pin "1") (pinfunction "A_1") (pintype "passive"))
      (node (ref "R82") (pin "P$1") (pinfunction "1_P$1") (pintype "passive"))
    )
    (net (code "96") (name "Net-(LED15-A)") (class "Default")
      (node (ref "LED15") (pin "1") (pinfunction "A_1") (pintype "passive"))
      (node (ref "R97") (pin "P$1") (pinfunction "1_P$1") (pintype "passive"))
    )
    (net (code "97") (name "Net-(LED16-A)") (class "Default")
      (node (ref "LED16") (pin "1") (pinfunction "A_1") (pintype "passive"))
      (node (ref "R100") (pin "P$1") (pinfunction "1_P$1") (pintype "passive"))
    )
    (net (code "98") (name "Net-(R22-2)") (class "Default")
      (node (ref "R22") (pin "P$2") (pinfunction "2_P$2") (pintype "passive"))
      (node (ref "U3") (pin "27") (pinfunction "USBHS_RREF_27") (pintype "bidirectional"))
    )
    (net (code "99") (name "Net-(R23-2)") (class "Default")
      (node (ref "R23") (pin "P$2") (pinfunction "2_P$2") (pintype "passive"))
      (node (ref "U3") (pin "64") (pinfunction "VLO1(DCDC)_64") (pintype "bidirectional"))
    )
    (net (code "100") (name "Net-(R24-2)") (class "Default")
      (node (ref "R24") (pin "P$2") (pinfunction "2_P$2") (pintype "passive"))
      (node (ref "U3") (pin "65") (pinfunction "VLO2(DCDC)_65") (pintype "bidirectional"))
    )
    (net (code "101") (name "Net-(R28-2)") (class "Default")
      (node (ref "R28") (pin "P$2") (pinfunction "2_P$2") (pintype "passive"))
      (node (ref "U5") (pin "1") (pinfunction "B(2)_1") (pintype "input"))
    )
    (net (code "102") (name "Net-(R29-2)") (class "Default")
      (node (ref "R29") (pin "P$2") (pinfunction "2_P$2") (pintype "passive"))
      (node (ref "U6") (pin "1") (pinfunction "B(2)_1") (pintype "input"))
    )
    (net (code "103") (name "Net-(R30-2)") (class "Default")
      (node (ref "R30") (pin "P$2") (pinfunction "2_P$2") (pintype "passive"))
      (node (ref "U7") (pin "1") (pinfunction "B(2)_1") (pintype "input"))
    )
    (net (code "104") (name "Net-(R35-2)") (class "Default")
      (node (ref "R35") (pin "P$2") (pinfunction "2_P$2") (pintype "passive"))
      (node (ref "U8") (pin "1") (pinfunction "B(2)_1") (pintype "input"))
    )
    (net (code "105") (name "Net-(R38-2)") (class "Default")
      (node (ref "R38") (pin "P$2") (pinfunction "2_P$2") (pintype "passive"))
      (node (ref "U10") (pin "1") (pinfunction "B(2)_1") (pintype "input"))
    )
    (net (code "106") (name "Net-(R39-2)") (class "Default")
      (node (ref "R39") (pin "P$2") (pinfunction "2_P$2") (pintype "passive"))
      (node (ref "U11") (pin "1") (pinfunction "B(2)_1") (pintype "input"))
    )
    (net (code "107") (name "Net-(R40-2)") (class "Default")
      (node (ref "R40") (pin "P$2") (pinfunction "2_P$2") (pintype "passive"))
      (node (ref "U12") (pin "1") (pinfunction "B(2)_1") (pintype "input"))
    )
    (net (code "108") (name "Net-(R44-2)") (class "Default")
      (node (ref "R44") (pin "P$2") (pinfunction "2_P$2") (pintype "passive"))
      (node (ref "U13") (pin "1") (pinfunction "B(2)_1") (pintype "input"))
    )
    (net (code "109") (name "Net-(R45-2)") (class "Default")
      (node (ref "R45") (pin "P$2") (pinfunction "2_P$2") (pintype "passive"))
      (node (ref "U14") (pin "1") (pinfunction "B(2)_1") (pintype "input"))
    )
    (net (code "110") (name "Net-(R46-2)") (class "Default")
      (node (ref "R46") (pin "P$2") (pinfunction "2_P$2") (pintype "passive"))
      (node (ref "U15") (pin "1") (pinfunction "B(2)_1") (pintype "input"))
    )
    (net (code "111") (name "Net-(R49-2)") (class "Default")
      (node (ref "R49") (pin "P$2") (pinfunction "2_P$2") (pintype "passive"))
      (node (ref "U16") (pin "1") (pinfunction "B(2)_1") (pintype "input"))
    )
    (net (code "112") (name "Net-(R50-2)") (class "Default")
      (node (ref "R50") (pin "P$2") (pinfunction "2_P$2") (pintype "passive"))
      (node (ref "U17") (pin "1") (pinfunction "B(2)_1") (pintype "input"))
    )
    (net (code "113") (name "Net-(R54-2)") (class "Default")
      (node (ref "R54") (pin "P$2") (pinfunction "2_P$2") (pintype "passive"))
      (node (ref "U9") (pin "1") (pinfunction "B(2)_1") (pintype "input"))
    )
    (net (code "114") (name "Net-(R57-2)") (class "Default")
      (node (ref "R57") (pin "P$2") (pinfunction "2_P$2") (pintype "passive"))
      (node (ref "U18") (pin "1") (pinfunction "B(2)_1") (pintype "input"))
    )
    (net (code "115") (name "Net-(R60-2)") (class "Default")
      (node (ref "R60") (pin "P$2") (pinfunction "2_P$2") (pintype "passive"))
      (node (ref "U19") (pin "1") (pinfunction "B(2)_1") (pintype "input"))
    )
    (net (code "116") (name "Net-(R62-2)") (class "Default")
      (node (ref "R62") (pin "P$2") (pinfunction "2_P$2") (pintype "passive"))
      (node (ref "U22") (pin "1") (pinfunction "B(2)_1") (pintype "input"))
    )
    (net (code "117") (name "Net-(R63-2)") (class "Default")
      (node (ref "R63") (pin "P$2") (pinfunction "2_P$2") (pintype "passive"))
      (node (ref "U23") (pin "1") (pinfunction "B(2)_1") (pintype "input"))
    )
    (net (code "118") (name "Net-(R64-2)") (class "Default")
      (node (ref "R64") (pin "P$2") (pinfunction "2_P$2") (pintype "passive"))
      (node (ref "U24") (pin "1") (pinfunction "B(2)_1") (pintype "input"))
    )
    (net (code "119") (name "Net-(R68-2)") (class "Default")
      (node (ref "R68") (pin "P$2") (pinfunction "2_P$2") (pintype "passive"))
      (node (ref "U25") (pin "1") (pinfunction "B(2)_1") (pintype "input"))
    )
    (net (code "120") (name "Net-(R69-2)") (class "Default")
      (node (ref "R69") (pin "P$2") (pinfunction "2_P$2") (pintype "passive"))
      (node (ref "U26") (pin "1") (pinfunction "B(2)_1") (pintype "input"))
    )
    (net (code "121") (name "Net-(R70-2)") (class "Default")
      (node (ref "R70") (pin "P$2") (pinfunction "2_P$2") (pintype "passive"))
      (node (ref "U27") (pin "1") (pinfunction "B(2)_1") (pintype "input"))
    )
    (net (code "122") (name "Net-(R75-2)") (class "Default")
      (node (ref "R75") (pin "P$2") (pinfunction "2_P$2") (pintype "passive"))
      (node (ref "U20") (pin "1") (pinfunction "B(2)_1") (pintype "input"))
    )
    (net (code "123") (name "Net-(R78-2)") (class "Default")
      (node (ref "R78") (pin "P$2") (pinfunction "2_P$2") (pintype "passive"))
      (node (ref "U21") (pin "1") (pinfunction "B(2)_1") (pintype "input"))
    )
    (net (code "124") (name "Net-(R81-2)") (class "Default")
      (node (ref "R81") (pin "P$2") (pinfunction "2_P$2") (pintype "passive"))
      (node (ref "U28") (pin "1") (pinfunction "B(2)_1") (pintype "input"))
    )
    (net (code "125") (name "Net-(R84-2)") (class "Default")
      (node (ref "R84") (pin "P$2") (pinfunction "2_P$2") (pintype "passive"))
      (node (ref "U29") (pin "1") (pinfunction "B(2)_1") (pintype "input"))
    )
    (net (code "126") (name "Net-(R86-2)") (class "Default")
      (node (ref "R86") (pin "P$2") (pinfunction "2_P$2") (pintype "passive"))
      (node (ref "U34") (pin "1") (pinfunction "B(2)_1") (pintype "input"))
    )
    (net (code "127") (name "Net-(R87-2)") (class "Default")
      (node (ref "R87") (pin "P$2") (pinfunction "2_P$2") (pintype "passive"))
      (node (ref "U35") (pin "1") (pinfunction "B(2)_1") (pintype "input"))
    )
    (net (code "128") (name "Net-(R88-2)") (class "Default")
      (node (ref "R88") (pin "P$2") (pinfunction "2_P$2") (pintype "passive"))
      (node (ref "U36") (pin "1") (pinfunction "B(2)_1") (pintype "input"))
    )
    (net (code "129") (name "Net-(R92-2)") (class "Default")
      (node (ref "R92") (pin "P$2") (pinfunction "2_P$2") (pintype "passive"))
      (node (ref "U37") (pin "1") (pinfunction "B(2)_1") (pintype "input"))
    )
    (net (code "130") (name "Net-(R93-2)") (class "Default")
      (node (ref "R93") (pin "P$2") (pinfunction "2_P$2") (pintype "passive"))
      (node (ref "U38") (pin "1") (pinfunction "B(2)_1") (pintype "input"))
    )
    (net (code "131") (name "Net-(R94-2)") (class "Default")
      (node (ref "R94") (pin "P$2") (pinfunction "2_P$2") (pintype "passive"))
      (node (ref "U39") (pin "1") (pinfunction "B(2)_1") (pintype "input"))
    )
    (net (code "132") (name "Net-(R99-2)") (class "Default")
      (node (ref "R99") (pin "P$2") (pinfunction "2_P$2") (pintype "passive"))
      (node (ref "U30") (pin "1") (pinfunction "B(2)_1") (pintype "input"))
    )
    (net (code "133") (name "Net-(R110-2)") (class "Default")
      (node (ref "R110") (pin "P$2") (pinfunction "2_P$2") (pintype "passive"))
      (node (ref "U46") (pin "1") (pinfunction "B(2)_1") (pintype "input"))
    )
    (net (code "134") (name "Net-(R111-2)") (class "Default")
      (node (ref "R111") (pin "P$2") (pinfunction "2_P$2") (pintype "passive"))
      (node (ref "U47") (pin "1") (pinfunction "B(2)_1") (pintype "input"))
    )
    (net (code "135") (name "Net-(R112-2)") (class "Default")
      (node (ref "R112") (pin "P$2") (pinfunction "2_P$2") (pintype "passive"))
      (node (ref "U48") (pin "1") (pinfunction "B(2)_1") (pintype "input"))
    )
    (net (code "136") (name "Net-(R116-2)") (class "Default")
      (node (ref "R116") (pin "P$2") (pinfunction "2_P$2") (pintype "passive"))
      (node (ref "U49") (pin "1") (pinfunction "B(2)_1") (pintype "input"))
    )
    (net (code "137") (name "Net-(R117-2)") (class "Default")
      (node (ref "R117") (pin "P$2") (pinfunction "2_P$2") (pintype "passive"))
      (node (ref "U50") (pin "1") (pinfunction "B(2)_1") (pintype "input"))
    )
    (net (code "138") (name "Net-(R118-2)") (class "Default")
      (node (ref "R118") (pin "P$2") (pinfunction "2_P$2") (pintype "passive"))
      (node (ref "U51") (pin "1") (pinfunction "B(2)_1") (pintype "input"))
    )
    (net (code "139") (name "Net-(R134-2)") (class "Default")
      (node (ref "R134") (pin "P$2") (pinfunction "2_P$2") (pintype "passive"))
      (node (ref "U58") (pin "1") (pinfunction "B(2)_1") (pintype "input"))
    )
    (net (code "140") (name "Net-(R135-2)") (class "Default")
      (node (ref "R135") (pin "P$2") (pinfunction "2_P$2") (pintype "passive"))
      (node (ref "U59") (pin "1") (pinfunction "B(2)_1") (pintype "input"))
    )
    (net (code "141") (name "Net-(R136-2)") (class "Default")
      (node (ref "R136") (pin "P$2") (pinfunction "2_P$2") (pintype "passive"))
      (node (ref "U60") (pin "1") (pinfunction "B(2)_1") (pintype "input"))
    )
    (net (code "142") (name "Net-(R140-2)") (class "Default")
      (node (ref "R140") (pin "P$2") (pinfunction "2_P$2") (pintype "passive"))
      (node (ref "U61") (pin "1") (pinfunction "B(2)_1") (pintype "input"))
    )
    (net (code "143") (name "Net-(R141-2)") (class "Default")
      (node (ref "R141") (pin "P$2") (pinfunction "2_P$2") (pintype "passive"))
      (node (ref "U62") (pin "1") (pinfunction "B(2)_1") (pintype "input"))
    )
    (net (code "144") (name "Net-(R142-2)") (class "Default")
      (node (ref "R142") (pin "P$2") (pinfunction "2_P$2") (pintype "passive"))
      (node (ref "U63") (pin "1") (pinfunction "B(2)_1") (pintype "input"))
    )
    (net (code "145") (name "Net-(R158-2)") (class "Default")
      (node (ref "R158") (pin "P$2") (pinfunction "2_P$2") (pintype "passive"))
      (node (ref "U70") (pin "1") (pinfunction "B(2)_1") (pintype "input"))
    )
    (net (code "146") (name "Net-(R159-2)") (class "Default")
      (node (ref "R159") (pin "P$2") (pinfunction "2_P$2") (pintype "passive"))
      (node (ref "U71") (pin "1") (pinfunction "B(2)_1") (pintype "input"))
    )
    (net (code "147") (name "Net-(R160-2)") (class "Default")
      (node (ref "R160") (pin "P$2") (pinfunction "2_P$2") (pintype "passive"))
      (node (ref "U72") (pin "1") (pinfunction "B(2)_1") (pintype "input"))
    )
    (net (code "148") (name "Net-(R164-2)") (class "Default")
      (node (ref "R164") (pin "P$2") (pinfunction "2_P$2") (pintype "passive"))
      (node (ref "U73") (pin "1") (pinfunction "B(2)_1") (pintype "input"))
    )
    (net (code "149") (name "Net-(R165-2)") (class "Default")
      (node (ref "R165") (pin "P$2") (pinfunction "2_P$2") (pintype "passive"))
      (node (ref "U74") (pin "1") (pinfunction "B(2)_1") (pintype "input"))
    )
    (net (code "150") (name "Net-(R166-2)") (class "Default")
      (node (ref "R166") (pin "P$2") (pinfunction "2_P$2") (pintype "passive"))
      (node (ref "U75") (pin "1") (pinfunction "B(2)_1") (pintype "input"))
    )
    (net (code "151") (name "P0_00") (class "Default")
      (node (ref "J4") (pin "P$2") (pinfunction "P$2_P$2") (pintype "bidirectional"))
      (node (ref "U3") (pin "169") (pinfunction "P0_0/AN0\\00_169") (pintype "bidirectional"))
    )
    (net (code "152") (name "P0_01") (class "Default")
      (node (ref "J4") (pin "P$1") (pinfunction "P$1_P$1") (pintype "bidirectional"))
      (node (ref "U3") (pin "168") (pinfunction "P0_1/AN001_168") (pintype "bidirectional"))
    )
    (net (code "153") (name "P0_02_TH_01") (class "Default")
      (node (ref "R25") (pin "P$1") (pinfunction "1_P$1") (pintype "passive"))
      (node (ref "TH01") (pin "2") (pinfunction "2_2") (pintype "passive"))
      (node (ref "U3") (pin "167") (pinfunction "P0_2/AN002_167") (pintype "bidirectional"))
    )
    (net (code "154") (name "P0_03") (class "Default")
      (node (ref "J8") (pin "P$6") (pinfunction "P$6_P$6") (pintype "bidirectional"))
      (node (ref "U3") (pin "166") (pinfunction "P0_3/PGAVSS000_166") (pintype "bidirectional"))
    )
    (net (code "155") (name "P0_04_TH_02") (class "Default")
      (node (ref "R27") (pin "P$1") (pinfunction "1_P$1") (pintype "passive"))
      (node (ref "TH02") (pin "2") (pinfunction "2_2") (pintype "passive"))
      (node (ref "U3") (pin "165") (pinfunction "P0_4/AN100_165") (pintype "bidirectional"))
    )
    (net (code "156") (name "P0_05_TH_03") (class "Default")
      (node (ref "R102") (pin "P$1") (pinfunction "1_P$1") (pintype "passive"))
      (node (ref "TH03") (pin "2") (pinfunction "2_2") (pintype "passive"))
      (node (ref "U3") (pin "164") (pinfunction "P0_5/AN101_164") (pintype "bidirectional"))
    )
    (net (code "157") (name "P0_06_TH_04") (class "Default")
      (node (ref "R103") (pin "P$1") (pinfunction "1_P$1") (pintype "passive"))
      (node (ref "TH04") (pin "2") (pinfunction "2_2") (pintype "passive"))
      (node (ref "U3") (pin "163") (pinfunction "P0_6/AN102_163") (pintype "bidirectional"))
    )
    (net (code "158") (name "P0_07") (class "Default")
      (node (ref "J8") (pin "P$12") (pinfunction "P$12_P$12") (pintype "bidirectional"))
      (node (ref "U3") (pin "162") (pinfunction "P0_7/PGVSS100_162") (pintype "bidirectional"))
    )
    (net (code "159") (name "P0_08_TH_05") (class "Default")
      (node (ref "R105") (pin "P$1") (pinfunction "1_P$1") (pintype "passive"))
      (node (ref "TH05") (pin "2") (pinfunction "2_2") (pintype "passive"))
      (node (ref "U3") (pin "161") (pinfunction "P0_8/AN003_161") (pintype "bidirectional"))
    )
    (net (code "160") (name "P0_09_TH_06") (class "Default")
      (node (ref "R106") (pin "P$1") (pinfunction "1_P$1") (pintype "passive"))
      (node (ref "TH06") (pin "2") (pinfunction "2_2") (pintype "passive"))
      (node (ref "U3") (pin "160") (pinfunction "P0_9/AN004_160") (pintype "bidirectional"))
    )
    (net (code "161") (name "P0_14_TH_07") (class "Default")
      (node (ref "R107") (pin "P$1") (pinfunction "1_P$1") (pintype "passive"))
      (node (ref "TH07") (pin "2") (pinfunction "2_2") (pintype "passive"))
      (node (ref "U3") (pin "152") (pinfunction "P0_14/DA0/AN005/AN105_152") (pintype "bidirectional"))
    )
    (net (code "162") (name "P0_15_TH_08") (class "Default")
      (node (ref "R108") (pin "P$1") (pinfunction "1_P$1") (pintype "passive"))
      (node (ref "TH08") (pin "2") (pinfunction "2_2") (pintype "passive"))
      (node (ref "U3") (pin "151") (pinfunction "P0_15/DA1/AN006/AN106_151") (pintype "bidirectional"))
    )
    (net (code "163") (name "P1_02") (class "Default")
      (node (ref "J8") (pin "P$10") (pinfunction "P$10_P$10") (pintype "bidirectional"))
      (node (ref "U3") (pin "130") (pinfunction "P1_2_130") (pintype "bidirectional"))
    )
    (net (code "164") (name "P1_03") (class "Default")
      (node (ref "J8") (pin "P$9") (pinfunction "P$9_P$9") (pintype "bidirectional"))
      (node (ref "U3") (pin "129") (pinfunction "P1_3_129") (pintype "bidirectional"))
    )
    (net (code "165") (name "P1_04") (class "Default")
      (node (ref "J8") (pin "P$11") (pinfunction "P$11_P$11") (pintype "bidirectional"))
      (node (ref "U3") (pin "128") (pinfunction "P1_4_128") (pintype "bidirectional"))
    )
    (net (code "166") (name "P1_05") (class "Default")
      (node (ref "J8") (pin "P$13") (pinfunction "P$13_P$13") (pintype "bidirectional"))
      (node (ref "U3") (pin "127") (pinfunction "P1_5_127") (pintype "bidirectional"))
    )
    (net (code "167") (name "P1_06") (class "Default")
      (node (ref "J8") (pin "P$15") (pinfunction "P$15_P$15") (pintype "bidirectional"))
      (node (ref "U3") (pin "126") (pinfunction "P1_6_126") (pintype "bidirectional"))
    )
    (net (code "168") (name "P1_07") (class "Default")
      (node (ref "J8") (pin "P$17") (pinfunction "P$17_P$17") (pintype "bidirectional"))
      (node (ref "U3") (pin "125") (pinfunction "P1_7_125") (pintype "bidirectional"))
    )
    (net (code "169") (name "P4_00") (class "Default")
      (node (ref "J4") (pin "P$7") (pinfunction "P$7_P$7") (pintype "bidirectional"))
      (node (ref "U3") (pin "1") (pinfunction "P4_0_1") (pintype "bidirectional"))
    )
    (net (code "170") (name "P4_01") (class "Default")
      (node (ref "J4") (pin "P$8") (pinfunction "P$8_P$8") (pintype "bidirectional"))
      (node (ref "U3") (pin "2") (pinfunction "P4_1_2") (pintype "bidirectional"))
    )
    (net (code "171") (name "P4_02") (class "Default")
      (node (ref "J4") (pin "P$9") (pinfunction "P$9_P$9") (pintype "bidirectional"))
      (node (ref "U3") (pin "3") (pinfunction "P4_2_3") (pintype "bidirectional"))
    )
    (net (code "172") (name "P4_08") (class "Default")
      (node (ref "J4") (pin "P$20") (pinfunction "P$20_P$20") (pintype "bidirectional"))
      (node (ref "U3") (pin "43") (pinfunction "P4_8_43") (pintype "bidirectional"))
    )
    (net (code "173") (name "P4_09") (class "Default")
      (node (ref "J4") (pin "P$19") (pinfunction "P$19_P$19") (pintype "bidirectional"))
      (node (ref "U3") (pin "42") (pinfunction "P4_9_42") (pintype "bidirectional"))
    )
    (net (code "174") (name "P4_10") (class "Default")
      (node (ref "J4") (pin "P$18") (pinfunction "P$18_P$18") (pintype "bidirectional"))
      (node (ref "U3") (pin "41") (pinfunction "P4_10_41") (pintype "bidirectional"))
    )
    (net (code "175") (name "P4_11") (class "Default")
      (node (ref "J4") (pin "P$17") (pinfunction "P$17_P$17") (pintype "bidirectional"))
      (node (ref "U3") (pin "40") (pinfunction "P4_11_40") (pintype "bidirectional"))
    )
    (net (code "176") (name "P4_12") (class "Default")
      (node (ref "J4") (pin "P$16") (pinfunction "P$16_P$16") (pintype "bidirectional"))
      (node (ref "U3") (pin "39") (pinfunction "P4_12_39") (pintype "bidirectional"))
    )
    (net (code "177") (name "P4_13") (class "Default")
      (node (ref "J4") (pin "P$15") (pinfunction "P$15_P$15") (pintype "bidirectional"))
      (node (ref "U3") (pin "38") (pinfunction "P4_13_38") (pintype "bidirectional"))
    )
    (net (code "178") (name "P4_14") (class "Default")
      (node (ref "J4") (pin "P$14") (pinfunction "P$14_P$14") (pintype "bidirectional"))
      (node (ref "U3") (pin "37") (pinfunction "P4_14_37") (pintype "bidirectional"))
    )
    (net (code "179") (name "P4_15") (class "Default")
      (node (ref "J4") (pin "P$13") (pinfunction "P$13_P$13") (pintype "bidirectional"))
      (node (ref "U3") (pin "36") (pinfunction "P4_15_36") (pintype "bidirectional"))
    )
    (net (code "180") (name "P5_11") (class "Default")
      (node (ref "J4") (pin "P$6") (pinfunction "P$6_P$6") (pintype "bidirectional"))
      (node (ref "U3") (pin "176") (pinfunction "P5_11_176") (pintype "bidirectional"))
    )
    (net (code "181") (name "P5_12") (class "Default")
      (node (ref "J4") (pin "P$5") (pinfunction "P$5_P$5") (pintype "bidirectional"))
      (node (ref "U3") (pin "175") (pinfunction "P5_12_175") (pintype "bidirectional"))
    )
    (net (code "182") (name "P5_13") (class "Default")
      (node (ref "J4") (pin "P$4") (pinfunction "P$4_P$4") (pintype "bidirectional"))
      (node (ref "U3") (pin "174") (pinfunction "P5_13_174") (pintype "bidirectional"))
    )
    (net (code "183") (name "P6_00") (class "Default")
      (node (ref "J8") (pin "P$19") (pinfunction "P$19_P$19") (pintype "bidirectional"))
      (node (ref "U3") (pin "122") (pinfunction "P6_0_122") (pintype "bidirectional"))
    )
    (net (code "184") (name "P7_06") (class "Default")
      (node (ref "J4") (pin "P$10") (pinfunction "P$10_P$10") (pintype "bidirectional"))
      (node (ref "U3") (pin "14") (pinfunction "P7_6_14") (pintype "bidirectional"))
    )
    (net (code "185") (name "P7_07") (class "Default")
      (node (ref "J4") (pin "P$11") (pinfunction "P$11_P$11") (pintype "bidirectional"))
      (node (ref "U3") (pin "15") (pinfunction "P7_7_15") (pintype "bidirectional"))
    )
    (net (code "186") (name "P8_00") (class "Default")
      (node (ref "J8") (pin "P$5") (pinfunction "P$5_P$5") (pintype "bidirectional"))
      (node (ref "U3") (pin "133") (pinfunction "P8_0_133") (pintype "bidirectional"))
    )
    (net (code "187") (name "P8_01") (class "Default")
      (node (ref "J8") (pin "P$3") (pinfunction "P$3_P$3") (pintype "bidirectional"))
      (node (ref "U3") (pin "134") (pinfunction "P8_1_134") (pintype "bidirectional"))
    )
    (net (code "188") (name "P8_02") (class "Default")
      (node (ref "J8") (pin "P$4") (pinfunction "P$4_P$4") (pintype "bidirectional"))
      (node (ref "U3") (pin "135") (pinfunction "P8_2_135") (pintype "bidirectional"))
    )
    (net (code "189") (name "P8_03") (class "Default")
      (node (ref "J8") (pin "P$1") (pinfunction "P$1_P$1") (pintype "bidirectional"))
      (node (ref "U3") (pin "136") (pinfunction "P8_3_136") (pintype "bidirectional"))
    )
    (net (code "190") (name "P8_04") (class "Default")
      (node (ref "J8") (pin "P$2") (pinfunction "P$2_P$2") (pintype "bidirectional"))
      (node (ref "U3") (pin "137") (pinfunction "P8_4_137") (pintype "bidirectional"))
    )
    (net (code "191") (name "P8_05") (class "Default")
      (node (ref "J4") (pin "P$3") (pinfunction "P$3_P$3") (pintype "bidirectional"))
      (node (ref "U3") (pin "173") (pinfunction "P8_5_173") (pintype "bidirectional"))
    )
    (net (code "192") (name "PB_00") (class "Default")
      (node (ref "J4") (pin "P$12") (pinfunction "P$12_P$12") (pintype "bidirectional"))
      (node (ref "U3") (pin "16") (pinfunction "PB_0_16") (pintype "bidirectional"))
    )
    (net (code "193") (name "R51") (class "Default")
      (node (ref "R7") (pin "P$1") (pinfunction "1_P$1") (pintype "passive"))
      (node (ref "RJ1") (pin "12") (pinfunction "YHI_12") (pintype "bidirectional"))
    )
    (net (code "194") (name "R52") (class "Default")
      (node (ref "R8") (pin "P$1") (pinfunction "1_P$1") (pintype "passive"))
      (node (ref "RJ1") (pin "9") (pinfunction "GHI_9") (pintype "bidirectional"))
    )
    (net (code "195") (name "RELAY_1") (class "Default")
      (node (ref "R29") (pin "P$1") (pinfunction "1_P$1") (pintype "passive"))
      (node (ref "U3") (pin "56") (pinfunction "P3_14_56") (pintype "bidirectional"))
    )
    (net (code "196") (name "RELAY_2") (class "Default")
      (node (ref "R30") (pin "P$1") (pinfunction "1_P$1") (pintype "passive"))
      (node (ref "U3") (pin "55") (pinfunction "P3_13_55") (pintype "bidirectional"))
    )
    (net (code "197") (name "RELAY_3") (class "Default")
      (node (ref "R49") (pin "P$1") (pinfunction "1_P$1") (pintype "passive"))
      (node (ref "U3") (pin "52") (pinfunction "P2_4_52") (pintype "bidirectional"))
    )
    (net (code "198") (name "RELAY_4") (class "Default")
      (node (ref "R50") (pin "P$1") (pinfunction "1_P$1") (pintype "passive"))
      (node (ref "U3") (pin "49") (pinfunction "P2_7_49") (pintype "bidirectional"))
    )
    (net (code "199") (name "RESET") (class "Default")
      (node (ref "C16") (pin "P$1") (pinfunction "1_P$1") (pintype "passive"))
      (node (ref "J3") (pin "9") (pinfunction "9_9") (pintype "passive"))
      (node (ref "R13") (pin "P$1") (pinfunction "1_P$1") (pintype "passive"))
      (node (ref "U3") (pin "67") (pinfunction "RES#_67") (pintype "bidirectional"))
    )
    (net (code "200") (name "REXT") (class "Default")
      (node (ref "C3") (pin "P$1") (pinfunction "1_P$1") (pintype "passive"))
      (node (ref "R1") (pin "P$2") (pinfunction "2_P$2") (pintype "passive"))
      (node (ref "U1") (pin "9") (pinfunction "REXT_9") (pintype "input"))
    )
    (net (code "201") (name "RO_NEG_1") (class "Default")
      (node (ref "J15") (pin "P$2") (pinfunction "P$2_P$2") (pintype "bidirectional"))
      (node (ref "U$1") (pin "P$3") (pinfunction "VO-_P$3") (pintype "bidirectional"))
    )
    (net (code "202") (name "RO_NEG_2") (class "Default")
      (node (ref "J16") (pin "P$2") (pinfunction "P$2_P$2") (pintype "bidirectional"))
      (node (ref "U$2") (pin "P$3") (pinfunction "VO-_P$3") (pintype "bidirectional"))
    )
    (net (code "203") (name "RO_NEG_3") (class "Default")
      (node (ref "J23") (pin "P$2") (pinfunction "P$2_P$2") (pintype "bidirectional"))
      (node (ref "U$7") (pin "P$3") (pinfunction "VO-_P$3") (pintype "bidirectional"))
    )
    (net (code "204") (name "RO_NEG_4") (class "Default")
      (node (ref "J24") (pin "P$2") (pinfunction "P$2_P$2") (pintype "bidirectional"))
      (node (ref "U$8") (pin "P$3") (pinfunction "VO-_P$3") (pintype "bidirectional"))
    )
    (net (code "205") (name "RO_POS_1") (class "Default")
      (node (ref "J15") (pin "P$1") (pinfunction "P$1_P$1") (pintype "bidirectional"))
      (node (ref "U$1") (pin "P$4") (pinfunction "VO+_P$4") (pintype "bidirectional"))
    )
    (net (code "206") (name "RO_POS_2") (class "Default")
      (node (ref "J16") (pin "P$1") (pinfunction "P$1_P$1") (pintype "bidirectional"))
      (node (ref "U$2") (pin "P$4") (pinfunction "VO+_P$4") (pintype "bidirectional"))
    )
    (net (code "207") (name "RO_POS_3") (class "Default")
      (node (ref "J23") (pin "P$1") (pinfunction "P$1_P$1") (pintype "bidirectional"))
      (node (ref "U$7") (pin "P$4") (pinfunction "VO+_P$4") (pintype "bidirectional"))
    )
    (net (code "208") (name "RO_POS_4") (class "Default")
      (node (ref "J24") (pin "P$1") (pinfunction "P$1_P$1") (pintype "bidirectional"))
      (node (ref "U$8") (pin "P$4") (pinfunction "VO+_P$4") (pintype "bidirectional"))
    )
    (net (code "209") (name "RXD0") (class "Default")
      (node (ref "R10") (pin "P$2") (pinfunction "2_P$2") (pintype "passive"))
      (node (ref "U1") (pin "13") (pinfunction "RXD0_13") (pintype "bidirectional"))
    )
    (net (code "210") (name "RXD1") (class "Default")
      (node (ref "R9") (pin "P$2") (pinfunction "2_P$2") (pintype "passive"))
      (node (ref "U1") (pin "12") (pinfunction "RXD1_12") (pintype "bidirectional"))
    )
    (net (code "211") (name "RXER") (class "Default")
      (node (ref "R11") (pin "P$2") (pinfunction "2_P$2") (pintype "passive"))
      (node (ref "U1") (pin "17") (pinfunction "RXER_17") (pintype "bidirectional"))
    )
    (net (code "212") (name "RXM") (class "Default")
      (node (ref "RJ1") (pin "6") (pinfunction "RD-_6") (pintype "bidirectional"))
      (node (ref "U1") (pin "3") (pinfunction "RXM_3") (pintype "bidirectional"))
    )
    (net (code "213") (name "RXP") (class "Default")
      (node (ref "RJ1") (pin "3") (pinfunction "RD+_3") (pintype "bidirectional"))
      (node (ref "U1") (pin "4") (pinfunction "RXP_4") (pintype "bidirectional"))
    )
    (net (code "214") (name "SD1_CD") (class "Default")
      (node (ref "J1") (pin "10") (pinfunction "CD_SWITCH2_10") (pintype "bidirectional"))
      (node (ref "U3") (pin "146") (pinfunction "P5_6/AN019_146") (pintype "bidirectional"))
    )
    (net (code "215") (name "SD1_CLK") (class "Default")
      (node (ref "J1") (pin "5") (pinfunction "CLOCK_5") (pintype "bidirectional"))
      (node (ref "U3") (pin "140") (pinfunction "P5_0/AN016_140") (pintype "bidirectional"))
    )
    (net (code "216") (name "SD1_CMD") (class "Default")
      (node (ref "J1") (pin "3") (pinfunction "COMMAND/RESPONSE_3") (pintype "bidirectional"))
      (node (ref "U3") (pin "141") (pinfunction "P5_1/AN116_141") (pintype "bidirectional"))
    )
    (net (code "217") (name "SD1_DAT0") (class "Default")
      (node (ref "J1") (pin "7") (pinfunction "DATA_LINE[BIT_0]_7") (pintype "bidirectional"))
      (node (ref "U3") (pin "142") (pinfunction "P5_2/AN017_142") (pintype "bidirectional"))
    )
    (net (code "218") (name "SD1_DAT1") (class "Default")
      (node (ref "J1") (pin "8") (pinfunction "DATA_LINE[BIT_1]_8") (pintype "bidirectional"))
      (node (ref "U3") (pin "143") (pinfunction "P5_3/AN117_143") (pintype "bidirectional"))
    )
    (net (code "219") (name "SD1_DAT2") (class "Default")
      (node (ref "J1") (pin "1") (pinfunction "DATA_LINE[BIT_2]_1") (pintype "bidirectional"))
      (node (ref "U3") (pin "144") (pinfunction "P5_4/AN018_144") (pintype "bidirectional"))
    )
    (net (code "220") (name "SD1_DAT3") (class "Default")
      (node (ref "J1") (pin "2") (pinfunction "CARD_DETECT/DATA_LINE[BIT_3]_2") (pintype "bidirectional"))
      (node (ref "U3") (pin "145") (pinfunction "P5_5/AN118_145") (pintype "bidirectional"))
    )
    (net (code "221") (name "SD1_WP") (class "Default")
      (node (ref "J1") (pin "9") (pinfunction "CD_SWITCH1_9") (pintype "bidirectional"))
      (node (ref "U3") (pin "147") (pinfunction "P5_7/AN119_147") (pintype "bidirectional"))
    )
    (net (code "222") (name "TCK") (class "Default")
      (node (ref "J3") (pin "7") (pinfunction "7_7") (pintype "passive"))
      (node (ref "U3") (pin "88") (pinfunction "P3_0_88") (pintype "bidirectional"))
    )
    (net (code "223") (name "TDI") (class "Default")
      (node (ref "J3") (pin "1") (pinfunction "1_1") (pintype "passive"))
      (node (ref "U3") (pin "91") (pinfunction "P1_10_91") (pintype "bidirectional"))
    )
    (net (code "224") (name "TDO") (class "Default")
      (node (ref "J3") (pin "3") (pinfunction "3_3") (pintype "passive"))
      (node (ref "U3") (pin "90") (pinfunction "P1_9_90") (pintype "bidirectional"))
    )
    (net (code "225") (name "TMS") (class "Default")
      (node (ref "J3") (pin "5") (pinfunction "5_5") (pintype "passive"))
      (node (ref "U3") (pin "89") (pinfunction "P1_8_89") (pintype "bidirectional"))
    )
    (net (code "226") (name "TXM") (class "Default")
      (node (ref "RJ1") (pin "2") (pinfunction "TD-_2") (pintype "bidirectional"))
      (node (ref "U1") (pin "5") (pinfunction "TXM_5") (pintype "bidirectional"))
    )
    (net (code "227") (name "TXP") (class "Default")
      (node (ref "RJ1") (pin "1") (pinfunction "TD+_1") (pintype "bidirectional"))
      (node (ref "U1") (pin "6") (pinfunction "TXP_6") (pintype "bidirectional"))
    )
    (net (code "228") (name "USBHS_FAULT") (class "Default")
      (node (ref "R19") (pin "P$1") (pinfunction "1_P$1") (pintype "passive"))
      (node (ref "U2") (pin "3") (pinfunction "FLG_3") (pintype "input"))
      (node (ref "U3") (pin "78") (pinfunction "P3_8_78") (pintype "bidirectional"))
    )
    (net (code "229") (name "USBHS_N") (class "Default")
      (node (ref "J6") (pin "D-") (pinfunction "D-_D-") (pintype "bidirectional"))
      (node (ref "U3") (pin "31") (pinfunction "USBHS_DM_31") (pintype "bidirectional"))
    )
    (net (code "230") (name "USBHS_P") (class "Default")
      (node (ref "J6") (pin "D+") (pinfunction "D+_D+") (pintype "bidirectional"))
      (node (ref "U3") (pin "32") (pinfunction "USBHS_DP_32") (pintype "bidirectional"))
    )
    (net (code "231") (name "USBHS_VBUS") (class "Default")
      (node (ref "C29") (pin "P$1") (pinfunction "1_P$1") (pintype "passive"))
      (node (ref "C31") (pin "1") (pinfunction "1_1") (pintype "passive"))
      (node (ref "J6") (pin "VBUS") (pinfunction "VBUS_VBUS") (pintype "power_in"))
      (node (ref "U2") (pin "5") (pinfunction "OUT_5") (pintype "input"))
      (node (ref "U3") (pin "17") (pinfunction "PB_1_17") (pintype "bidirectional"))
    )
    (net (code "232") (name "USBHS_VBUSEN") (class "Default")
      (node (ref "R20") (pin "P$1") (pinfunction "1_P$1") (pintype "passive"))
      (node (ref "U2") (pin "1") (pinfunction "EN_1") (pintype "input"))
    )
    (net (code "233") (name "USB_N") (class "Default")
      (node (ref "R17") (pin "P$1") (pinfunction "1_P$1") (pintype "passive"))
      (node (ref "U3") (pin "46") (pinfunction "USB_DM_46") (pintype "bidirectional"))
    )
    (net (code "234") (name "USB_P") (class "Default")
      (node (ref "R18") (pin "P$1") (pinfunction "1_P$1") (pintype "passive"))
      (node (ref "U3") (pin "47") (pinfunction "USB_DP_47") (pintype "bidirectional"))
    )
    (net (code "235") (name "USB_VBUS_B") (class "Default")
      (node (ref "R16") (pin "P$1") (pinfunction "1_P$1") (pintype "passive"))
      (node (ref "U3") (pin "44") (pinfunction "P4_7_44") (pintype "bidirectional"))
    )
    (net (code "236") (name "VCL_F(FLASH)") (class "Default")
      (node (ref "C34") (pin "P$2") (pinfunction "2_P$2") (pintype "passive"))
      (node (ref "U3") (pin "112") (pinfunction "VCL_F(FLASH)_112") (pintype "bidirectional"))
    )
    (net (code "237") (name "VDD") (class "Default")
      (node (ref "C14") (pin "P$1") (pinfunction "1_P$1") (pintype "passive"))
      (node (ref "C15") (pin "P$1") (pinfunction "1_P$1") (pintype "passive"))
      (node (ref "C19") (pin "P$2") (pinfunction "2_P$2") (pintype "passive"))
      (node (ref "C20") (pin "P$2") (pinfunction "2_P$2") (pintype "passive"))
      (node (ref "C21") (pin "P$2") (pinfunction "2_P$2") (pintype "passive"))
      (node (ref "C22") (pin "P$2") (pinfunction "2_P$2") (pintype "passive"))
      (node (ref "C25") (pin "P$2") (pinfunction "2_P$2") (pintype "passive"))
      (node (ref "C27") (pin "P$2") (pinfunction "2_P$2") (pintype "passive"))
      (node (ref "C30") (pin "P$2") (pinfunction "2_P$2") (pintype "passive"))
      (node (ref "C35") (pin "P$2") (pinfunction "2_P$2") (pintype "passive"))
      (node (ref "C36") (pin "P$1") (pinfunction "1_P$1") (pintype "passive"))
      (node (ref "C38") (pin "P$2") (pinfunction "2_P$2") (pintype "passive"))
      (node (ref "C39") (pin "P$1") (pinfunction "1_P$1") (pintype "passive"))
      (node (ref "C4") (pin "P$1") (pinfunction "1_P$1") (pintype "passive"))
      (node (ref "C40") (pin "P$1") (pinfunction "1_P$1") (pintype "passive"))
      (node (ref "C41") (pin "P$1") (pinfunction "1_P$1") (pintype "passive"))
      (node (ref "C43") (pin "P$2") (pinfunction "2_P$2") (pintype "passive"))
      (node (ref "C5") (pin "P$1") (pinfunction "1_P$1") (pintype "passive"))
      (node (ref "C7") (pin "P$1") (pinfunction "1_P$1") (pintype "passive"))
      (node (ref "FB1") (pin "1") (pinfunction "P$1_1") (pintype "bidirectional"))
      (node (ref "J1") (pin "4") (pinfunction "SUPPLY_VOLTAGE_4") (pintype "power_in"))
      (node (ref "J3") (pin "2") (pinfunction "2_2") (pintype "passive"))
      (node (ref "J3") (pin "4") (pinfunction "4_4") (pintype "passive"))
      (node (ref "L1") (pin "2") (pinfunction "P$2_2") (pintype "bidirectional"))
      (node (ref "R102") (pin "P$2") (pinfunction "2_P$2") (pintype "passive"))
      (node (ref "R103") (pin "P$2") (pinfunction "2_P$2") (pintype "passive"))
      (node (ref "R105") (pin "P$2") (pinfunction "2_P$2") (pintype "passive"))
      (node (ref "R106") (pin "P$2") (pinfunction "2_P$2") (pintype "passive"))
      (node (ref "R107") (pin "P$2") (pinfunction "2_P$2") (pintype "passive"))
      (node (ref "R108") (pin "P$2") (pinfunction "2_P$2") (pintype "passive"))
      (node (ref "R13") (pin "P$2") (pinfunction "2_P$2") (pintype "passive"))
      (node (ref "R14") (pin "P$1") (pinfunction "1_P$1") (pintype "passive"))
      (node (ref "R15") (pin "P$1") (pinfunction "1_P$1") (pintype "passive"))
      (node (ref "R2") (pin "P$2") (pinfunction "2_P$2") (pintype "passive"))
      (node (ref "R25") (pin "P$2") (pinfunction "2_P$2") (pintype "passive"))
      (node (ref "R27") (pin "P$2") (pinfunction "2_P$2") (pintype "passive"))
      (node (ref "R3") (pin "P$2") (pinfunction "2_P$2") (pintype "passive"))
      (node (ref "R4") (pin "P$2") (pinfunction "2_P$2") (pintype "passive"))
      (node (ref "R5") (pin "P$2") (pinfunction "2_P$2") (pintype "passive"))
      (node (ref "R6") (pin "P$2") (pinfunction "2_P$2") (pintype "passive"))
      (node (ref "R7") (pin "P$2") (pinfunction "2_P$2") (pintype "passive"))
      (node (ref "R8") (pin "P$2") (pinfunction "2_P$2") (pintype "passive"))
      (node (ref "U1") (pin "14") (pinfunction "VDDIO_14") (pintype "power_in"))
      (node (ref "U18") (pin "3") (pinfunction "C(3)_3") (pintype "input"))
      (node (ref "U19") (pin "3") (pinfunction "C(3)_3") (pintype "input"))
      (node (ref "U20") (pin "3") (pinfunction "C(3)_3") (pintype "input"))
      (node (ref "U21") (pin "3") (pinfunction "C(3)_3") (pintype "input"))
      (node (ref "U28") (pin "3") (pinfunction "C(3)_3") (pintype "input"))
      (node (ref "U29") (pin "3") (pinfunction "C(3)_3") (pintype "input"))
      (node (ref "U3") (pin "110") (pinfunction "VCC(IO)5_110") (pintype "bidirectional"))
      (node (ref "U3") (pin "123") (pinfunction "VCC(IO)6_123") (pintype "bidirectional"))
      (node (ref "U3") (pin "138") (pinfunction "VCC(IO)7_138") (pintype "bidirectional"))
      (node (ref "U3") (pin "149") (pinfunction "VCC(IO)8_149") (pintype "bidirectional"))
      (node (ref "U3") (pin "154") (pinfunction "VREFH_154") (pintype "bidirectional"))
      (node (ref "U3") (pin "155") (pinfunction "AVCC0_155") (pintype "bidirectional"))
      (node (ref "U3") (pin "158") (pinfunction "VREFH0_158") (pintype "bidirectional"))
      (node (ref "U3") (pin "171") (pinfunction "VCC(IO)9_171") (pintype "bidirectional"))
      (node (ref "U3") (pin "25") (pinfunction "VCC1_25") (pintype "bidirectional"))
      (node (ref "U3") (pin "26") (pinfunction "AVCC_SUBHS_26") (pintype "bidirectional"))
      (node (ref "U3") (pin "34") (pinfunction "VCC_USBHS_34") (pintype "bidirectional"))
      (node (ref "U3") (pin "48") (pinfunction "VCC_USB_48") (pintype "bidirectional"))
      (node (ref "U3") (pin "61") (pinfunction "VCC(IO)2_61") (pintype "bidirectional"))
      (node (ref "U3") (pin "84") (pinfunction "VCC(IO)3_84") (pintype "bidirectional"))
      (node (ref "U3") (pin "97") (pinfunction "VCC(IO)4_97") (pintype "bidirectional"))
      (node (ref "U30") (pin "3") (pinfunction "C(3)_3") (pintype "input"))
      (node (ref "U5") (pin "3") (pinfunction "C(3)_3") (pintype "input"))
      (node (ref "U8") (pin "3") (pinfunction "C(3)_3") (pintype "input"))
      (node (ref "U9") (pin "3") (pinfunction "C(3)_3") (pintype "input"))
    )
    (net (code "238") (name "VDD5") (class "Default")
      (node (ref "C23") (pin "P$1") (pinfunction "1_P$1") (pintype "passive"))
      (node (ref "C26") (pin "P$1") (pinfunction "1_P$1") (pintype "passive"))
      (node (ref "J2") (pin "P$3") (pinfunction "P$3_P$3") (pintype "bidirectional"))
      (node (ref "R19") (pin "P$2") (pinfunction "2_P$2") (pintype "passive"))
      (node (ref "R20") (pin "P$2") (pinfunction "2_P$2") (pintype "passive"))
      (node (ref "R31") (pin "P$2") (pinfunction "2_P$2") (pintype "passive"))
      (node (ref "R32") (pin "P$2") (pinfunction "2_P$2") (pintype "passive"))
      (node (ref "R51") (pin "P$2") (pinfunction "2_P$2") (pintype "passive"))
      (node (ref "R52") (pin "P$2") (pinfunction "2_P$2") (pintype "passive"))
      (node (ref "U$1") (pin "P$2") (pinfunction "VC+_P$2") (pintype "bidirectional"))
      (node (ref "U$2") (pin "P$2") (pinfunction "VC+_P$2") (pintype "bidirectional"))
      (node (ref "U$7") (pin "P$2") (pinfunction "VC+_P$2") (pintype "bidirectional"))
      (node (ref "U$8") (pin "P$2") (pinfunction "VC+_P$2") (pintype "bidirectional"))
      (node (ref "U2") (pin "4") (pinfunction "VIN_4") (pintype "input"))
    )
    (net (code "239") (name "VDD12") (class "Default")
      (node (ref "J10") (pin "3") (pinfunction "3_3") (pintype "passive"))
      (node (ref "J11") (pin "3") (pinfunction "3_3") (pintype "passive"))
      (node (ref "J12") (pin "3") (pinfunction "3_3") (pintype "passive"))
      (node (ref "J13") (pin "1") (pinfunction "1-HLFB+_1") (pintype "passive"))
      (node (ref "J13") (pin "2") (pinfunction "2-INPUT_B+_2") (pintype "passive"))
      (node (ref "J13") (pin "3") (pinfunction "3-INPUT_A+_3") (pintype "passive"))
      (node (ref "J13") (pin "4") (pinfunction "4-ENABLE+_4") (pintype "passive"))
      (node (ref "J14") (pin "1") (pinfunction "1-HLFB+_1") (pintype "passive"))
      (node (ref "J14") (pin "2") (pinfunction "2-INPUT_B+_2") (pintype "passive"))
      (node (ref "J14") (pin "3") (pinfunction "3-INPUT_A+_3") (pintype "passive"))
      (node (ref "J14") (pin "4") (pinfunction "4-ENABLE+_4") (pintype "passive"))
      (node (ref "J17") (pin "1") (pinfunction "1-HLFB+_1") (pintype "passive"))
      (node (ref "J17") (pin "2") (pinfunction "2-INPUT_B+_2") (pintype "passive"))
      (node (ref "J17") (pin "3") (pinfunction "3-INPUT_A+_3") (pintype "passive"))
      (node (ref "J17") (pin "4") (pinfunction "4-ENABLE+_4") (pintype "passive"))
      (node (ref "J18") (pin "1") (pinfunction "1-HLFB+_1") (pintype "passive"))
      (node (ref "J18") (pin "2") (pinfunction "2-INPUT_B+_2") (pintype "passive"))
      (node (ref "J18") (pin "3") (pinfunction "3-INPUT_A+_3") (pintype "passive"))
      (node (ref "J18") (pin "4") (pinfunction "4-ENABLE+_4") (pintype "passive"))
      (node (ref "J19") (pin "3") (pinfunction "3_3") (pintype "passive"))
      (node (ref "J20") (pin "3") (pinfunction "3_3") (pintype "passive"))
      (node (ref "J21") (pin "1") (pinfunction "1-HLFB+_1") (pintype "passive"))
      (node (ref "J21") (pin "2") (pinfunction "2-INPUT_B+_2") (pintype "passive"))
      (node (ref "J21") (pin "3") (pinfunction "3-INPUT_A+_3") (pintype "passive"))
      (node (ref "J21") (pin "4") (pinfunction "4-ENABLE+_4") (pintype "passive"))
      (node (ref "J22") (pin "1") (pinfunction "1-HLFB+_1") (pintype "passive"))
      (node (ref "J22") (pin "2") (pinfunction "2-INPUT_B+_2") (pintype "passive"))
      (node (ref "J22") (pin "3") (pinfunction "3-INPUT_A+_3") (pintype "passive"))
      (node (ref "J22") (pin "4") (pinfunction "4-ENABLE+_4") (pintype "passive"))
      (node (ref "J25") (pin "1") (pinfunction "1-HLFB+_1") (pintype "passive"))
      (node (ref "J25") (pin "2") (pinfunction "2-INPUT_B+_2") (pintype "passive"))
      (node (ref "J25") (pin "3") (pinfunction "3-INPUT_A+_3") (pintype "passive"))
      (node (ref "J25") (pin "4") (pinfunction "4-ENABLE+_4") (pintype "passive"))
      (node (ref "J26") (pin "1") (pinfunction "1-HLFB+_1") (pintype "passive"))
      (node (ref "J26") (pin "2") (pinfunction "2-INPUT_B+_2") (pintype "passive"))
      (node (ref "J26") (pin "3") (pinfunction "3-INPUT_A+_3") (pintype "passive"))
      (node (ref "J26") (pin "4") (pinfunction "4-ENABLE+_4") (pintype "passive"))
      (node (ref "J27") (pin "3") (pinfunction "3_3") (pintype "passive"))
      (node (ref "J28") (pin "3") (pinfunction "3_3") (pintype "passive"))
      (node (ref "J29") (pin "1") (pinfunction "1-HLFB+_1") (pintype "passive"))
      (node (ref "J29") (pin "2") (pinfunction "2-INPUT_B+_2") (pintype "passive"))
      (node (ref "J29") (pin "3") (pinfunction "3-INPUT_A+_3") (pintype "passive"))
      (node (ref "J29") (pin "4") (pinfunction "4-ENABLE+_4") (pintype "passive"))
      (node (ref "J30") (pin "1") (pinfunction "1-HLFB+_1") (pintype "passive"))
      (node (ref "J30") (pin "2") (pinfunction "2-INPUT_B+_2") (pintype "passive"))
      (node (ref "J30") (pin "3") (pinfunction "3-INPUT_A+_3") (pintype "passive"))
      (node (ref "J30") (pin "4") (pinfunction "4-ENABLE+_4") (pintype "passive"))
      (node (ref "J31") (pin "3") (pinfunction "3_3") (pintype "passive"))
      (node (ref "J32") (pin "3") (pinfunction "3_3") (pintype "passive"))
      (node (ref "J33") (pin "1") (pinfunction "1-HLFB+_1") (pintype "passive"))
      (node (ref "J33") (pin "2") (pinfunction "2-INPUT_B+_2") (pintype "passive"))
      (node (ref "J33") (pin "3") (pinfunction "3-INPUT_A+_3") (pintype "passive"))
      (node (ref "J33") (pin "4") (pinfunction "4-ENABLE+_4") (pintype "passive"))
      (node (ref "J34") (pin "1") (pinfunction "1-HLFB+_1") (pintype "passive"))
      (node (ref "J34") (pin "2") (pinfunction "2-INPUT_B+_2") (pintype "passive"))
      (node (ref "J34") (pin "3") (pinfunction "3-INPUT_A+_3") (pintype "passive"))
      (node (ref "J34") (pin "4") (pinfunction "4-ENABLE+_4") (pintype "passive"))
      (node (ref "J5") (pin "3") (pinfunction "3_3") (pintype "passive"))
      (node (ref "J9") (pin "P$1") (pinfunction "P$1_P$1") (pintype "bidirectional"))
      (node (ref "J9") (pin "P$2") (pinfunction "P$2_P$2") (pintype "bidirectional"))
      (node (ref "R109") (pin "2") (pinfunction "2_2") (pintype "passive"))
      (node (ref "R113") (pin "2") (pinfunction "2_2") (pintype "passive"))
      (node (ref "R114") (pin "2") (pinfunction "2_2") (pintype "passive"))
      (node (ref "R115") (pin "2") (pinfunction "2_2") (pintype "passive"))
      (node (ref "R119") (pin "2") (pinfunction "2_2") (pintype "passive"))
      (node (ref "R120") (pin "2") (pinfunction "2_2") (pintype "passive"))
      (node (ref "R133") (pin "2") (pinfunction "2_2") (pintype "passive"))
      (node (ref "R137") (pin "2") (pinfunction "2_2") (pintype "passive"))
      (node (ref "R138") (pin "2") (pinfunction "2_2") (pintype "passive"))
      (node (ref "R139") (pin "2") (pinfunction "2_2") (pintype "passive"))
      (node (ref "R143") (pin "2") (pinfunction "2_2") (pintype "passive"))
      (node (ref "R144") (pin "2") (pinfunction "2_2") (pintype "passive"))
      (node (ref "R157") (pin "2") (pinfunction "2_2") (pintype "passive"))
      (node (ref "R161") (pin "2") (pinfunction "2_2") (pintype "passive"))
      (node (ref "R162") (pin "2") (pinfunction "2_2") (pintype "passive"))
      (node (ref "R163") (pin "2") (pinfunction "2_2") (pintype "passive"))
      (node (ref "R167") (pin "2") (pinfunction "2_2") (pintype "passive"))
      (node (ref "R168") (pin "2") (pinfunction "2_2") (pintype "passive"))
      (node (ref "R37") (pin "2") (pinfunction "2_2") (pintype "passive"))
      (node (ref "R41") (pin "2") (pinfunction "2_2") (pintype "passive"))
      (node (ref "R42") (pin "2") (pinfunction "2_2") (pintype "passive"))
      (node (ref "R43") (pin "2") (pinfunction "2_2") (pintype "passive"))
      (node (ref "R47") (pin "2") (pinfunction "2_2") (pintype "passive"))
      (node (ref "R48") (pin "2") (pinfunction "2_2") (pintype "passive"))
      (node (ref "R61") (pin "2") (pinfunction "2_2") (pintype "passive"))
      (node (ref "R65") (pin "2") (pinfunction "2_2") (pintype "passive"))
      (node (ref "R66") (pin "2") (pinfunction "2_2") (pintype "passive"))
      (node (ref "R67") (pin "2") (pinfunction "2_2") (pintype "passive"))
      (node (ref "R71") (pin "2") (pinfunction "2_2") (pintype "passive"))
      (node (ref "R72") (pin "2") (pinfunction "2_2") (pintype "passive"))
      (node (ref "R85") (pin "2") (pinfunction "2_2") (pintype "passive"))
      (node (ref "R89") (pin "2") (pinfunction "2_2") (pintype "passive"))
      (node (ref "R90") (pin "2") (pinfunction "2_2") (pintype "passive"))
      (node (ref "R91") (pin "2") (pinfunction "2_2") (pintype "passive"))
      (node (ref "R95") (pin "2") (pinfunction "2_2") (pintype "passive"))
      (node (ref "R96") (pin "2") (pinfunction "2_2") (pintype "passive"))
    )
    (net (code "240") (name "VDDIN") (class "Default")
      (node (ref "J2") (pin "P$2") (pinfunction "P$2_P$2") (pintype "bidirectional"))
      (node (ref "L1") (pin "1") (pinfunction "P$1_1") (pintype "bidirectional"))
    )
    (net (code "241") (name "VDD_1.2") (class "Default")
      (node (ref "C10") (pin "P$1") (pinfunction "1_P$1") (pintype "passive"))
      (node (ref "C11") (pin "P$1") (pinfunction "1_P$1") (pintype "passive"))
      (node (ref "U1") (pin "1") (pinfunction "VDD_1.2_1") (pintype "power_in"))
    )
    (net (code "242") (name "WF_A_DIR") (class "Default")
      (node (ref "R159") (pin "P$1") (pinfunction "1_P$1") (pintype "passive"))
      (node (ref "U3") (pin "99") (pinfunction "P6_8_99") (pintype "bidirectional"))
    )
    (net (code "243") (name "WF_A_ENABLE") (class "Default")
      (node (ref "R160") (pin "P$1") (pinfunction "1_P$1") (pintype "passive"))
      (node (ref "U3") (pin "96") (pinfunction "P1_15_96") (pintype "bidirectional"))
    )
    (net (code "244") (name "WF_A_HLFB_OUT") (class "Default")
      (node (ref "J33") (pin "5") (pinfunction "5-HLFB-_5") (pintype "passive"))
    )
    (net (code "245") (name "WF_A_MI_DIR") (class "Default")
      (node (ref "J33") (pin "7") (pinfunction "7-INPUT_A-_7") (pintype "passive"))
      (node (ref "R161") (pin "1") (pinfunction "1_1") (pintype "passive"))
      (node (ref "U71") (pin "3") (pinfunction "C(3)_3") (pintype "input"))
    )
    (net (code "246") (name "WF_A_MI_ENABLE") (class "Default")
      (node (ref "J33") (pin "8") (pinfunction "8-ENABLE-_8") (pintype "passive"))
      (node (ref "R162") (pin "1") (pinfunction "1_1") (pintype "passive"))
      (node (ref "U72") (pin "3") (pinfunction "C(3)_3") (pintype "input"))
    )
    (net (code "247") (name "WF_A_MI_STEP") (class "Default")
      (node (ref "J33") (pin "6") (pinfunction "6-INPUT_B-_6") (pintype "passive"))
      (node (ref "R157") (pin "1") (pinfunction "1_1") (pintype "passive"))
      (node (ref "U70") (pin "3") (pinfunction "C(3)_3") (pintype "input"))
    )
    (net (code "248") (name "WF_A_STEP") (class "Default")
      (node (ref "R158") (pin "P$1") (pinfunction "1_P$1") (pintype "passive"))
      (node (ref "U3") (pin "100") (pinfunction "P6_9_100") (pintype "bidirectional"))
    )
    (net (code "249") (name "WF_B_DIR") (class "Default")
      (node (ref "R165") (pin "P$1") (pinfunction "1_P$1") (pintype "passive"))
      (node (ref "U3") (pin "94") (pinfunction "P1_13_94") (pintype "bidirectional"))
    )
    (net (code "250") (name "WF_B_ENABLE") (class "Default")
      (node (ref "R166") (pin "P$1") (pinfunction "1_P$1") (pintype "passive"))
      (node (ref "U3") (pin "93") (pinfunction "P1_12_93") (pintype "bidirectional"))
    )
    (net (code "251") (name "WF_B_HLFB_OUT") (class "Default")
      (node (ref "J34") (pin "5") (pinfunction "5-HLFB-_5") (pintype "passive"))
    )
    (net (code "252") (name "WF_B_MI_ENABLE") (class "Default")
      (node (ref "J34") (pin "8") (pinfunction "8-ENABLE-_8") (pintype "passive"))
      (node (ref "R168") (pin "1") (pinfunction "1_1") (pintype "passive"))
      (node (ref "U75") (pin "3") (pinfunction "C(3)_3") (pintype "input"))
    )
    (net (code "253") (name "WF_B_MI_STEP") (class "Default")
      (node (ref "J34") (pin "6") (pinfunction "6-INPUT_B-_6") (pintype "passive"))
      (node (ref "R163") (pin "1") (pinfunction "1_1") (pintype "passive"))
      (node (ref "U73") (pin "3") (pinfunction "C(3)_3") (pintype "input"))
    )
    (net (code "254") (name "WF_B_STEP") (class "Default")
      (node (ref "R164") (pin "P$1") (pinfunction "1_P$1") (pintype "passive"))
      (node (ref "U3") (pin "95") (pinfunction "P1_14_95") (pintype "bidirectional"))
    )
    (net (code "255") (name "XCIN") (class "Default")
      (node (ref "C32") (pin "P$1") (pinfunction "1_P$1") (pintype "passive"))
      (node (ref "U3") (pin "20") (pinfunction "XCIN_20") (pintype "bidirectional"))
      (node (ref "X3") (pin "P$1") (pinfunction "P$1_P$1") (pintype "bidirectional"))
    )
    (net (code "256") (name "XCOUT") (class "Default")
      (node (ref "C37") (pin "P$1") (pinfunction "1_P$1") (pintype "passive"))
      (node (ref "U3") (pin "21") (pinfunction "XCOUT_21") (pintype "bidirectional"))
      (node (ref "X3") (pin "P$2") (pinfunction "P$2_P$2") (pintype "bidirectional"))
    )
    (net (code "257") (name "XII") (class "Default")
      (node (ref "C1") (pin "P$1") (pinfunction "1_P$1") (pintype "passive"))
      (node (ref "U1") (pin "8") (pinfunction "XI_8") (pintype "input"))
      (node (ref "X1") (pin "1") (pinfunction "1_1") (pintype "bidirectional"))
    )
    (net (code "258") (name "XOO") (class "Default")
      (node (ref "C2") (pin "P$1") (pinfunction "1_P$1") (pintype "passive"))
      (node (ref "U1") (pin "7") (pinfunction "XO_7") (pintype "output"))
      (node (ref "X1") (pin "3") (pinfunction "3_3") (pintype "bidirectional"))
    )
    (net (code "259") (name "XTAL1") (class "Default")
      (node (ref "C17") (pin "P$1") (pinfunction "1_P$1") (pintype "passive"))
      (node (ref "U3") (pin "23") (pinfunction "P2_13/XTAL_23") (pintype "bidirectional"))
      (node (ref "X2") (pin "1") (pinfunction "1_1") (pintype "bidirectional"))
    )
    (net (code "260") (name "XTAL2") (class "Default")
      (node (ref "C18") (pin "P$1") (pinfunction "1_P$1") (pintype "passive"))
      (node (ref "U3") (pin "24") (pinfunction "P2_12/EXTAL_24") (pintype "bidirectional"))
      (node (ref "X2") (pin "3") (pinfunction "3_3") (pintype "bidirectional"))
    )
    (net (code "261") (name "X_A_DIR") (class "Default")
      (node (ref "R39") (pin "P$1") (pinfunction "1_P$1") (pintype "passive"))
      (node (ref "U3") (pin "117") (pinfunction "P6_5_117") (pintype "bidirectional"))
    )
    (net (code "262") (name "X_A_ENABLE") (class "Default")
      (node (ref "R40") (pin "P$1") (pinfunction "1_P$1") (pintype "passive"))
      (node (ref "U3") (pin "116") (pinfunction "P6_6_116") (pintype "bidirectional"))
    )
    (net (code "263") (name "X_A_HLFB_OUT") (class "Default")
      (node (ref "J13") (pin "5") (pinfunction "5-HLFB-_5") (pintype "passive"))
    )
    (net (code "264") (name "X_A_MI_DIR") (class "Default")
      (node (ref "J13") (pin "7") (pinfunction "7-INPUT_A-_7") (pintype "passive"))
      (node (ref "R41") (pin "1") (pinfunction "1_1") (pintype "passive"))
      (node (ref "U11") (pin "3") (pinfunction "C(3)_3") (pintype "input"))
    )
    (net (code "265") (name "X_A_MI_ENABLE") (class "Default")
      (node (ref "J13") (pin "8") (pinfunction "8-ENABLE-_8") (pintype "passive"))
      (node (ref "R42") (pin "1") (pinfunction "1_1") (pintype "passive"))
      (node (ref "U12") (pin "3") (pinfunction "C(3)_3") (pintype "input"))
    )
    (net (code "266") (name "X_A_MI_STEP") (class "Default")
      (node (ref "J13") (pin "6") (pinfunction "6-INPUT_B-_6") (pintype "passive"))
      (node (ref "R37") (pin "1") (pinfunction "1_1") (pintype "passive"))
      (node (ref "U10") (pin "3") (pinfunction "C(3)_3") (pintype "input"))
    )
    (net (code "267") (name "X_A_STEP") (class "Default")
      (node (ref "R38") (pin "P$1") (pinfunction "1_P$1") (pintype "passive"))
      (node (ref "U3") (pin "118") (pinfunction "P6_4_118") (pintype "bidirectional"))
    )
    (net (code "268") (name "X_B_DIR") (class "Default")
      (node (ref "R45") (pin "P$1") (pinfunction "1_P$1") (pintype "passive"))
      (node (ref "U3") (pin "120") (pinfunction "P6_2_120") (pintype "bidirectional"))
    )
    (net (code "269") (name "X_B_ENABLE") (class "Default")
      (node (ref "R46") (pin "P$1") (pinfunction "1_P$1") (pintype "passive"))
      (node (ref "U3") (pin "119") (pinfunction "P6_3_119") (pintype "bidirectional"))
    )
    (net (code "270") (name "X_B_HLFB_OUT") (class "Default")
      (node (ref "J14") (pin "5") (pinfunction "5-HLFB-_5") (pintype "passive"))
    )
    (net (code "271") (name "X_B_MI_DIR") (class "Default")
      (node (ref "J14") (pin "7") (pinfunction "7-INPUT_A-_7") (pintype "passive"))
      (node (ref "R47") (pin "1") (pinfunction "1_1") (pintype "passive"))
      (node (ref "U14") (pin "3") (pinfunction "C(3)_3") (pintype "input"))
    )
    (net (code "272") (name "X_B_MI_ENABLE") (class "Default")
      (node (ref "J14") (pin "8") (pinfunction "8-ENABLE-_8") (pintype "passive"))
      (node (ref "R48") (pin "1") (pinfunction "1_1") (pintype "passive"))
      (node (ref "U15") (pin "3") (pinfunction "C(3)_3") (pintype "input"))
    )
    (net (code "273") (name "X_B_MI_STEP") (class "Default")
      (node (ref "J14") (pin "6") (pinfunction "6-INPUT_B-_6") (pintype "passive"))
      (node (ref "R43") (pin "1") (pinfunction "1_1") (pintype "passive"))
      (node (ref "U13") (pin "3") (pinfunction "C(3)_3") (pintype "input"))
    )
    (net (code "274") (name "X_B_STEP") (class "Default")
      (node (ref "R44") (pin "P$1") (pinfunction "1_P$1") (pintype "passive"))
      (node (ref "U3") (pin "121") (pinfunction "P6_1_121") (pintype "bidirectional"))
    )
    (net (code "275") (name "Y_A_DIR") (class "Default")
      (node (ref "R63") (pin "P$1") (pinfunction "1_P$1") (pintype "passive"))
      (node (ref "U3") (pin "114") (pinfunction "PA_0_114") (pintype "bidirectional"))
    )
    (net (code "276") (name "Y_A_ENABLE") (class "Default")
      (node (ref "R64") (pin "P$1") (pinfunction "1_P$1") (pintype "passive"))
      (node (ref "U3") (pin "113") (pinfunction "PA_1_113") (pintype "bidirectional"))
    )
    (net (code "277") (name "Y_A_HLFB_OUT") (class "Default")
      (node (ref "J17") (pin "5") (pinfunction "5-HLFB-_5") (pintype "passive"))
    )
    (net (code "278") (name "Y_A_MI_DIR") (class "Default")
      (node (ref "J17") (pin "7") (pinfunction "7-INPUT_A-_7") (pintype "passive"))
      (node (ref "R65") (pin "1") (pinfunction "1_1") (pintype "passive"))
      (node (ref "U23") (pin "3") (pinfunction "C(3)_3") (pintype "input"))
    )
    (net (code "279") (name "Y_A_MI_ENABLE") (class "Default")
      (node (ref "J17") (pin "8") (pinfunction "8-ENABLE-_8") (pintype "passive"))
      (node (ref "R66") (pin "1") (pinfunction "1_1") (pintype "passive"))
      (node (ref "U24") (pin "3") (pinfunction "C(3)_3") (pintype "input"))
    )
    (net (code "280") (name "Y_A_MI_STEP") (class "Default")
      (node (ref "J17") (pin "6") (pinfunction "6-INPUT_B-_6") (pintype "passive"))
      (node (ref "R61") (pin "1") (pinfunction "1_1") (pintype "passive"))
      (node (ref "U22") (pin "3") (pinfunction "C(3)_3") (pintype "input"))
    )
    (net (code "281") (name "Y_A_STEP") (class "Default")
      (node (ref "R62") (pin "P$1") (pinfunction "1_P$1") (pintype "passive"))
      (node (ref "U3") (pin "115") (pinfunction "P6_7_115") (pintype "bidirectional"))
    )
    (net (code "282") (name "Y_B_DIR") (class "Default")
      (node (ref "R69") (pin "P$1") (pinfunction "1_P$1") (pintype "passive"))
      (node (ref "U3") (pin "108") (pinfunction "PA_9_108") (pintype "bidirectional"))
    )
    (net (code "283") (name "Y_B_ENABLE") (class "Default")
      (node (ref "R70") (pin "P$1") (pinfunction "1_P$1") (pintype "passive"))
      (node (ref "U3") (pin "107") (pinfunction "PA_8_107") (pintype "bidirectional"))
    )
    (net (code "284") (name "Y_B_HLFB_OUT") (class "Default")
      (node (ref "J18") (pin "5") (pinfunction "5-HLFB-_5") (pintype "passive"))
    )
    (net (code "285") (name "Y_B_MI_DIR") (class "Default")
      (node (ref "J18") (pin "7") (pinfunction "7-INPUT_A-_7") (pintype "passive"))
      (node (ref "R71") (pin "1") (pinfunction "1_1") (pintype "passive"))
      (node (ref "U26") (pin "3") (pinfunction "C(3)_3") (pintype "input"))
    )
    (net (code "286") (name "Y_B_MI_ENABLE") (class "Default")
      (node (ref "J18") (pin "8") (pinfunction "8-ENABLE-_8") (pintype "passive"))
      (node (ref "R72") (pin "1") (pinfunction "1_1") (pintype "passive"))
      (node (ref "U27") (pin "3") (pinfunction "C(3)_3") (pintype "input"))
    )
    (net (code "287") (name "Y_B_MI_STEP") (class "Default")
      (node (ref "J18") (pin "6") (pinfunction "6-INPUT_B-_6") (pintype "passive"))
      (node (ref "R67") (pin "1") (pinfunction "1_1") (pintype "passive"))
      (node (ref "U25") (pin "3") (pinfunction "C(3)_3") (pintype "input"))
    )
    (net (code "288") (name "Y_B_STEP") (class "Default")
      (node (ref "R68") (pin "P$1") (pinfunction "1_P$1") (pintype "passive"))
      (node (ref "U3") (pin "109") (pinfunction "PA_10_109") (pintype "bidirectional"))
    )
    (net (code "289") (name "Z_A_DIR") (class "Default")
      (node (ref "R87") (pin "P$1") (pinfunction "1_P$1") (pintype "passive"))
      (node (ref "U3") (pin "105") (pinfunction "P6_14_105") (pintype "bidirectional"))
    )
    (net (code "290") (name "Z_A_ENABLE") (class "Default")
      (node (ref "R88") (pin "P$1") (pinfunction "1_P$1") (pintype "passive"))
      (node (ref "U3") (pin "104") (pinfunction "P6_13_104") (pintype "bidirectional"))
    )
    (net (code "291") (name "Z_A_HLFB_OUT") (class "Default")
      (node (ref "J21") (pin "5") (pinfunction "5-HLFB-_5") (pintype "passive"))
    )
    (net (code "292") (name "Z_A_MI_DIR") (class "Default")
      (node (ref "J21") (pin "7") (pinfunction "7-INPUT_A-_7") (pintype "passive"))
      (node (ref "R89") (pin "1") (pinfunction "1_1") (pintype "passive"))
      (node (ref "U35") (pin "3") (pinfunction "C(3)_3") (pintype "input"))
    )
    (net (code "293") (name "Z_A_MI_ENABLE") (class "Default")
      (node (ref "J21") (pin "8") (pinfunction "8-ENABLE-_8") (pintype "passive"))
      (node (ref "R90") (pin "1") (pinfunction "1_1") (pintype "passive"))
      (node (ref "U36") (pin "3") (pinfunction "C(3)_3") (pintype "input"))
    )
    (net (code "294") (name "Z_A_MI_STEP") (class "Default")
      (node (ref "J21") (pin "6") (pinfunction "6-INPUT_B-_6") (pintype "passive"))
      (node (ref "R85") (pin "1") (pinfunction "1_1") (pintype "passive"))
      (node (ref "U34") (pin "3") (pinfunction "C(3)_3") (pintype "input"))
    )
    (net (code "295") (name "Z_A_STEP") (class "Default")
      (node (ref "R86") (pin "P$1") (pinfunction "1_P$1") (pintype "passive"))
      (node (ref "U3") (pin "106") (pinfunction "P6_15_106") (pintype "bidirectional"))
    )
    (net (code "296") (name "Z_B_DIR") (class "Default")
      (node (ref "R93") (pin "P$1") (pinfunction "1_P$1") (pintype "passive"))
      (node (ref "U3") (pin "102") (pinfunction "P6_11_102") (pintype "bidirectional"))
    )
    (net (code "297") (name "Z_B_ENABLE") (class "Default")
      (node (ref "R94") (pin "P$1") (pinfunction "1_P$1") (pintype "passive"))
      (node (ref "U3") (pin "101") (pinfunction "P6_10_101") (pintype "bidirectional"))
    )
    (net (code "298") (name "Z_B_HLFB_OUT") (class "Default")
      (node (ref "J22") (pin "5") (pinfunction "5-HLFB-_5") (pintype "passive"))
    )
    (net (code "299") (name "Z_B_MI_DIR") (class "Default")
      (node (ref "J22") (pin "7") (pinfunction "7-INPUT_A-_7") (pintype "passive"))
      (node (ref "R95") (pin "1") (pinfunction "1_1") (pintype "passive"))
      (node (ref "U38") (pin "3") (pinfunction "C(3)_3") (pintype "input"))
    )
    (net (code "300") (name "Z_B_MI_ENABLE") (class "Default")
      (node (ref "J22") (pin "8") (pinfunction "8-ENABLE-_8") (pintype "passive"))
      (node (ref "R96") (pin "1") (pinfunction "1_1") (pintype "passive"))
      (node (ref "U39") (pin "3") (pinfunction "C(3)_3") (pintype "input"))
    )
    (net (code "301") (name "Z_B_MI_STEP") (class "Default")
      (node (ref "J22") (pin "6") (pinfunction "6-INPUT_B-_6") (pintype "passive"))
      (node (ref "R91") (pin "1") (pinfunction "1_1") (pintype "passive"))
      (node (ref "U37") (pin "3") (pinfunction "C(3)_3") (pintype "input"))
    )
    (net (code "302") (name "Z_B_STEP") (class "Default")
      (node (ref "R92") (pin "P$1") (pinfunction "1_P$1") (pintype "passive"))
      (node (ref "U3") (pin "103") (pinfunction "P6_12_103") (pintype "bidirectional"))
    )
    (net (code "303") (name "unconnected-(U3-VBAT-Pad18)") (class "Default")
      (node (ref "U3") (pin "18") (pinfunction "VBAT_18") (pintype "bidirectional"))
    )
  )
)
